# MRD104_MICROBOARD_APPS_A.net
KiCad netlist of a schematic drawn in EAGLE
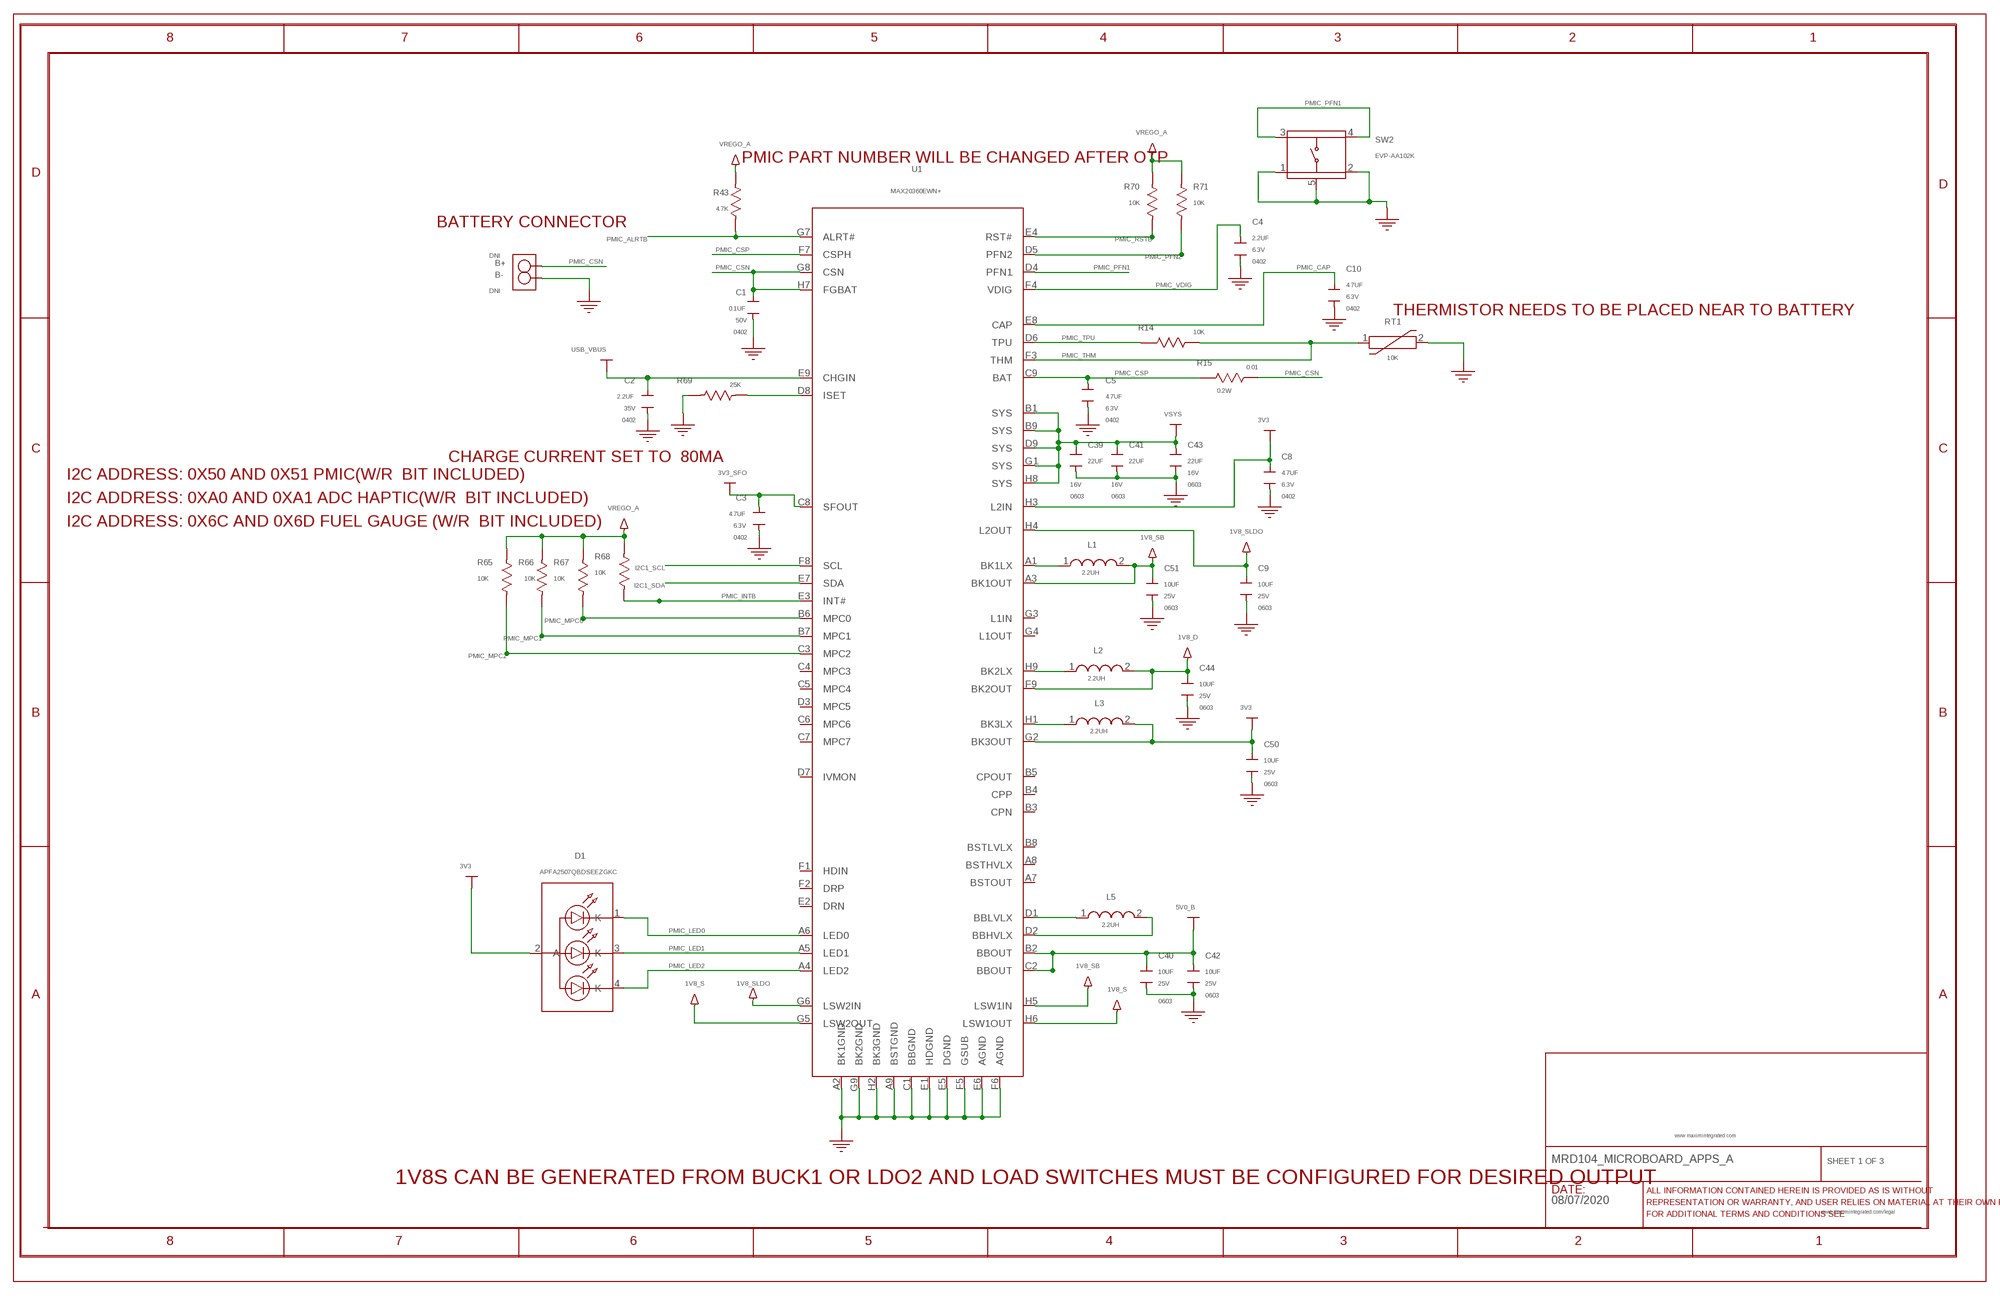
[diagram p0: schematic, sheet 1]
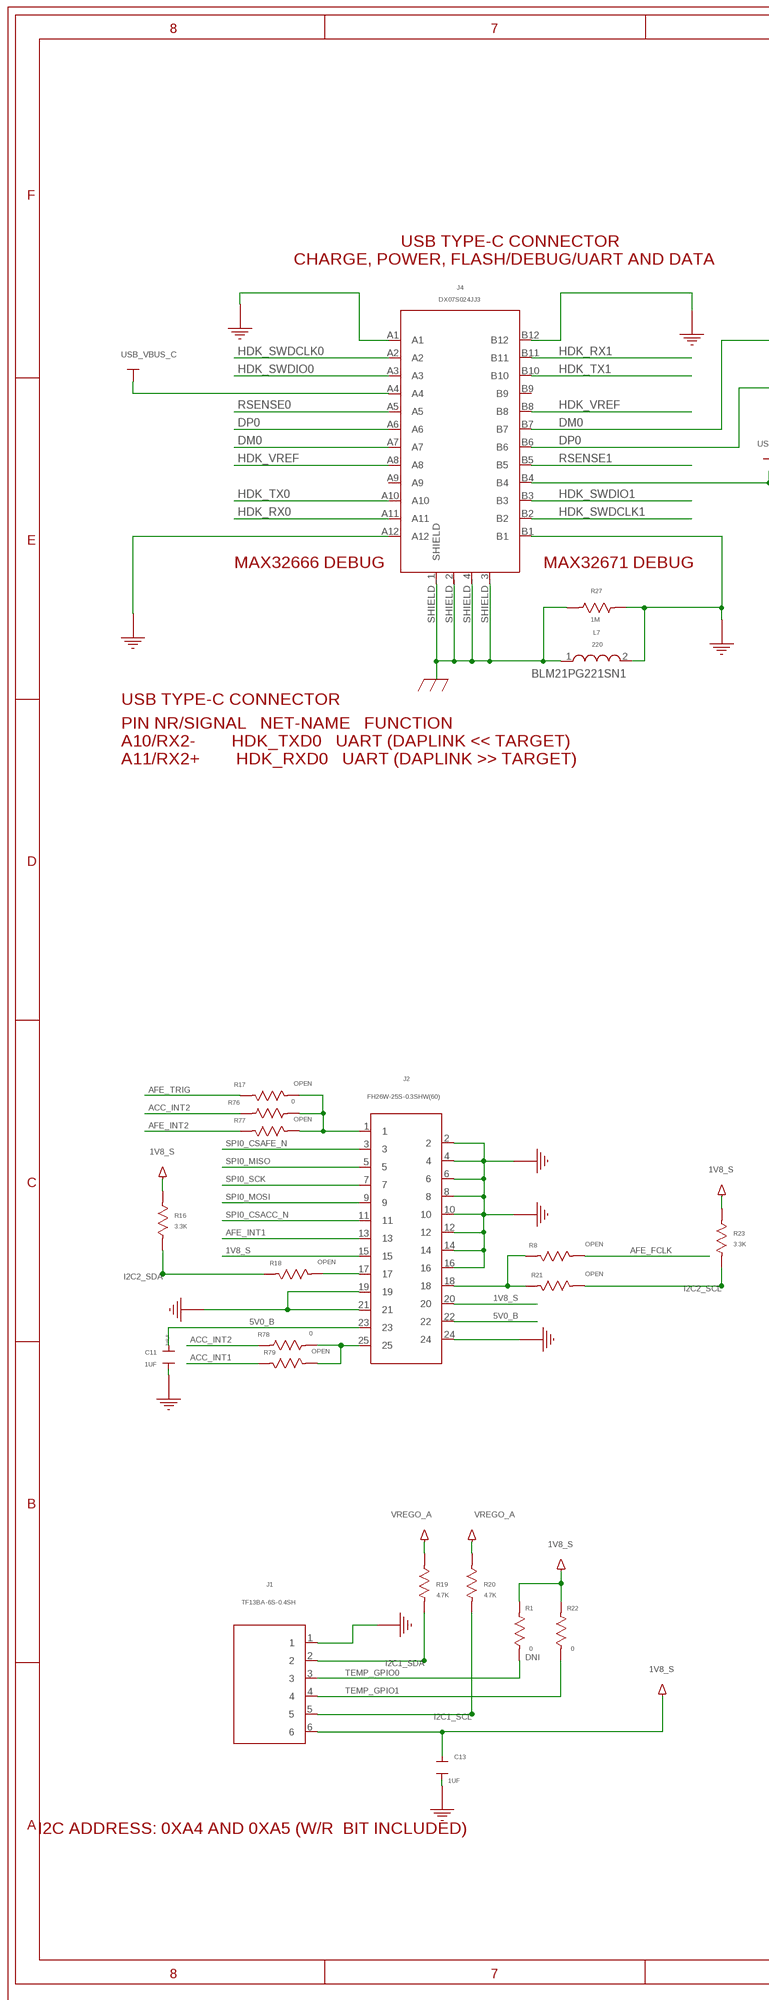
[diagram p1: schematic, sheet 2, part 1 of 2]
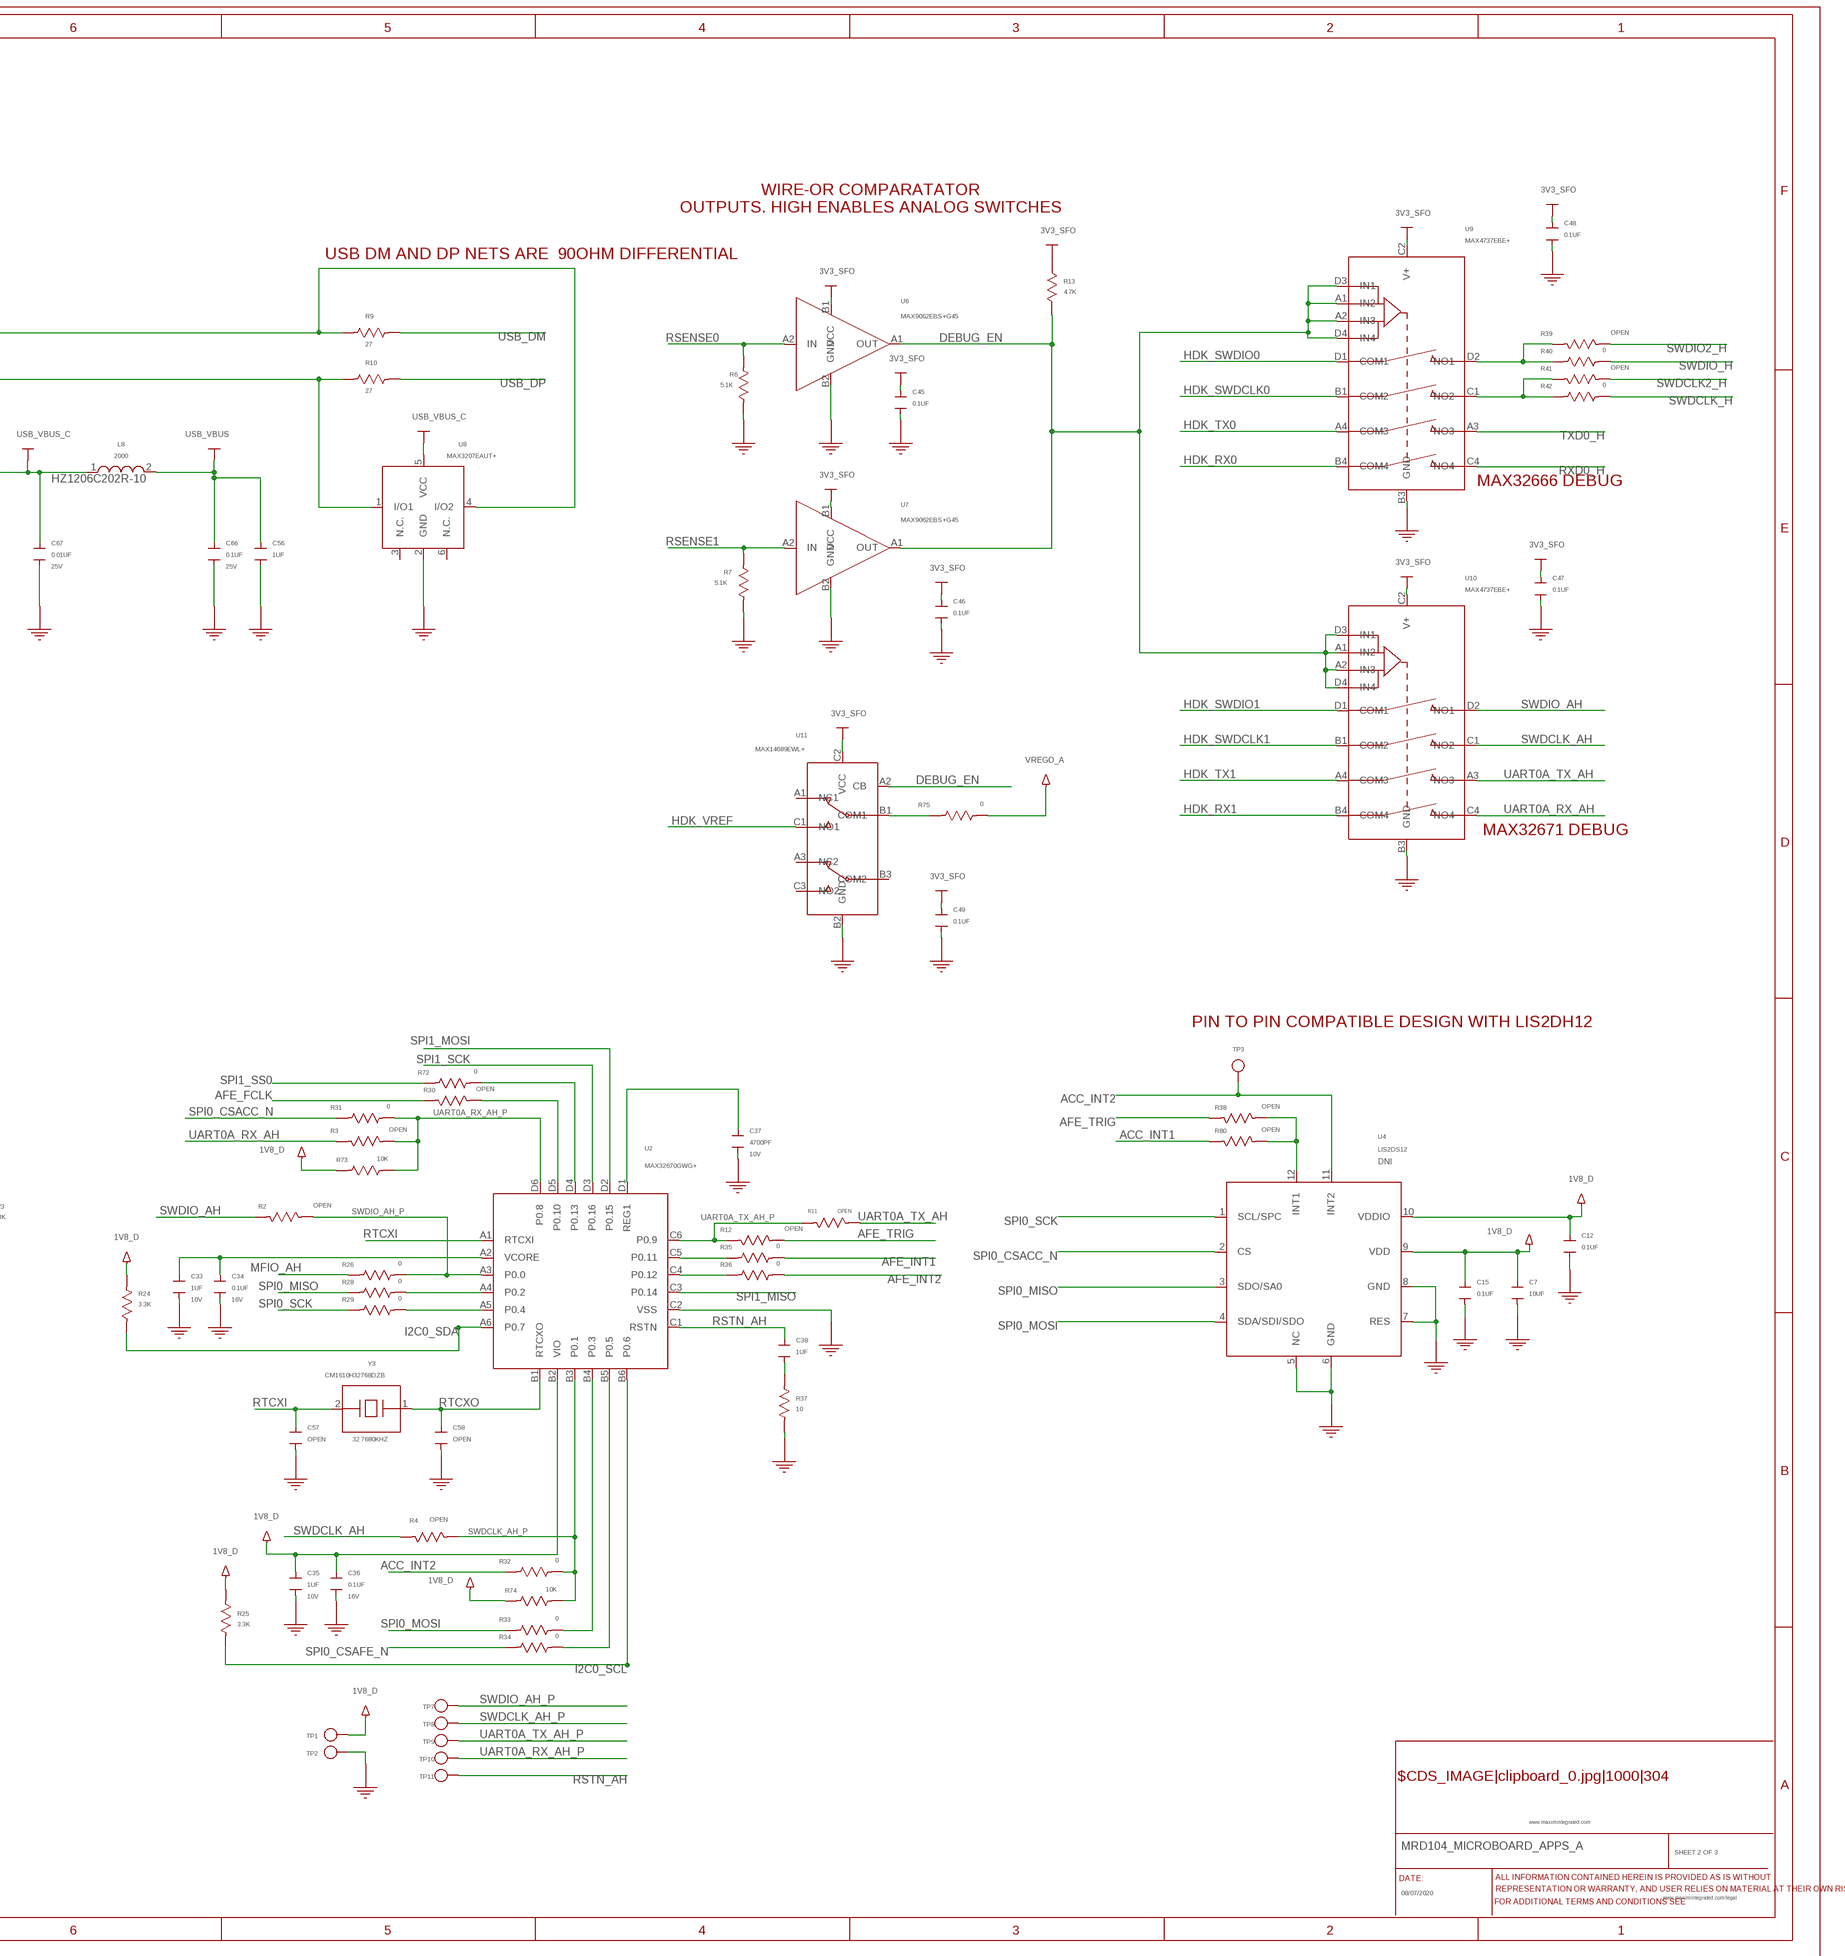
[diagram p2: schematic, sheet 2, part 2 of 2]
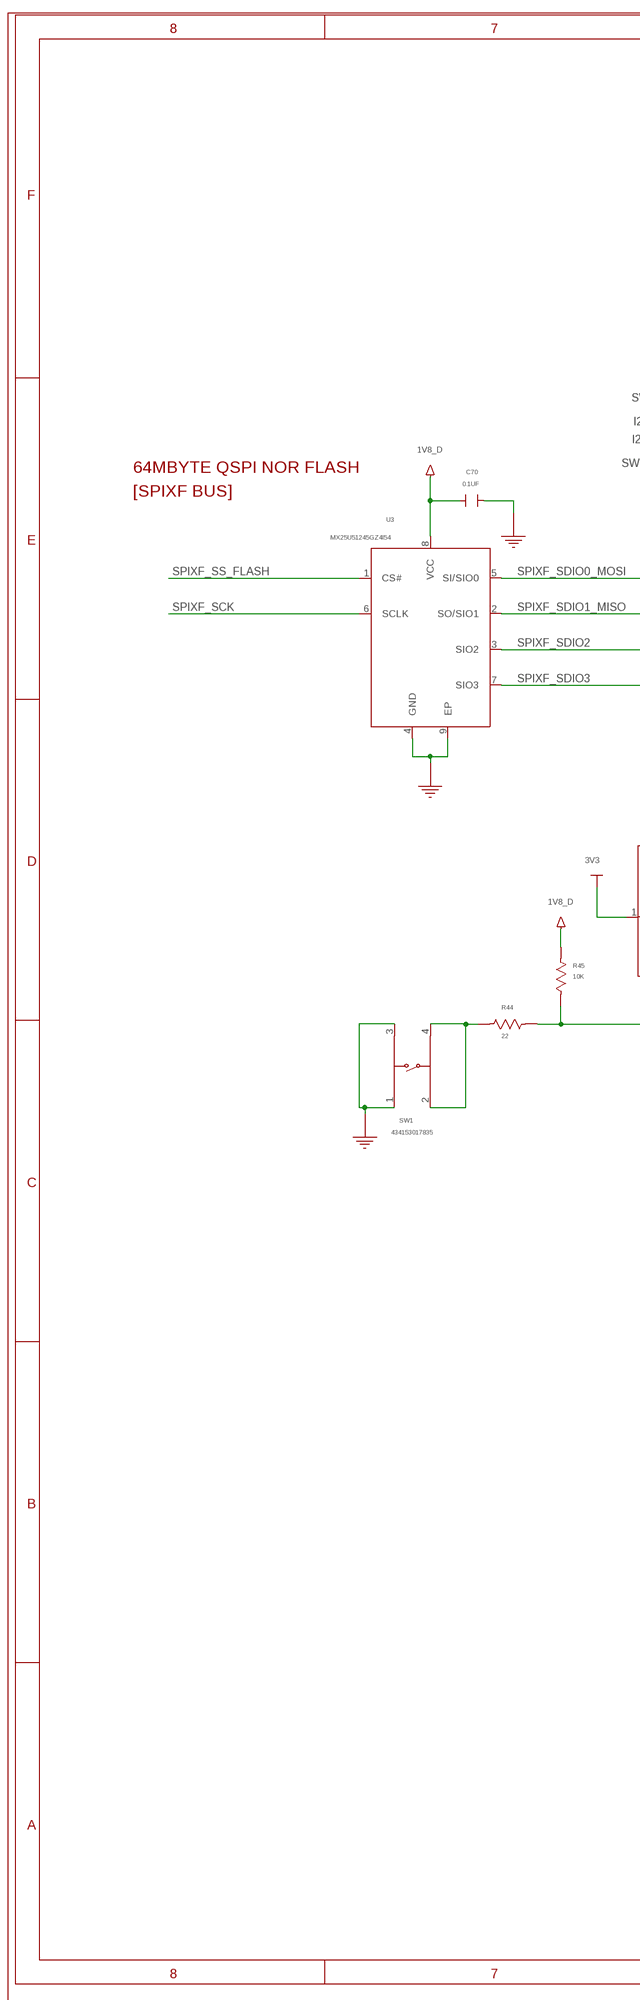
[diagram p3: schematic, sheet 3, part 1 of 2]
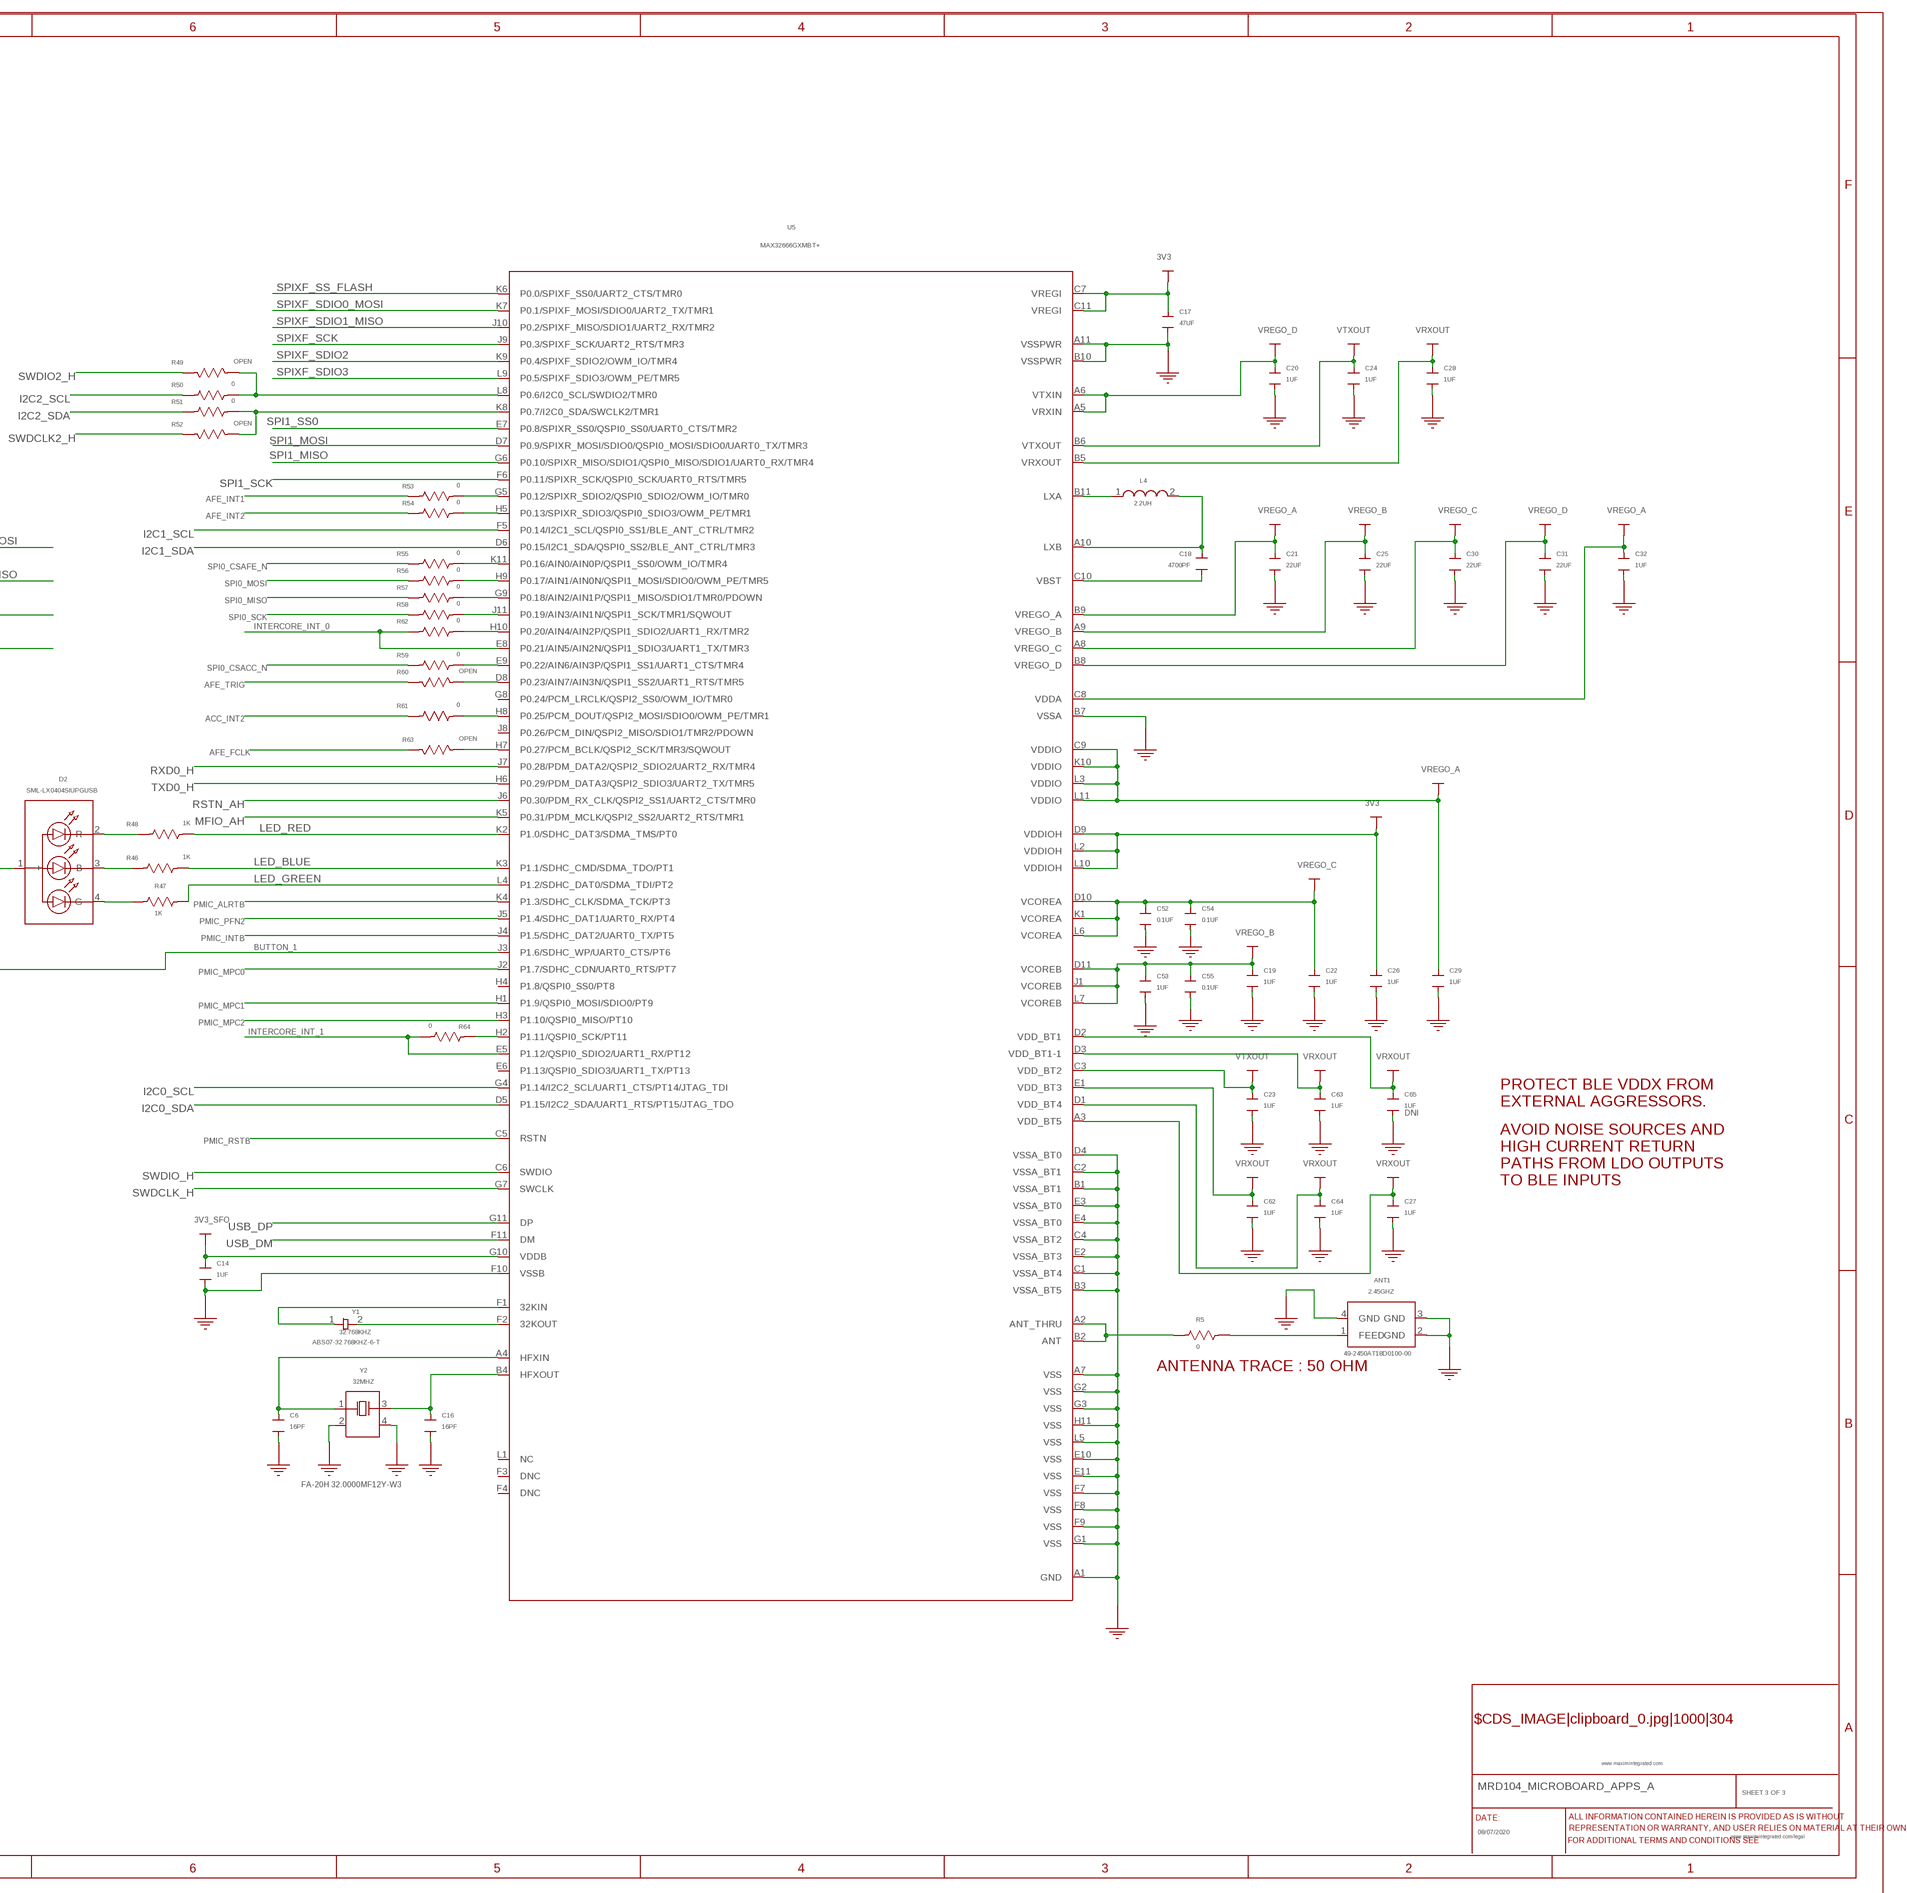
[diagram p4: schematic, sheet 3, part 2 of 2]

(export (version "E")
  (design (tool "Eeschema 10.0.6"))
  (components
    (comp (ref "ANT1")
      (value "2.45GHZ")
      (footprint "eagle-import:ANT_2450AT18D0100")
      (description "ANTENNA: DETUNING RESILIENT: SMT: EIA 1210: DETUNING RESILIENT: EDGE MOUNT DESIGN: 2.45GHZ")
      (fields
        (field (name "MANUFACTURER") "JOHANSON TECHNOLOGY")
        (field (name "MAXINV") "49-2450AT18D0100-00")
        (field (name "MFG_PART_NUMBER") "2450AT18D0100")
        (field (name "ORIGINALSYMBOLORIGIN") "(-150,125)")
        (field (name "PACK_TYPE") "SMD_4_1")
        (field (name "PHYS_PAGE") "3")
        (field (name "SEC_TYPE") "SMD_4_1")
        (field (name "TEMP_RANGE") "-40 DEGC TO +125 DEGC")
        (field (name "TOLERANCE") "N/A")
        (field (name "VER") "3")
        (field (name "VOLTAGE_RATING") "N/A")
      )
      (libsource (lib "eagle-import") (part "ANTENNA"))
    )
    (comp (ref "C6")
      (value "16PF")
      (footprint "eagle-import:CAPC0603X33M")
      (description "CAP: SMT (0201): 16PF: 5%: 50V: C0G: CERAMIC")
      (fields
        (field (name "CAP") "1.60E-11")
        (field (name "CASE") "SMT (0201)")
        (field (name "MANUFACTURER") "MURATA")
        (field (name "MAXINV") "EC111000004322")
        (field (name "MFG_PART_NUMBER") "GRM0335C1H160JA01")
        (field (name "ORIGINALSYMBOLORIGIN") "(-50,50)")
        (field (name "PACK_TYPE") "0201CAPM")
        (field (name "PHYS_PAGE") "3")
        (field (name "TEMP_RANGE") "-55 DEGC TO +125 DEGC")
        (field (name "TOLERANCE") "5%")
        (field (name "VER") "2")
        (field (name "VLOG_PARAM01") "CAP:INTEGER")
        (field (name "VOLTAGE_RATING") "50V")
      )
      (libsource (lib "eagle-import") (part "CAP_NPCAP_NP_1"))
    )
    (comp (ref "C14")
      (value "1UF")
      (footprint "eagle-import:CAPC0603X33M")
      (description "CAP: SMT (0201): 1UF: 20%: 10V: X5R: CERAMIC")
      (fields
        (field (name "CAP") "1.00E-06")
        (field (name "CASE") "SMT (0201)")
        (field (name "MANUFACTURER") "MURATA")
        (field (name "MAXINV") "20-0001U-AA20")
        (field (name "MFG_PART_NUMBER") "GRM033R61A105ME15")
        (field (name "ORIGINALSYMBOLORIGIN") "(-50,50)")
        (field (name "PACK_TYPE") "0201CAPM")
        (field (name "PHYS_PAGE") "3")
        (field (name "TEMP_RANGE") "-55 DEGC TO +85 DEGC")
        (field (name "TOLERANCE") "20%")
        (field (name "VER") "2")
        (field (name "VLOG_PARAM01") "CAP:INTEGER")
        (field (name "VOLTAGE_RATING") "10V")
      )
      (libsource (lib "eagle-import") (part "CAP_NPCAP_NP_1"))
    )
    (comp (ref "C16")
      (value "16PF")
      (footprint "eagle-import:CAPC0603X33M")
      (description "CAP: SMT (0201): 16PF: 5%: 50V: C0G: CERAMIC")
      (fields
        (field (name "CAP") "1.60E-11")
        (field (name "CASE") "SMT (0201)")
        (field (name "MANUFACTURER") "MURATA")
        (field (name "MAXINV") "EC111000004322")
        (field (name "MFG_PART_NUMBER") "GRM0335C1H160JA01")
        (field (name "ORIGINALSYMBOLORIGIN") "(-50,50)")
        (field (name "PACK_TYPE") "0201CAPM")
        (field (name "PHYS_PAGE") "3")
        (field (name "TEMP_RANGE") "-55 DEGC TO +125 DEGC")
        (field (name "TOLERANCE") "5%")
        (field (name "VER") "2")
        (field (name "VLOG_PARAM01") "CAP:INTEGER")
        (field (name "VOLTAGE_RATING") "50V")
      )
      (libsource (lib "eagle-import") (part "CAP_NPCAP_NP_1"))
    )
    (comp (ref "C17")
      (value "47UF")
      (footprint "eagle-import:CAPC2012X140M")
      (description "CAP: SMT (0805): 47UF: 20%: 10V: X5R: CERAMIC")
      (fields
        (field (name "CAP") "4.70E-05")
        (field (name "CASE") "SMT (0805)")
        (field (name "MANUFACTURER") "MURATA")
        (field (name "MAXINV") "20-0047U-A38")
        (field (name "MFG_PART_NUMBER") "GRM21BR61A476ME15")
        (field (name "ORIGINALSYMBOLORIGIN") "(-50,50)")
        (field (name "PACK_TYPE") "0805CAP")
        (field (name "PHYS_PAGE") "3")
        (field (name "TEMP_RANGE") "-55 DEGC TO +85 DEGC")
        (field (name "TOLERANCE") "20%")
        (field (name "VER") "2")
        (field (name "VLOG_PARAM01") "CAP:INTEGER")
        (field (name "VOLTAGE_RATING") "10V")
      )
      (libsource (lib "eagle-import") (part "CAP_NPCAP_NP"))
    )
    (comp (ref "C18")
      (value "4700PF")
      (footprint "eagle-import:CAPC0603X33M")
      (description "CAP: SMT (0201): 4700PF: 20%: 25V: X5R: CERAMIC")
      (fields
        (field (name "CAP") "4.70E-09")
        (field (name "CASE") "SMT (0201)")
        (field (name "MANUFACTURER") "MURATA")
        (field (name "MAXINV") "EC111000003909")
        (field (name "MFG_PART_NUMBER") "GRM033R61E472MA12")
        (field (name "ORIGINALSYMBOLORIGIN") "(-50,50)")
        (field (name "PACK_TYPE") "0201CAPM")
        (field (name "PHYS_PAGE") "3")
        (field (name "TEMP_RANGE") "-55 DEGC TO +85 DEGC")
        (field (name "TOLERANCE") "20%")
        (field (name "VER") "2")
        (field (name "VLOG_PARAM01") "CAP:INTEGER")
        (field (name "VOLTAGE_RATING") "25V")
      )
      (libsource (lib "eagle-import") (part "CAP_NPCAP_NP_1"))
    )
    (comp (ref "C19")
      (value "1UF")
      (footprint "eagle-import:0402")
      (description "CAP: SMT (0402): 1UF: 10%: 10V: X5R: CERAMIC")
      (fields
        (field (name "CAP") "1.00E-06")
        (field (name "CASE") "SMT (0402)")
        (field (name "MANUFACTURER") "KEMET:YAGEO")
        (field (name "MAXINV") "20-0001U-B8")
        (field (name "MFG_PART_NUMBER") "C0402C105K8PAC:CC0402KRX5R6BB105")
        (field (name "ORIGINALSYMBOLORIGIN") "(-50,50)")
        (field (name "PACK_TYPE") "0402CAP")
        (field (name "PHYS_PAGE") "3")
        (field (name "TEMP_RANGE") "-55 DEGC TO +85 DEGC")
        (field (name "TOLERANCE") "10%")
        (field (name "VER") "2")
        (field (name "VLOG_PARAM01") "CAP:INTEGER")
        (field (name "VOLTAGE_RATING") "10V")
      )
      (libsource (lib "eagle-import") (part "CAP_NPCAP_NP_2"))
    )
    (comp (ref "C20")
      (value "1UF")
      (footprint "eagle-import:0402")
      (description "CAP: SMT (0402): 1UF: 10%: 10V: X5R: CERAMIC")
      (fields
        (field (name "CAP") "1.00E-06")
        (field (name "CASE") "SMT (0402)")
        (field (name "MANUFACTURER") "KEMET:YAGEO")
        (field (name "MAXINV") "20-0001U-B8")
        (field (name "MFG_PART_NUMBER") "C0402C105K8PAC:CC0402KRX5R6BB105")
        (field (name "ORIGINALSYMBOLORIGIN") "(-50,50)")
        (field (name "PACK_TYPE") "0402CAP")
        (field (name "PHYS_PAGE") "3")
        (field (name "TEMP_RANGE") "-55 DEGC TO +85 DEGC")
        (field (name "TOLERANCE") "10%")
        (field (name "VER") "2")
        (field (name "VLOG_PARAM01") "CAP:INTEGER")
        (field (name "VOLTAGE_RATING") "10V")
      )
      (libsource (lib "eagle-import") (part "CAP_NPCAP_NP_2"))
    )
    (comp (ref "C21")
      (value "22UF")
      (footprint "eagle-import:0603")
      (description "CAP: SMT (0603): 22UF: 20%: 16V: X5R: CERAMIC")
      (fields
        (field (name "CAP") "2.20E-05")
        (field (name "CASE") "SMT (0603)")
        (field (name "MANUFACTURER") "SAMSUNG ELECTRONICS")
        (field (name "MAXINV") "20-0022U-A29")
        (field (name "MFG_PART_NUMBER") "CL10A226MO7JZNC")
        (field (name "ORIGINALSYMBOLORIGIN") "(-50,50)")
        (field (name "PACK_TYPE") "0603CAP")
        (field (name "PHYS_PAGE") "3")
        (field (name "TEMP_RANGE") "-55 DEGC TO +85 DEGC")
        (field (name "TOLERANCE") "20%")
        (field (name "VER") "2")
        (field (name "VLOG_PARAM01") "CAP:INTEGER")
        (field (name "VOLTAGE_RATING") "16V")
      )
      (libsource (lib "eagle-import") (part "CAP_NPCAP_NP_3"))
    )
    (comp (ref "C22")
      (value "1UF")
      (footprint "eagle-import:0402")
      (description "CAP: SMT (0402): 1UF: 10%: 10V: X5R: CERAMIC")
      (fields
        (field (name "CAP") "1.00E-06")
        (field (name "CASE") "SMT (0402)")
        (field (name "MANUFACTURER") "KEMET:YAGEO")
        (field (name "MAXINV") "20-0001U-B8")
        (field (name "MFG_PART_NUMBER") "C0402C105K8PAC:CC0402KRX5R6BB105")
        (field (name "ORIGINALSYMBOLORIGIN") "(-50,50)")
        (field (name "PACK_TYPE") "0402CAP")
        (field (name "PHYS_PAGE") "3")
        (field (name "TEMP_RANGE") "-55 DEGC TO +85 DEGC")
        (field (name "TOLERANCE") "10%")
        (field (name "VER") "2")
        (field (name "VLOG_PARAM01") "CAP:INTEGER")
        (field (name "VOLTAGE_RATING") "10V")
      )
      (libsource (lib "eagle-import") (part "CAP_NPCAP_NP_2"))
    )
    (comp (ref "C23")
      (value "1UF")
      (footprint "eagle-import:0402")
      (description "CAP: SMT (0402): 1UF: 10%: 10V: X5R: CERAMIC")
      (fields
        (field (name "CAP") "1.00E-06")
        (field (name "CASE") "SMT (0402)")
        (field (name "MANUFACTURER") "KEMET:YAGEO")
        (field (name "MAXINV") "20-0001U-B8")
        (field (name "MFG_PART_NUMBER") "C0402C105K8PAC:CC0402KRX5R6BB105")
        (field (name "ORIGINALSYMBOLORIGIN") "(-50,50)")
        (field (name "PACK_TYPE") "0402CAP")
        (field (name "PHYS_PAGE") "3")
        (field (name "TEMP_RANGE") "-55 DEGC TO +85 DEGC")
        (field (name "TOLERANCE") "10%")
        (field (name "VER") "2")
        (field (name "VLOG_PARAM01") "CAP:INTEGER")
        (field (name "VOLTAGE_RATING") "10V")
      )
      (libsource (lib "eagle-import") (part "CAP_NPCAP_NP_2"))
    )
    (comp (ref "C24")
      (value "1UF")
      (footprint "eagle-import:0402")
      (description "CAP: SMT (0402): 1UF: 10%: 10V: X5R: CERAMIC")
      (fields
        (field (name "CAP") "1.00E-06")
        (field (name "CASE") "SMT (0402)")
        (field (name "MANUFACTURER") "KEMET:YAGEO")
        (field (name "MAXINV") "20-0001U-B8")
        (field (name "MFG_PART_NUMBER") "C0402C105K8PAC:CC0402KRX5R6BB105")
        (field (name "ORIGINALSYMBOLORIGIN") "(-50,50)")
        (field (name "PACK_TYPE") "0402CAP")
        (field (name "PHYS_PAGE") "3")
        (field (name "TEMP_RANGE") "-55 DEGC TO +85 DEGC")
        (field (name "TOLERANCE") "10%")
        (field (name "VER") "2")
        (field (name "VLOG_PARAM01") "CAP:INTEGER")
        (field (name "VOLTAGE_RATING") "10V")
      )
      (libsource (lib "eagle-import") (part "CAP_NPCAP_NP_2"))
    )
    (comp (ref "C25")
      (value "22UF")
      (footprint "eagle-import:0603")
      (description "CAP: SMT (0603): 22UF: 20%: 16V: X5R: CERAMIC")
      (fields
        (field (name "CAP") "2.20E-05")
        (field (name "CASE") "SMT (0603)")
        (field (name "MANUFACTURER") "SAMSUNG ELECTRONICS")
        (field (name "MAXINV") "20-0022U-A29")
        (field (name "MFG_PART_NUMBER") "CL10A226MO7JZNC")
        (field (name "ORIGINALSYMBOLORIGIN") "(-50,50)")
        (field (name "PACK_TYPE") "0603CAP")
        (field (name "PHYS_PAGE") "3")
        (field (name "TEMP_RANGE") "-55 DEGC TO +85 DEGC")
        (field (name "TOLERANCE") "20%")
        (field (name "VER") "2")
        (field (name "VLOG_PARAM01") "CAP:INTEGER")
        (field (name "VOLTAGE_RATING") "16V")
      )
      (libsource (lib "eagle-import") (part "CAP_NPCAP_NP_3"))
    )
    (comp (ref "C26")
      (value "1UF")
      (footprint "eagle-import:0402")
      (description "CAP: SMT (0402): 1UF: 10%: 10V: X5R: CERAMIC")
      (fields
        (field (name "CAP") "1.00E-06")
        (field (name "CASE") "SMT (0402)")
        (field (name "MANUFACTURER") "KEMET:YAGEO")
        (field (name "MAXINV") "20-0001U-B8")
        (field (name "MFG_PART_NUMBER") "C0402C105K8PAC:CC0402KRX5R6BB105")
        (field (name "ORIGINALSYMBOLORIGIN") "(-50,50)")
        (field (name "PACK_TYPE") "0402CAP")
        (field (name "PHYS_PAGE") "3")
        (field (name "TEMP_RANGE") "-55 DEGC TO +85 DEGC")
        (field (name "TOLERANCE") "10%")
        (field (name "VER") "2")
        (field (name "VLOG_PARAM01") "CAP:INTEGER")
        (field (name "VOLTAGE_RATING") "10V")
      )
      (libsource (lib "eagle-import") (part "CAP_NPCAP_NP_2"))
    )
    (comp (ref "C27")
      (value "1UF")
      (footprint "eagle-import:0402")
      (description "CAP: SMT (0402): 1UF: 10%: 10V: X5R: CERAMIC")
      (fields
        (field (name "CAP") "1.00E-06")
        (field (name "CASE") "SMT (0402)")
        (field (name "MANUFACTURER") "KEMET:YAGEO")
        (field (name "MAXINV") "20-0001U-B8")
        (field (name "MFG_PART_NUMBER") "C0402C105K8PAC:CC0402KRX5R6BB105")
        (field (name "ORIGINALSYMBOLORIGIN") "(-50,50)")
        (field (name "PACK_TYPE") "0402CAP")
        (field (name "PHYS_PAGE") "3")
        (field (name "TEMP_RANGE") "-55 DEGC TO +85 DEGC")
        (field (name "TOLERANCE") "10%")
        (field (name "VER") "2")
        (field (name "VLOG_PARAM01") "CAP:INTEGER")
        (field (name "VOLTAGE_RATING") "10V")
      )
      (libsource (lib "eagle-import") (part "CAP_NPCAP_NP_2"))
    )
    (comp (ref "C28")
      (value "1UF")
      (footprint "eagle-import:0402")
      (description "CAP: SMT (0402): 1UF: 10%: 10V: X5R: CERAMIC")
      (fields
        (field (name "CAP") "1.00E-06")
        (field (name "CASE") "SMT (0402)")
        (field (name "MANUFACTURER") "KEMET:YAGEO")
        (field (name "MAXINV") "20-0001U-B8")
        (field (name "MFG_PART_NUMBER") "C0402C105K8PAC:CC0402KRX5R6BB105")
        (field (name "ORIGINALSYMBOLORIGIN") "(-50,50)")
        (field (name "PACK_TYPE") "0402CAP")
        (field (name "PHYS_PAGE") "3")
        (field (name "TEMP_RANGE") "-55 DEGC TO +85 DEGC")
        (field (name "TOLERANCE") "10%")
        (field (name "VER") "2")
        (field (name "VLOG_PARAM01") "CAP:INTEGER")
        (field (name "VOLTAGE_RATING") "10V")
      )
      (libsource (lib "eagle-import") (part "CAP_NPCAP_NP_2"))
    )
    (comp (ref "C29")
      (value "1UF")
      (footprint "eagle-import:0402")
      (description "CAP: SMT (0402): 1UF: 10%: 10V: X5R: CERAMIC")
      (fields
        (field (name "CAP") "1.00E-06")
        (field (name "CASE") "SMT (0402)")
        (field (name "MANUFACTURER") "KEMET:YAGEO")
        (field (name "MAXINV") "20-0001U-B8")
        (field (name "MFG_PART_NUMBER") "C0402C105K8PAC:CC0402KRX5R6BB105")
        (field (name "ORIGINALSYMBOLORIGIN") "(-50,50)")
        (field (name "PACK_TYPE") "0402CAP")
        (field (name "PHYS_PAGE") "3")
        (field (name "TEMP_RANGE") "-55 DEGC TO +85 DEGC")
        (field (name "TOLERANCE") "10%")
        (field (name "VER") "2")
        (field (name "VLOG_PARAM01") "CAP:INTEGER")
        (field (name "VOLTAGE_RATING") "10V")
      )
      (libsource (lib "eagle-import") (part "CAP_NPCAP_NP_2"))
    )
    (comp (ref "C30")
      (value "22UF")
      (footprint "eagle-import:0603")
      (description "CAP: SMT (0603): 22UF: 20%: 16V: X5R: CERAMIC")
      (fields
        (field (name "CAP") "2.20E-05")
        (field (name "CASE") "SMT (0603)")
        (field (name "MANUFACTURER") "SAMSUNG ELECTRONICS")
        (field (name "MAXINV") "20-0022U-A29")
        (field (name "MFG_PART_NUMBER") "CL10A226MO7JZNC")
        (field (name "ORIGINALSYMBOLORIGIN") "(-50,50)")
        (field (name "PACK_TYPE") "0603CAP")
        (field (name "PHYS_PAGE") "3")
        (field (name "TEMP_RANGE") "-55 DEGC TO +85 DEGC")
        (field (name "TOLERANCE") "20%")
        (field (name "VER") "2")
        (field (name "VLOG_PARAM01") "CAP:INTEGER")
        (field (name "VOLTAGE_RATING") "16V")
      )
      (libsource (lib "eagle-import") (part "CAP_NPCAP_NP_3"))
    )
    (comp (ref "C31")
      (value "22UF")
      (footprint "eagle-import:0603")
      (description "CAP: SMT (0603): 22UF: 20%: 16V: X5R: CERAMIC")
      (fields
        (field (name "CAP") "2.20E-05")
        (field (name "CASE") "SMT (0603)")
        (field (name "MANUFACTURER") "SAMSUNG ELECTRONICS")
        (field (name "MAXINV") "20-0022U-A29")
        (field (name "MFG_PART_NUMBER") "CL10A226MO7JZNC")
        (field (name "ORIGINALSYMBOLORIGIN") "(-50,50)")
        (field (name "PACK_TYPE") "0603CAP")
        (field (name "PHYS_PAGE") "3")
        (field (name "TEMP_RANGE") "-55 DEGC TO +85 DEGC")
        (field (name "TOLERANCE") "20%")
        (field (name "VER") "2")
        (field (name "VLOG_PARAM01") "CAP:INTEGER")
        (field (name "VOLTAGE_RATING") "16V")
      )
      (libsource (lib "eagle-import") (part "CAP_NPCAP_NP_3"))
    )
    (comp (ref "C32")
      (value "1UF")
      (footprint "eagle-import:0402")
      (description "CAP: SMT (0402): 1UF: 10%: 10V: X5R: CERAMIC")
      (fields
        (field (name "CAP") "1.00E-06")
        (field (name "CASE") "SMT (0402)")
        (field (name "MANUFACTURER") "KEMET:YAGEO")
        (field (name "MAXINV") "20-0001U-B8")
        (field (name "MFG_PART_NUMBER") "C0402C105K8PAC:CC0402KRX5R6BB105")
        (field (name "ORIGINALSYMBOLORIGIN") "(-50,50)")
        (field (name "PACK_TYPE") "0402CAP")
        (field (name "PHYS_PAGE") "3")
        (field (name "TEMP_RANGE") "-55 DEGC TO +85 DEGC")
        (field (name "TOLERANCE") "10%")
        (field (name "VER") "2")
        (field (name "VLOG_PARAM01") "CAP:INTEGER")
        (field (name "VOLTAGE_RATING") "10V")
      )
      (libsource (lib "eagle-import") (part "CAP_NPCAP_NP_2"))
    )
    (comp (ref "C52")
      (value "0.1UF")
      (footprint "eagle-import:CAPC0603X33M")
      (description "CAP: SMT (0201): 0.1UF: 10%: 16V: X7S: CERAMIC")
      (fields
        (field (name "CAP") "1.00E-07")
        (field (name "CASE") "SMT (0201)")
        (field (name "MANUFACTURER") "MURATA")
        (field (name "MAXINV") "20-000U1-BA99")
        (field (name "MFG_PART_NUMBER") "GRM033C71C104KE14")
        (field (name "ORIGINALSYMBOLORIGIN") "(-50,50)")
        (field (name "PACK_TYPE") "0201CAPM")
        (field (name "PHYS_PAGE") "3")
        (field (name "TEMP_RANGE") "-55 DEGC TO +125 DEGC")
        (field (name "TOLERANCE") "10%")
        (field (name "VER") "2")
        (field (name "VLOG_PARAM01") "CAP:INTEGER")
        (field (name "VOLTAGE_RATING") "16V")
      )
      (libsource (lib "eagle-import") (part "CAP_NPCAP_NP_1"))
    )
    (comp (ref "C53")
      (value "1UF")
      (footprint "eagle-import:0402")
      (description "CAP: SMT (0402): 1UF: 10%: 10V: X5R: CERAMIC")
      (fields
        (field (name "CAP") "1.00E-06")
        (field (name "CASE") "SMT (0402)")
        (field (name "MANUFACTURER") "KEMET:YAGEO")
        (field (name "MAXINV") "20-0001U-B8")
        (field (name "MFG_PART_NUMBER") "C0402C105K8PAC:CC0402KRX5R6BB105")
        (field (name "ORIGINALSYMBOLORIGIN") "(-50,50)")
        (field (name "PACK_TYPE") "0402CAP")
        (field (name "PHYS_PAGE") "3")
        (field (name "TEMP_RANGE") "-55 DEGC TO +85 DEGC")
        (field (name "TOLERANCE") "10%")
        (field (name "VER") "2")
        (field (name "VLOG_PARAM01") "CAP:INTEGER")
        (field (name "VOLTAGE_RATING") "10V")
      )
      (libsource (lib "eagle-import") (part "CAP_NPCAP_NP_2"))
    )
    (comp (ref "C54")
      (value "0.1UF")
      (footprint "eagle-import:CAPC0603X33M")
      (description "CAP: SMT (0201): 0.1UF: 10%: 16V: X7S: CERAMIC")
      (fields
        (field (name "CAP") "1.00E-07")
        (field (name "CASE") "SMT (0201)")
        (field (name "MANUFACTURER") "MURATA")
        (field (name "MAXINV") "20-000U1-BA99")
        (field (name "MFG_PART_NUMBER") "GRM033C71C104KE14")
        (field (name "ORIGINALSYMBOLORIGIN") "(-50,50)")
        (field (name "PACK_TYPE") "0201CAPM")
        (field (name "PHYS_PAGE") "3")
        (field (name "TEMP_RANGE") "-55 DEGC TO +125 DEGC")
        (field (name "TOLERANCE") "10%")
        (field (name "VER") "2")
        (field (name "VLOG_PARAM01") "CAP:INTEGER")
        (field (name "VOLTAGE_RATING") "16V")
      )
      (libsource (lib "eagle-import") (part "CAP_NPCAP_NP_1"))
    )
    (comp (ref "C55")
      (value "0.1UF")
      (footprint "eagle-import:CAPC0603X33M")
      (description "CAP: SMT (0201): 0.1UF: 10%: 16V: X7S: CERAMIC")
      (fields
        (field (name "CAP") "1.00E-07")
        (field (name "CASE") "SMT (0201)")
        (field (name "MANUFACTURER") "MURATA")
        (field (name "MAXINV") "20-000U1-BA99")
        (field (name "MFG_PART_NUMBER") "GRM033C71C104KE14")
        (field (name "ORIGINALSYMBOLORIGIN") "(-50,50)")
        (field (name "PACK_TYPE") "0201CAPM")
        (field (name "PHYS_PAGE") "3")
        (field (name "TEMP_RANGE") "-55 DEGC TO +125 DEGC")
        (field (name "TOLERANCE") "10%")
        (field (name "VER") "2")
        (field (name "VLOG_PARAM01") "CAP:INTEGER")
        (field (name "VOLTAGE_RATING") "16V")
      )
      (libsource (lib "eagle-import") (part "CAP_NPCAP_NP_1"))
    )
    (comp (ref "C62")
      (value "1UF")
      (footprint "eagle-import:0402")
      (description "CAP: SMT (0402): 1UF: 10%: 10V: X5R: CERAMIC")
      (fields
        (field (name "CAP") "1.00E-06")
        (field (name "CASE") "SMT (0402)")
        (field (name "MANUFACTURER") "KEMET:YAGEO")
        (field (name "MAXINV") "20-0001U-B8")
        (field (name "MFG_PART_NUMBER") "C0402C105K8PAC:CC0402KRX5R6BB105")
        (field (name "ORIGINALSYMBOLORIGIN") "(-50,50)")
        (field (name "PACK_TYPE") "0402CAP")
        (field (name "PHYS_PAGE") "3")
        (field (name "TEMP_RANGE") "-55 DEGC TO +85 DEGC")
        (field (name "TOLERANCE") "10%")
        (field (name "VER") "2")
        (field (name "VLOG_PARAM01") "CAP:INTEGER")
        (field (name "VOLTAGE_RATING") "10V")
      )
      (libsource (lib "eagle-import") (part "CAP_NPCAP_NP_2"))
    )
    (comp (ref "C63")
      (value "1UF")
      (footprint "eagle-import:0402")
      (description "CAP: SMT (0402): 1UF: 10%: 10V: X5R: CERAMIC")
      (fields
        (field (name "CAP") "1.00E-06")
        (field (name "CASE") "SMT (0402)")
        (field (name "MANUFACTURER") "KEMET:YAGEO")
        (field (name "MAXINV") "20-0001U-B8")
        (field (name "MFG_PART_NUMBER") "C0402C105K8PAC:CC0402KRX5R6BB105")
        (field (name "ORIGINALSYMBOLORIGIN") "(-50,50)")
        (field (name "PACK_TYPE") "0402CAP")
        (field (name "PHYS_PAGE") "3")
        (field (name "TEMP_RANGE") "-55 DEGC TO +85 DEGC")
        (field (name "TOLERANCE") "10%")
        (field (name "VER") "2")
        (field (name "VLOG_PARAM01") "CAP:INTEGER")
        (field (name "VOLTAGE_RATING") "10V")
      )
      (libsource (lib "eagle-import") (part "CAP_NPCAP_NP_2"))
    )
    (comp (ref "C64")
      (value "1UF")
      (footprint "eagle-import:0402")
      (description "CAP: SMT (0402): 1UF: 10%: 10V: X5R: CERAMIC")
      (fields
        (field (name "CAP") "1.00E-06")
        (field (name "CASE") "SMT (0402)")
        (field (name "MANUFACTURER") "KEMET:YAGEO")
        (field (name "MAXINV") "20-0001U-B8")
        (field (name "MFG_PART_NUMBER") "C0402C105K8PAC:CC0402KRX5R6BB105")
        (field (name "ORIGINALSYMBOLORIGIN") "(-50,50)")
        (field (name "PACK_TYPE") "0402CAP")
        (field (name "PHYS_PAGE") "3")
        (field (name "TEMP_RANGE") "-55 DEGC TO +85 DEGC")
        (field (name "TOLERANCE") "10%")
        (field (name "VER") "2")
        (field (name "VLOG_PARAM01") "CAP:INTEGER")
        (field (name "VOLTAGE_RATING") "10V")
      )
      (libsource (lib "eagle-import") (part "CAP_NPCAP_NP_2"))
    )
    (comp (ref "C65")
      (value "1UF")
      (footprint "eagle-import:0402")
      (description "CAP: SMT (0402): 1UF: 10%: 10V: X5R: CERAMIC")
      (fields
        (field (name "CAP") "1.00E-06")
        (field (name "CASE") "SMT (0402)")
        (field (name "MANUFACTURER") "KEMET:YAGEO")
        (field (name "MAXINV") "20-0001U-B8")
        (field (name "MFG_PART_NUMBER") "C0402C105K8PAC:CC0402KRX5R6BB105")
        (field (name "ORIGINALSYMBOLORIGIN") "(-50,50)")
        (field (name "PACK_TYPE") "0402CAP")
        (field (name "PHYS_PAGE") "3")
        (field (name "TEMP_RANGE") "-55 DEGC TO +85 DEGC")
        (field (name "TOLERANCE") "10%")
        (field (name "VARIANT") "DNI")
        (field (name "VER") "2")
        (field (name "VLOG_PARAM01") "CAP:INTEGER")
        (field (name "VOLTAGE_RATING") "10V")
      )
      (libsource (lib "eagle-import") (part "CAP_NPCAP_NP_2"))
    )
    (comp (ref "C70")
      (value "0.1UF")
      (footprint "eagle-import:CAPC0603X33M")
      (description "CAP: SMT (0201): 0.1UF: 10%: 10V: X5R: CERAMIC")
      (fields
        (field (name "CAP") "1.00E-07")
        (field (name "CASE") "SMT (0201)")
        (field (name "MANUFACTURER") "TDK")
        (field (name "MAXINV") "20-000U1-61")
        (field (name "MFG_PART_NUMBER") "C0603X5R1A104K030BC")
        (field (name "ORIGINALSYMBOLORIGIN") "(-50,50)")
        (field (name "PACK_TYPE") "0201CAPM")
        (field (name "PHYS_PAGE") "3")
        (field (name "TEMP_RANGE") "-55 DEGC TO +85 DEGC")
        (field (name "TOLERANCE") "10%")
        (field (name "VER") "2")
        (field (name "VLOG_PARAM01") "CAP:INTEGER")
        (field (name "VOLTAGE_RATING") "10V")
      )
      (libsource (lib "eagle-import") (part "CAP_NPCAP_NP_1"))
    )
    (comp (ref "D2")
      (value "SML-LX0404SIUPGUSB")
      (footprint "eagle-import:LED_LX0404")
      (description "DIODE: LED: SML: FULL COLOR: WATER CLEAR LENS: RED-GREEN-BLUE: SMT: VF=2.95V: IF=0.1A")
      (fields
        (field (name "MANUFACTURER") "LUMEX OPTOCOMPONENTS INC")
        (field (name "MAXINV") "30-SMLLX0404SIUPGUSB-00")
        (field (name "MFG_PART_NUMBER") "SML-LX0404SIUPGUSB")
        (field (name "ORIGINALSYMBOLORIGIN") "(-150,275)")
        (field (name "PACK_TYPE") "LX0404")
        (field (name "PHYS_PAGE") "3")
        (field (name "TEMP_RANGE") "-40 DEGC TO +85 DEGC")
        (field (name "TOLERANCE") "N/A")
        (field (name "VER") "7")
        (field (name "VOLTAGE_RATING") "2.95V")
      )
      (libsource (lib "eagle-import") (part "LED_4P#1"))
    )
    (comp (ref "L4")
      (value "2.2UH")
      (footprint "eagle-import:0805")
      (description "INDUCTOR: SMT (0805): FERRITE: 2.2UH: 20%: 1A")
      (fields
        (field (name "CASE") "SMT (0805)")
        (field (name "MANUFACTURER") "TDK")
        (field (name "MAXINV") "50-002U2-OXF")
        (field (name "MFG_PART_NUMBER") "MLP2012H2R2MT0S1")
        (field (name "ORIGINALSYMBOLORIGIN") "(-100,50)")
        (field (name "PACK_TYPE") "0805")
        (field (name "PHYS_PAGE") "3")
        (field (name "TEMP_RANGE") "-40 DEGC TO +125 DEGC")
        (field (name "TOLERANCE") "20%")
        (field (name "VER") "1")
      )
      (libsource (lib "eagle-import") (part "INDUCTINDUCT"))
    )
    (comp (ref "R5")
      (value "0")
      (footprint "eagle-import:0402")
      (description "RES: SMT (0402): 0: JUMPER: JUMPER: 0.1000W")
      (fields
        (field (name "CASE") "SMT (0402)")
        (field (name "MANUFACTURER") "PANASONIC")
        (field (name "MAXINV") "80-0000R-26A")
        (field (name "MFG_PART_NUMBER") "ERJ-2GE0R00")
        (field (name "ORIGINALSYMBOLORIGIN") "(-75,50)")
        (field (name "PACK_TYPE") "0402RES")
        (field (name "PHYS_PAGE") "3")
        (field (name "POWER_RATING") "0.10W")
        (field (name "RES") "0.00000001E00")
        (field (name "TEMP_RANGE") "-55 DEGC TO +155 DEGC")
        (field (name "TOLERANCE") "0%")
        (field (name "VER") "2")
        (field (name "VLOG_PARAM01") "RES:INTEGER")
      )
      (libsource (lib "eagle-import") (part "RES_SMDRES_SMD_2"))
    )
    (comp (ref "R44")
      (value "22")
      (footprint "eagle-import:0402")
      (description "RES: SMT (0402): 22: 5%: +/-200PPM/DEGC: 0.1000W")
      (fields
        (field (name "CASE") "SMT (0402)")
        (field (name "MANUFACTURER") "PANASONIC")
        (field (name "MATERIAL_TYPE") "THICK FILM")
        (field (name "MAXINV") "80-0022R-Q6")
        (field (name "MFG_PART_NUMBER") "ERJ-2GEJ220")
        (field (name "ORIGINALSYMBOLORIGIN") "(-75,50)")
        (field (name "PACK_TYPE") "0402RES")
        (field (name "PHYS_PAGE") "3")
        (field (name "POWER_RATING") "0.10W")
        (field (name "RES") "2.20E01")
        (field (name "TEMP_RANGE") "-55 DEGC TO +155 DEGC")
        (field (name "TOLERANCE") "5%")
        (field (name "VER") "2")
        (field (name "VLOG_PARAM01") "RES:INTEGER")
      )
      (libsource (lib "eagle-import") (part "RES_SMDRES_SMD_2"))
    )
    (comp (ref "R45")
      (value "10K")
      (footprint "eagle-import:0402")
      (description "RES: SMT (0402): 10K: 1%: +/-100PPM/DEGC: 0.0630W")
      (fields
        (field (name "CASE") "SMT (0402)")
        (field (name "MANUFACTURER") "VISHAY DALE:YAGEO PHICOMP")
        (field (name "MAXINV") "80-0010K-23")
        (field (name "MFG_PART_NUMBER") "CRCW040210K0FK:RC0402FR-0710KL")
        (field (name "ORIGINALSYMBOLORIGIN") "(-75,50)")
        (field (name "PACK_TYPE") "0402RES")
        (field (name "PHYS_PAGE") "3")
        (field (name "POWER_RATING") "0.0625W")
        (field (name "RES") "1.00E04")
        (field (name "TEMP_RANGE") "-55 DEGC TO +155 DEGC")
        (field (name "TOLERANCE") "1%")
        (field (name "VER") "2")
        (field (name "VLOG_PARAM01") "RES:INTEGER")
      )
      (libsource (lib "eagle-import") (part "RES_SMDRES_SMD_2"))
    )
    (comp (ref "R46")
      (value "1K")
      (footprint "eagle-import:0402")
      (description "RES: SMT (0402): 1K: 0.10%: +/-25PPM/DEGC: 0.1000W")
      (fields
        (field (name "CASE") "SMT (0402)")
        (field (name "MANUFACTURER") "VISHAY DALE")
        (field (name "MATERIAL_TYPE") "THIN FILM")
        (field (name "MAXINV") "80-0001K-CA54")
        (field (name "MFG_PART_NUMBER") "TNPW04021K00BE")
        (field (name "ORIGINALSYMBOLORIGIN") "(-75,50)")
        (field (name "PACK_TYPE") "0402RES")
        (field (name "PHYS_PAGE") "3")
        (field (name "POWER_RATING") "0.1W")
        (field (name "RES") "1.00E03")
        (field (name "TEMP_RANGE") "-55 DEGC TO +155 DEGC")
        (field (name "TOLERANCE") "0.1%")
        (field (name "VER") "2")
        (field (name "VLOG_PARAM01") "RES:INTEGER")
      )
      (libsource (lib "eagle-import") (part "RES_SMDRES_SMD_2"))
    )
    (comp (ref "R47")
      (value "1K")
      (footprint "eagle-import:0402")
      (description "RES: SMT (0402): 1K: 0.10%: +/-25PPM/DEGC: 0.1000W")
      (fields
        (field (name "CASE") "SMT (0402)")
        (field (name "MANUFACTURER") "VISHAY DALE")
        (field (name "MATERIAL_TYPE") "THIN FILM")
        (field (name "MAXINV") "80-0001K-CA54")
        (field (name "MFG_PART_NUMBER") "TNPW04021K00BE")
        (field (name "ORIGINALSYMBOLORIGIN") "(-75,50)")
        (field (name "PACK_TYPE") "0402RES")
        (field (name "PHYS_PAGE") "3")
        (field (name "POWER_RATING") "0.1W")
        (field (name "RES") "1.00E03")
        (field (name "TEMP_RANGE") "-55 DEGC TO +155 DEGC")
        (field (name "TOLERANCE") "0.1%")
        (field (name "VER") "2")
        (field (name "VLOG_PARAM01") "RES:INTEGER")
      )
      (libsource (lib "eagle-import") (part "RES_SMDRES_SMD_2"))
    )
    (comp (ref "R48")
      (value "1K")
      (footprint "eagle-import:0402")
      (description "RES: SMT (0402): 1K: 0.10%: +/-25PPM/DEGC: 0.1000W")
      (fields
        (field (name "CASE") "SMT (0402)")
        (field (name "MANUFACTURER") "VISHAY DALE")
        (field (name "MATERIAL_TYPE") "THIN FILM")
        (field (name "MAXINV") "80-0001K-CA54")
        (field (name "MFG_PART_NUMBER") "TNPW04021K00BE")
        (field (name "ORIGINALSYMBOLORIGIN") "(-75,50)")
        (field (name "PACK_TYPE") "0402RES")
        (field (name "PHYS_PAGE") "3")
        (field (name "POWER_RATING") "0.1W")
        (field (name "RES") "1.00E03")
        (field (name "TEMP_RANGE") "-55 DEGC TO +155 DEGC")
        (field (name "TOLERANCE") "0.1%")
        (field (name "VER") "2")
        (field (name "VLOG_PARAM01") "RES:INTEGER")
      )
      (libsource (lib "eagle-import") (part "RES_SMDRES_SMD_2"))
    )
    (comp (ref "R49")
      (value "OPEN")
      (footprint "eagle-import:RESC0603X23L")
      (description "RESISTOR: 0201: OPEN: FORMFACTOR")
      (fields
        (field (name "CASE") "SMT (0201)")
        (field (name "MANUFACTURER") "N/A")
        (field (name "MAXINV") "N/A")
        (field (name "MFG_PART_NUMBER") "N/A")
        (field (name "ORIGINALSYMBOLORIGIN") "(-75,50)")
        (field (name "PACK_TYPE") "0201_FF")
        (field (name "PHYS_PAGE") "3")
        (field (name "POWER_RATING") "N/A")
        (field (name "RES") "N/A")
        (field (name "TEMP_RANGE") "N/A")
        (field (name "TOLERANCE") "N/A")
        (field (name "VER") "2")
        (field (name "VLOG_PARAM01") "N/A")
      )
      (libsource (lib "eagle-import") (part "EK_RES_SMD"))
    )
    (comp (ref "R50")
      (value "0")
      (footprint "eagle-import:RESC0603X33M")
      (description "RES: SMT (0201): 0: 1%: JUMPER: 0.0500W")
      (fields
        (field (name "MANUFACTURER") "VISHAY DALE:PANASONIC")
        (field (name "MAXINV") "80-0000R-95")
        (field (name "ORIGINALSYMBOLORIGIN") "(-75,50)")
        (field (name "PACK_TYPE") "0201RES")
        (field (name "PHYS_PAGE") "3")
        (field (name "POWER_RATING") "0.05W")
        (field (name "RES") "0.00000001E00")
        (field (name "TEMP_RANGE") "-55 DEGC TO +155 DEGC")
        (field (name "TOLERANCE") "1%")
        (field (name "VER") "2")
        (field (name "VLOG_PARAM01") "RES:INTEGER")
      )
      (libsource (lib "eagle-import") (part "RES_SMDRES_SMD_1"))
    )
    (comp (ref "R51")
      (value "0")
      (footprint "eagle-import:RESC0603X33M")
      (description "RES: SMT (0201): 0: 1%: JUMPER: 0.0500W")
      (fields
        (field (name "MANUFACTURER") "VISHAY DALE:PANASONIC")
        (field (name "MAXINV") "80-0000R-95")
        (field (name "ORIGINALSYMBOLORIGIN") "(-75,50)")
        (field (name "PACK_TYPE") "0201RES")
        (field (name "PHYS_PAGE") "3")
        (field (name "POWER_RATING") "0.05W")
        (field (name "RES") "0.00000001E00")
        (field (name "TEMP_RANGE") "-55 DEGC TO +155 DEGC")
        (field (name "TOLERANCE") "1%")
        (field (name "VER") "2")
        (field (name "VLOG_PARAM01") "RES:INTEGER")
      )
      (libsource (lib "eagle-import") (part "RES_SMDRES_SMD_1"))
    )
    (comp (ref "R52")
      (value "OPEN")
      (footprint "eagle-import:RESC0603X23L")
      (description "RESISTOR: 0201: OPEN: FORMFACTOR")
      (fields
        (field (name "CASE") "SMT (0201)")
        (field (name "MANUFACTURER") "N/A")
        (field (name "MAXINV") "N/A")
        (field (name "MFG_PART_NUMBER") "N/A")
        (field (name "ORIGINALSYMBOLORIGIN") "(-75,50)")
        (field (name "PACK_TYPE") "0201_FF")
        (field (name "PHYS_PAGE") "3")
        (field (name "POWER_RATING") "N/A")
        (field (name "RES") "N/A")
        (field (name "TEMP_RANGE") "N/A")
        (field (name "TOLERANCE") "N/A")
        (field (name "VER") "2")
        (field (name "VLOG_PARAM01") "N/A")
      )
      (libsource (lib "eagle-import") (part "EK_RES_SMD"))
    )
    (comp (ref "R53")
      (value "0")
      (footprint "eagle-import:RESC0603X33M")
      (description "RES: SMT (0201): 0: 1%: JUMPER: 0.0500W")
      (fields
        (field (name "MANUFACTURER") "VISHAY DALE:PANASONIC")
        (field (name "MAXINV") "80-0000R-95")
        (field (name "ORIGINALSYMBOLORIGIN") "(-75,50)")
        (field (name "PACK_TYPE") "0201RES")
        (field (name "PHYS_PAGE") "3")
        (field (name "POWER_RATING") "0.05W")
        (field (name "RES") "0.00000001E00")
        (field (name "TEMP_RANGE") "-55 DEGC TO +155 DEGC")
        (field (name "TOLERANCE") "1%")
        (field (name "VER") "2")
        (field (name "VLOG_PARAM01") "RES:INTEGER")
      )
      (libsource (lib "eagle-import") (part "RES_SMDRES_SMD_1"))
    )
    (comp (ref "R54")
      (value "0")
      (footprint "eagle-import:RESC0603X33M")
      (description "RES: SMT (0201): 0: 1%: JUMPER: 0.0500W")
      (fields
        (field (name "MANUFACTURER") "VISHAY DALE:PANASONIC")
        (field (name "MAXINV") "80-0000R-95")
        (field (name "ORIGINALSYMBOLORIGIN") "(-75,50)")
        (field (name "PACK_TYPE") "0201RES")
        (field (name "PHYS_PAGE") "3")
        (field (name "POWER_RATING") "0.05W")
        (field (name "RES") "0.00000001E00")
        (field (name "TEMP_RANGE") "-55 DEGC TO +155 DEGC")
        (field (name "TOLERANCE") "1%")
        (field (name "VER") "2")
        (field (name "VLOG_PARAM01") "RES:INTEGER")
      )
      (libsource (lib "eagle-import") (part "RES_SMDRES_SMD_1"))
    )
    (comp (ref "R55")
      (value "0")
      (footprint "eagle-import:RESC0603X33M")
      (description "RES: SMT (0201): 0: 1%: JUMPER: 0.0500W")
      (fields
        (field (name "MANUFACTURER") "VISHAY DALE:PANASONIC")
        (field (name "MAXINV") "80-0000R-95")
        (field (name "ORIGINALSYMBOLORIGIN") "(-75,50)")
        (field (name "PACK_TYPE") "0201RES")
        (field (name "PHYS_PAGE") "3")
        (field (name "POWER_RATING") "0.05W")
        (field (name "RES") "0.00000001E00")
        (field (name "TEMP_RANGE") "-55 DEGC TO +155 DEGC")
        (field (name "TOLERANCE") "1%")
        (field (name "VER") "2")
        (field (name "VLOG_PARAM01") "RES:INTEGER")
      )
      (libsource (lib "eagle-import") (part "RES_SMDRES_SMD_1"))
    )
    (comp (ref "R56")
      (value "0")
      (footprint "eagle-import:RESC0603X33M")
      (description "RES: SMT (0201): 0: 1%: JUMPER: 0.0500W")
      (fields
        (field (name "MANUFACTURER") "VISHAY DALE:PANASONIC")
        (field (name "MAXINV") "80-0000R-95")
        (field (name "ORIGINALSYMBOLORIGIN") "(-75,50)")
        (field (name "PACK_TYPE") "0201RES")
        (field (name "PHYS_PAGE") "3")
        (field (name "POWER_RATING") "0.05W")
        (field (name "RES") "0.00000001E00")
        (field (name "TEMP_RANGE") "-55 DEGC TO +155 DEGC")
        (field (name "TOLERANCE") "1%")
        (field (name "VER") "2")
        (field (name "VLOG_PARAM01") "RES:INTEGER")
      )
      (libsource (lib "eagle-import") (part "RES_SMDRES_SMD_1"))
    )
    (comp (ref "R57")
      (value "0")
      (footprint "eagle-import:RESC0603X33M")
      (description "RES: SMT (0201): 0: 1%: JUMPER: 0.0500W")
      (fields
        (field (name "MANUFACTURER") "VISHAY DALE:PANASONIC")
        (field (name "MAXINV") "80-0000R-95")
        (field (name "ORIGINALSYMBOLORIGIN") "(-75,50)")
        (field (name "PACK_TYPE") "0201RES")
        (field (name "PHYS_PAGE") "3")
        (field (name "POWER_RATING") "0.05W")
        (field (name "RES") "0.00000001E00")
        (field (name "TEMP_RANGE") "-55 DEGC TO +155 DEGC")
        (field (name "TOLERANCE") "1%")
        (field (name "VER") "2")
        (field (name "VLOG_PARAM01") "RES:INTEGER")
      )
      (libsource (lib "eagle-import") (part "RES_SMDRES_SMD_1"))
    )
    (comp (ref "R58")
      (value "0")
      (footprint "eagle-import:RESC0603X33M")
      (description "RES: SMT (0201): 0: 1%: JUMPER: 0.0500W")
      (fields
        (field (name "MANUFACTURER") "VISHAY DALE:PANASONIC")
        (field (name "MAXINV") "80-0000R-95")
        (field (name "ORIGINALSYMBOLORIGIN") "(-75,50)")
        (field (name "PACK_TYPE") "0201RES")
        (field (name "PHYS_PAGE") "3")
        (field (name "POWER_RATING") "0.05W")
        (field (name "RES") "0.00000001E00")
        (field (name "TEMP_RANGE") "-55 DEGC TO +155 DEGC")
        (field (name "TOLERANCE") "1%")
        (field (name "VER") "2")
        (field (name "VLOG_PARAM01") "RES:INTEGER")
      )
      (libsource (lib "eagle-import") (part "RES_SMDRES_SMD_1"))
    )
    (comp (ref "R59")
      (value "0")
      (footprint "eagle-import:RESC0603X33M")
      (description "RES: SMT (0201): 0: 1%: JUMPER: 0.0500W")
      (fields
        (field (name "MANUFACTURER") "VISHAY DALE:PANASONIC")
        (field (name "MAXINV") "80-0000R-95")
        (field (name "ORIGINALSYMBOLORIGIN") "(-75,50)")
        (field (name "PACK_TYPE") "0201RES")
        (field (name "PHYS_PAGE") "3")
        (field (name "POWER_RATING") "0.05W")
        (field (name "RES") "0.00000001E00")
        (field (name "TEMP_RANGE") "-55 DEGC TO +155 DEGC")
        (field (name "TOLERANCE") "1%")
        (field (name "VER") "2")
        (field (name "VLOG_PARAM01") "RES:INTEGER")
      )
      (libsource (lib "eagle-import") (part "RES_SMDRES_SMD_1"))
    )
    (comp (ref "R60")
      (value "OPEN")
      (footprint "eagle-import:RESC0603X23L")
      (description "RESISTOR: 0201: OPEN: FORMFACTOR")
      (fields
        (field (name "CASE") "SMT (0201)")
        (field (name "MANUFACTURER") "N/A")
        (field (name "MAXINV") "N/A")
        (field (name "MFG_PART_NUMBER") "N/A")
        (field (name "ORIGINALSYMBOLORIGIN") "(-75,50)")
        (field (name "PACK_TYPE") "0201_FF")
        (field (name "PHYS_PAGE") "3")
        (field (name "POWER_RATING") "N/A")
        (field (name "RES") "N/A")
        (field (name "TEMP_RANGE") "N/A")
        (field (name "TOLERANCE") "N/A")
        (field (name "VER") "2")
        (field (name "VLOG_PARAM01") "N/A")
      )
      (libsource (lib "eagle-import") (part "EK_RES_SMD"))
    )
    (comp (ref "R61")
      (value "0")
      (footprint "eagle-import:RESC0603X33M")
      (description "RES: SMT (0201): 0: 1%: JUMPER: 0.0500W")
      (fields
        (field (name "MANUFACTURER") "VISHAY DALE:PANASONIC")
        (field (name "MAXINV") "80-0000R-95")
        (field (name "ORIGINALSYMBOLORIGIN") "(-75,50)")
        (field (name "PACK_TYPE") "0201RES")
        (field (name "PHYS_PAGE") "3")
        (field (name "POWER_RATING") "0.05W")
        (field (name "RES") "0.00000001E00")
        (field (name "TEMP_RANGE") "-55 DEGC TO +155 DEGC")
        (field (name "TOLERANCE") "1%")
        (field (name "VER") "2")
        (field (name "VLOG_PARAM01") "RES:INTEGER")
      )
      (libsource (lib "eagle-import") (part "RES_SMDRES_SMD_1"))
    )
    (comp (ref "R62")
      (value "0")
      (footprint "eagle-import:RESC0603X33M")
      (description "RES: SMT (0201): 0: 1%: JUMPER: 0.0500W")
      (fields
        (field (name "MANUFACTURER") "VISHAY DALE:PANASONIC")
        (field (name "MAXINV") "80-0000R-95")
        (field (name "ORIGINALSYMBOLORIGIN") "(-75,50)")
        (field (name "PACK_TYPE") "0201RES")
        (field (name "PHYS_PAGE") "3")
        (field (name "POWER_RATING") "0.05W")
        (field (name "RES") "0.00000001E00")
        (field (name "TEMP_RANGE") "-55 DEGC TO +155 DEGC")
        (field (name "TOLERANCE") "1%")
        (field (name "VER") "2")
        (field (name "VLOG_PARAM01") "RES:INTEGER")
      )
      (libsource (lib "eagle-import") (part "RES_SMDRES_SMD_1"))
    )
    (comp (ref "R63")
      (value "OPEN")
      (footprint "eagle-import:RESC0603X23L")
      (description "RESISTOR: 0201: OPEN: FORMFACTOR")
      (fields
        (field (name "CASE") "SMT (0201)")
        (field (name "MANUFACTURER") "N/A")
        (field (name "MAXINV") "N/A")
        (field (name "MFG_PART_NUMBER") "N/A")
        (field (name "ORIGINALSYMBOLORIGIN") "(-75,50)")
        (field (name "PACK_TYPE") "0201_FF")
        (field (name "PHYS_PAGE") "3")
        (field (name "POWER_RATING") "N/A")
        (field (name "RES") "N/A")
        (field (name "TEMP_RANGE") "N/A")
        (field (name "TOLERANCE") "N/A")
        (field (name "VER") "2")
        (field (name "VLOG_PARAM01") "N/A")
      )
      (libsource (lib "eagle-import") (part "EK_RES_SMD"))
    )
    (comp (ref "R64")
      (value "0")
      (footprint "eagle-import:RESC0603X33M")
      (description "RES: SMT (0201): 0: 1%: JUMPER: 0.0500W")
      (fields
        (field (name "MANUFACTURER") "VISHAY DALE:PANASONIC")
        (field (name "MAXINV") "80-0000R-95")
        (field (name "ORIGINALSYMBOLORIGIN") "(-75,50)")
        (field (name "PACK_TYPE") "0201RES")
        (field (name "PHYS_PAGE") "3")
        (field (name "POWER_RATING") "0.05W")
        (field (name "RES") "0.00000001E00")
        (field (name "TEMP_RANGE") "-55 DEGC TO +155 DEGC")
        (field (name "TOLERANCE") "1%")
        (field (name "VER") "2")
        (field (name "VLOG_PARAM01") "RES:INTEGER")
      )
      (libsource (lib "eagle-import") (part "RES_SMDRES_SMD_1"))
    )
    (comp (ref "SW1")
      (value "434153017835")
      (footprint "eagle-import:SW_434153017835")
      (description "SWITCH: SPST: SMT: 12V: 0.05A:WS-TASV J-BEND TACT SWITCH: RCONTACT=0.1 OHM: RINSULATION=100M OHM")
      (fields
        (field (name "MANUFACTURER") "WURTH ELECTRONICS INC")
        (field (name "MAXINV") "EH111000004113")
        (field (name "MFG_PART_NUMBER") "434153017835")
        (field (name "ORIGINALSYMBOLORIGIN") "(-225,75)")
        (field (name "PACK_TYPE") "SMT")
        (field (name "PHYS_PAGE") "3")
        (field (name "SEC_TYPE") "SMT")
        (field (name "TEMP_RANGE") "-40 DEGC TO +85 DEGC")
        (field (name "TOLERANCE") "N/A")
        (field (name "VER") "1")
        (field (name "VOLTAGE_RATING") "+12V")
      )
      (libsource (lib "eagle-import") (part "434153017835"))
    )
    (comp (ref "U3")
      (value "MX25U51245GZ4I54")
      (footprint "eagle-import:SON127P600X800X80-9M")
      (description "IC: MMRY: CMOS MXSMIO: SERIAL MULTI I/O: FLASH MEMORY: WSON8-EP")
      (fields
        (field (name "CASE") "WSON8-EP")
        (field (name "MANUFACTURER") "MACRONIX INTERNATIONAL CO LTD")
        (field (name "MAXINV") "EQ111000004114")
        (field (name "MFG_PART_NUMBER") "MX25U51245GZ4I54")
        (field (name "ORIGINALSYMBOLORIGIN") "(-300,450)")
        (field (name "PACK_TYPE") "WSON8-EP")
        (field (name "PHYS_PAGE") "3")
        (field (name "SEC_TYPE") "WSON8-EP")
        (field (name "TEMP_RANGE") "-40 DEGC TO +85 DEGC")
        (field (name "TOLERANCE") "N/A")
        (field (name "VER") "1")
        (field (name "VOLTAGE_RATING") "+1.65V TO +2.0V")
      )
      (libsource (lib "eagle-import") (part "MX25U51245G_54"))
    )
    (comp (ref "U5")
      (value "MAX32666GXMBT+")
      (footprint "eagle-import:MAXIM_21-0680")
      (description "IC: UCON: LOW-POWER ARM CORTEX-M4 WITH FPU-BASED: MICROCONTROLLER WITH BLUETOOTH 5 FOR WEARABLES: BGA121")
      (fields
        (field (name "CASE") "BGA121")
        (field (name "MANUFACTURER") "MAXIM")
        (field (name "MAXINV") "10-MAX32666GXMBT-B")
        (field (name "MFG_PART_NUMBER") "MAX32666GXMBT+")
        (field (name "ORIGINALSYMBOLORIGIN") "(-1250,2950)")
        (field (name "PACK_TYPE") "BGA121")
        (field (name "PHYS_PAGE") "3")
        (field (name "SEC_TYPE") "BGA121")
        (field (name "TEMP_RANGE") "-40 DEGC TO +105 DEGC")
        (field (name "TOLERANCE") "N/A")
        (field (name "VER") "4")
        (field (name "VOLTAGE_RATING") "+1.1V")
      )
      (libsource (lib "eagle-import") (part "MAX32666"))
    )
    (comp (ref "Y1")
      (value "32.768KHZ")
      (footprint "eagle-import:XTAL320X150X90M")
      (description "CRYSTAL: SMT: 6PF: 32.768KHZ: +/-20PPM: -0.036PPM/T2")
      (fields
        (field (name "MANUFACTURER") "ABRACON")
        (field (name "MAXINV") "60-32K76-0AL")
        (field (name "MFG_PART_NUMBER") "ABS07-32.768KHZ-6-T")
        (field (name "ORIGINALSYMBOLORIGIN") "(-50,50)")
        (field (name "PACK_TYPE") "ABS07")
        (field (name "PHYS_PAGE") "3")
        (field (name "SEC_TYPE") "ABS07")
        (field (name "TEMP_RANGE") "-40 DEGC TO +85 DEGC")
        (field (name "TOLERANCE") "N/A")
        (field (name "VER") "1")
        (field (name "VOLTAGE_RATING") "N/A")
      )
      (libsource (lib "eagle-import") (part "XTAL#1"))
    )
    (comp (ref "Y2")
      (value "32MHZ")
      (footprint "eagle-import:OSCCC250X200X55M")
      (description "CRYSTAL: SMT 2.5MMX2MM: 32MHZ: +/-10PPM: +/-12PPM")
      (fields
        (field (name "MANUFACTURER") "EPSON")
        (field (name "MAXINV") "60-0032M-0EW")
        (field (name "MFG_PART_NUMBER") "FA-20H 32.0000MF12Y-W3")
        (field (name "ORIGINALSYMBOLORIGIN") "(-75,125)")
        (field (name "PACK_TYPE") "XTAL_FA-20H")
        (field (name "PHYS_PAGE") "3")
        (field (name "SEC_TYPE") "XTAL_FA-20H")
        (field (name "TEMP_RANGE") "-40 DEGC TO +85 DEGC")
        (field (name "TOLERANCE") "N/A")
        (field (name "VER") "4")
        (field (name "VOLTAGE_RATING") "N/A")
      )
      (libsource (lib "eagle-import") (part "XTAL#2"))
    )
    (comp (ref "B+")
      (value "N/A")
      (footprint "eagle-import:KEYS_5001")
      (description "TEST POINT: PIN DIA=0.1IN: TOTAL LENGTH=0.3IN: BOARD HOLE=0.04IN: BLACK: PHOSPHOR BRONZE WIRE SILVER PLATE FINISH: RECOMMENDED FOR BOARD THICKNESS=0.062IN: NOT FOR COLD TEST")
      (fields
        (field (name "MANUFACTURER") "KEYSTONE")
        (field (name "MAXINV") "02-TPMINI5001-00")
        (field (name "MFG_PART_NUMBER") "5001")
        (field (name "ORIGINALSYMBOLORIGIN") "(-125,50)")
        (field (name "PACK_TYPE") "TP")
        (field (name "PART_NAME") "TP")
        (field (name "PHYS_PAGE") "1")
        (field (name "REFLOW") "-")
        (field (name "TEMP_RANGE") "N/A")
        (field (name "TOLERANCE") "N/A")
        (field (name "VARIANT") "DNI")
        (field (name "VER") "1")
        (field (name "VOLTAGE_RATING") "N/A")
      )
      (libsource (lib "eagle-import") (part "TP"))
    )
    (comp (ref "B-")
      (value "N/A")
      (footprint "eagle-import:KEYS_5001")
      (description "TEST POINT: PIN DIA=0.1IN: TOTAL LENGTH=0.3IN: BOARD HOLE=0.04IN: BLACK: PHOSPHOR BRONZE WIRE SILVER PLATE FINISH: RECOMMENDED FOR BOARD THICKNESS=0.062IN: NOT FOR COLD TEST")
      (fields
        (field (name "MANUFACTURER") "KEYSTONE")
        (field (name "MAXINV") "02-TPMINI5001-00")
        (field (name "MFG_PART_NUMBER") "5001")
        (field (name "ORIGINALSYMBOLORIGIN") "(-125,50)")
        (field (name "PACK_TYPE") "TP")
        (field (name "PART_NAME") "TP")
        (field (name "PHYS_PAGE") "1")
        (field (name "REFLOW") "-")
        (field (name "TEMP_RANGE") "N/A")
        (field (name "TOLERANCE") "N/A")
        (field (name "VARIANT") "DNI")
        (field (name "VER") "1")
        (field (name "VOLTAGE_RATING") "N/A")
      )
      (libsource (lib "eagle-import") (part "TP"))
    )
    (comp (ref "C1")
      (value "0.1UF")
      (footprint "eagle-import:0402")
      (description "CAP: SMT (0402): 0.1UF: 10%: 50V: X7R: CERAMIC")
      (fields
        (field (name "CAP") "1.00E-07")
        (field (name "CASE") "SMT (0402)")
        (field (name "MANUFACTURER") "TDK:MURATA:TDK:TAIYO YUDEN")
        (field (name "MATERIAL_TYPE") "CERAMIC CHIP")
        (field (name "MAXINV") "20-000U1-04A")
        (field (name "MFG_PART_NUMBER") "CGA2B3X7R1H104K050BB:C1005X7R1H104K050BB:GRM155R71H104KE14:GCM155R71H104KE02:C1005X7R1H104K050BE:UMK105B7104KV-FR:CGA2B3X7R1H104K050BE")
        (field (name "ORIGINALSYMBOLORIGIN") "(-50,50)")
        (field (name "PACK_TYPE") "0402CAP")
        (field (name "PHYS_PAGE") "1")
        (field (name "REFLOW") "-")
        (field (name "TEMP_RANGE") "-55 DEGC TO +125 DEGC")
        (field (name "TOLERANCE") "10%")
        (field (name "VER") "2")
        (field (name "VLOG_PARAM01") "CAP:INTEGER")
        (field (name "VOLTAGE_RATING") "50V")
      )
      (libsource (lib "eagle-import") (part "CAP_NPCAP_NP_2"))
    )
    (comp (ref "C2")
      (value "2.2UF")
      (footprint "eagle-import:0402")
      (description "CAP: SMT (0402): 2.2UF: 10%: 35V: X5R: CERAMIC")
      (fields
        (field (name "CAP") "2.20E-06")
        (field (name "CASE") "SMT (0402)")
        (field (name "MANUFACTURER") "TDK")
        (field (name "MATERIAL_TYPE") "CERAMIC CHIP")
        (field (name "MAXINV") "EC111000002275")
        (field (name "MFG_PART_NUMBER") "C1005X5R1V225K050BC")
        (field (name "ORIGINALSYMBOLORIGIN") "(-50,50)")
        (field (name "PACK_TYPE") "0402CAP")
        (field (name "PHYS_PAGE") "1")
        (field (name "REFLOW") "-")
        (field (name "TEMP_RANGE") "-55 DEGC TO +85 DEGC")
        (field (name "TOLERANCE") "10%")
        (field (name "VER") "2")
        (field (name "VLOG_PARAM01") "CAP:INTEGER")
        (field (name "VOLTAGE_RATING") "35V")
      )
      (libsource (lib "eagle-import") (part "CAP_NPCAP_NP_2"))
    )
    (comp (ref "C3")
      (value "4.7UF")
      (footprint "eagle-import:0402")
      (description "CAP: SMT (0402): 4.7UF: 10%: 6.3V: X5R: CERAMIC")
      (fields
        (field (name "CAP") "4.70E-06")
        (field (name "CASE") "SMT (0402)")
        (field (name "MANUFACTURER") "TDK")
        (field (name "MATERIAL_TYPE") "CERAMIC CHIP")
        (field (name "MAXINV") "20-004U7-19")
        (field (name "MFG_PART_NUMBER") "C1005X5R0J475K050BC")
        (field (name "ORIGINALSYMBOLORIGIN") "(-50,50)")
        (field (name "PACK_TYPE") "0402CAP")
        (field (name "PHYS_PAGE") "1")
        (field (name "REFLOW") "-")
        (field (name "TEMP_RANGE") "-55 DEGC TO +85 DEGC")
        (field (name "TOLERANCE") "10%")
        (field (name "VER") "1")
        (field (name "VLOG_PARAM01") "CAP:INTEGER")
        (field (name "VOLTAGE_RATING") "6.3V")
      )
      (libsource (lib "eagle-import") (part "CAP_NP#1CAP_NP#1_1"))
    )
    (comp (ref "C4")
      (value "2.2UF")
      (footprint "eagle-import:0402")
      (description "CAP: SMT (0402): 2.2UF: 10%: 6.3V: X5R: CERAMIC")
      (fields
        (field (name "CAP") "2.20E-06")
        (field (name "CASE") "SMT (0402)")
        (field (name "MANUFACTURER") "TDK:SAMSUNG")
        (field (name "MATERIAL_TYPE") "CERAMIC CHIP")
        (field (name "MAXINV") "20-002U2-19")
        (field (name "MFG_PART_NUMBER") "C1005X5R0J225K050BC:CL05A225KQ5NSN")
        (field (name "ORIGINALSYMBOLORIGIN") "(-50,50)")
        (field (name "PACK_TYPE") "0402CAP")
        (field (name "PHYS_PAGE") "1")
        (field (name "REFLOW") "-")
        (field (name "TEMP_RANGE") "-55 DEGC TO +85 DEGC")
        (field (name "TOLERANCE") "10%")
        (field (name "VER") "2")
        (field (name "VLOG_PARAM01") "CAP:INTEGER")
        (field (name "VOLTAGE_RATING") "6.3V")
      )
      (libsource (lib "eagle-import") (part "CAP_NPCAP_NP_2"))
    )
    (comp (ref "C5")
      (value "4.7UF")
      (footprint "eagle-import:0402")
      (description "CAP: SMT (0402): 4.7UF: 10%: 6.3V: X5R: CERAMIC")
      (fields
        (field (name "CAP") "4.70E-06")
        (field (name "CASE") "SMT (0402)")
        (field (name "MANUFACTURER") "TDK")
        (field (name "MATERIAL_TYPE") "CERAMIC CHIP")
        (field (name "MAXINV") "20-004U7-19")
        (field (name "MFG_PART_NUMBER") "C1005X5R0J475K050BC")
        (field (name "ORIGINALSYMBOLORIGIN") "(-50,50)")
        (field (name "PACK_TYPE") "0402CAP")
        (field (name "PHYS_PAGE") "1")
        (field (name "REFLOW") "-")
        (field (name "TEMP_RANGE") "-55 DEGC TO +85 DEGC")
        (field (name "TOLERANCE") "10%")
        (field (name "VER") "2")
        (field (name "VLOG_PARAM01") "CAP:INTEGER")
        (field (name "VOLTAGE_RATING") "6.3V")
      )
      (libsource (lib "eagle-import") (part "CAP_NPCAP_NP_2"))
    )
    (comp (ref "C8")
      (value "4.7UF")
      (footprint "eagle-import:0402")
      (description "CAP: SMT (0402): 4.7UF: 10%: 6.3V: X5R: CERAMIC")
      (fields
        (field (name "CAP") "4.70E-06")
        (field (name "CASE") "SMT (0402)")
        (field (name "MANUFACTURER") "TDK")
        (field (name "MATERIAL_TYPE") "CERAMIC CHIP")
        (field (name "MAXINV") "20-004U7-19")
        (field (name "MFG_PART_NUMBER") "C1005X5R0J475K050BC")
        (field (name "ORIGINALSYMBOLORIGIN") "(-50,50)")
        (field (name "PACK_TYPE") "0402CAP")
        (field (name "PHYS_PAGE") "1")
        (field (name "REFLOW") "-")
        (field (name "TEMP_RANGE") "-55 DEGC TO +85 DEGC")
        (field (name "TOLERANCE") "10%")
        (field (name "VER") "2")
        (field (name "VLOG_PARAM01") "CAP:INTEGER")
        (field (name "VOLTAGE_RATING") "6.3V")
      )
      (libsource (lib "eagle-import") (part "CAP_NPCAP_NP_2"))
    )
    (comp (ref "C9")
      (value "10UF")
      (footprint "eagle-import:0603")
      (description "CAP: SMT (0603): 10UF: 20%: 25V: X5R: CERAMIC")
      (fields
        (field (name "CAP") "1.00E-05")
        (field (name "CASE") "SMT (0603)")
        (field (name "COMMENTS") "USE ONLY GRM188R61E106MA73")
        (field (name "MANUFACTURER") "TDK:SAMSUNG ELECTRONICS:MURATA::MURATA")
        (field (name "MATERIAL_TYPE") "CERAMIC CHIP")
        (field (name "MAXINV") "20-0010U-P7")
        (field (name "MFG_PART_NUMBER") "C1608X5R1E106M080AC:CL10A106MA8NRNC:GRM188R61E106MA73:ZRB18AR61E106ME01:GRT188R61E106ME13")
        (field (name "ORIGINALSYMBOLORIGIN") "(-50,50)")
        (field (name "PACK_TYPE") "0603CAP")
        (field (name "PHYS_PAGE") "1")
        (field (name "REFLOW") "-")
        (field (name "TEMP_RANGE") "-55 DEGC TO +85 DEGC")
        (field (name "TOLERANCE") "20%")
        (field (name "VER") "2")
        (field (name "VLOG_PARAM01") "CAP:INTEGER")
        (field (name "VOLTAGE_RATING") "25V")
      )
      (libsource (lib "eagle-import") (part "CAP_NPCAP_NP_3"))
    )
    (comp (ref "C10")
      (value "4.7UF")
      (footprint "eagle-import:0402")
      (description "CAP: SMT (0402): 4.7UF: 10%: 6.3V: X5R: CERAMIC")
      (fields
        (field (name "CAP") "4.70E-06")
        (field (name "CASE") "SMT (0402)")
        (field (name "MANUFACTURER") "TDK")
        (field (name "MATERIAL_TYPE") "CERAMIC CHIP")
        (field (name "MAXINV") "20-004U7-19")
        (field (name "MFG_PART_NUMBER") "C1005X5R0J475K050BC")
        (field (name "ORIGINALSYMBOLORIGIN") "(-50,50)")
        (field (name "PACK_TYPE") "0402CAP")
        (field (name "PHYS_PAGE") "1")
        (field (name "REFLOW") "-")
        (field (name "TEMP_RANGE") "-55 DEGC TO +85 DEGC")
        (field (name "TOLERANCE") "10%")
        (field (name "VER") "2")
        (field (name "VLOG_PARAM01") "CAP:INTEGER")
        (field (name "VOLTAGE_RATING") "6.3V")
      )
      (libsource (lib "eagle-import") (part "CAP_NPCAP_NP_2"))
    )
    (comp (ref "C39")
      (value "22UF")
      (footprint "eagle-import:0603")
      (description "CAP: SMT (0603): 22UF: 20%: 16V: X5R: CERAMIC")
      (fields
        (field (name "CAP") "2.20E-05")
        (field (name "CASE") "SMT (0603)")
        (field (name "MANUFACTURER") "SAMSUNG ELECTRONICS")
        (field (name "MAXINV") "20-0022U-A29")
        (field (name "MFG_PART_NUMBER") "CL10A226MO7JZNC")
        (field (name "ORIGINALSYMBOLORIGIN") "(-50,50)")
        (field (name "PACK_TYPE") "0603CAP")
        (field (name "PHYS_PAGE") "1")
        (field (name "TEMP_RANGE") "-55 DEGC TO +85 DEGC")
        (field (name "TOLERANCE") "20%")
        (field (name "VER") "2")
        (field (name "VLOG_PARAM01") "CAP:INTEGER")
        (field (name "VOLTAGE_RATING") "16V")
      )
      (libsource (lib "eagle-import") (part "CAP_NPCAP_NP_3"))
    )
    (comp (ref "C40")
      (value "10UF")
      (footprint "eagle-import:0603")
      (description "CAP: SMT (0603): 10UF: 20%: 25V: X5R: CERAMIC")
      (fields
        (field (name "CAP") "1.00E-05")
        (field (name "CASE") "SMT (0603)")
        (field (name "COMMENTS") "USE ONLY GRM188R61E106MA73")
        (field (name "MANUFACTURER") "TDK:SAMSUNG ELECTRONICS:MURATA::MURATA")
        (field (name "MATERIAL_TYPE") "CERAMIC CHIP")
        (field (name "MAXINV") "20-0010U-P7")
        (field (name "MFG_PART_NUMBER") "C1608X5R1E106M080AC:CL10A106MA8NRNC:GRM188R61E106MA73:ZRB18AR61E106ME01:GRT188R61E106ME13")
        (field (name "ORIGINALSYMBOLORIGIN") "(-50,50)")
        (field (name "PACK_TYPE") "0603CAP")
        (field (name "PHYS_PAGE") "1")
        (field (name "REFLOW") "-")
        (field (name "TEMP_RANGE") "-55 DEGC TO +85 DEGC")
        (field (name "TOLERANCE") "20%")
        (field (name "VER") "2")
        (field (name "VLOG_PARAM01") "CAP:INTEGER")
        (field (name "VOLTAGE_RATING") "25V")
      )
      (libsource (lib "eagle-import") (part "CAP_NPCAP_NP_3"))
    )
    (comp (ref "C41")
      (value "22UF")
      (footprint "eagle-import:0603")
      (description "CAP: SMT (0603): 22UF: 20%: 16V: X5R: CERAMIC")
      (fields
        (field (name "CAP") "2.20E-05")
        (field (name "CASE") "SMT (0603)")
        (field (name "MANUFACTURER") "SAMSUNG ELECTRONICS")
        (field (name "MAXINV") "20-0022U-A29")
        (field (name "MFG_PART_NUMBER") "CL10A226MO7JZNC")
        (field (name "ORIGINALSYMBOLORIGIN") "(-50,50)")
        (field (name "PACK_TYPE") "0603CAP")
        (field (name "PHYS_PAGE") "1")
        (field (name "TEMP_RANGE") "-55 DEGC TO +85 DEGC")
        (field (name "TOLERANCE") "20%")
        (field (name "VER") "2")
        (field (name "VLOG_PARAM01") "CAP:INTEGER")
        (field (name "VOLTAGE_RATING") "16V")
      )
      (libsource (lib "eagle-import") (part "CAP_NPCAP_NP_3"))
    )
    (comp (ref "C42")
      (value "10UF")
      (footprint "eagle-import:0603")
      (description "CAP: SMT (0603): 10UF: 20%: 25V: X5R: CERAMIC")
      (fields
        (field (name "CAP") "1.00E-05")
        (field (name "CASE") "SMT (0603)")
        (field (name "COMMENTS") "USE ONLY GRM188R61E106MA73")
        (field (name "MANUFACTURER") "TDK:SAMSUNG ELECTRONICS:MURATA::MURATA")
        (field (name "MATERIAL_TYPE") "CERAMIC CHIP")
        (field (name "MAXINV") "20-0010U-P7")
        (field (name "MFG_PART_NUMBER") "C1608X5R1E106M080AC:CL10A106MA8NRNC:GRM188R61E106MA73:ZRB18AR61E106ME01:GRT188R61E106ME13")
        (field (name "ORIGINALSYMBOLORIGIN") "(-50,50)")
        (field (name "PACK_TYPE") "0603CAP")
        (field (name "PHYS_PAGE") "1")
        (field (name "REFLOW") "-")
        (field (name "TEMP_RANGE") "-55 DEGC TO +85 DEGC")
        (field (name "TOLERANCE") "20%")
        (field (name "VER") "2")
        (field (name "VLOG_PARAM01") "CAP:INTEGER")
        (field (name "VOLTAGE_RATING") "25V")
      )
      (libsource (lib "eagle-import") (part "CAP_NPCAP_NP_3"))
    )
    (comp (ref "C43")
      (value "22UF")
      (footprint "eagle-import:0603")
      (description "CAP: SMT (0603): 22UF: 20%: 16V: X5R: CERAMIC")
      (fields
        (field (name "CAP") "2.20E-05")
        (field (name "CASE") "SMT (0603)")
        (field (name "MANUFACTURER") "SAMSUNG ELECTRONICS")
        (field (name "MAXINV") "20-0022U-A29")
        (field (name "MFG_PART_NUMBER") "CL10A226MO7JZNC")
        (field (name "ORIGINALSYMBOLORIGIN") "(-50,50)")
        (field (name "PACK_TYPE") "0603CAP")
        (field (name "PHYS_PAGE") "1")
        (field (name "TEMP_RANGE") "-55 DEGC TO +85 DEGC")
        (field (name "TOLERANCE") "20%")
        (field (name "VER") "2")
        (field (name "VLOG_PARAM01") "CAP:INTEGER")
        (field (name "VOLTAGE_RATING") "16V")
      )
      (libsource (lib "eagle-import") (part "CAP_NPCAP_NP_3"))
    )
    (comp (ref "C44")
      (value "10UF")
      (footprint "eagle-import:0603")
      (description "CAP: SMT (0603): 10UF: 20%: 25V: X5R: CERAMIC")
      (fields
        (field (name "CAP") "1.00E-05")
        (field (name "CASE") "SMT (0603)")
        (field (name "COMMENTS") "USE ONLY GRM188R61E106MA73")
        (field (name "MANUFACTURER") "TDK:SAMSUNG ELECTRONICS:MURATA::MURATA")
        (field (name "MATERIAL_TYPE") "CERAMIC CHIP")
        (field (name "MAXINV") "20-0010U-P7")
        (field (name "MFG_PART_NUMBER") "C1608X5R1E106M080AC:CL10A106MA8NRNC:GRM188R61E106MA73:ZRB18AR61E106ME01:GRT188R61E106ME13")
        (field (name "ORIGINALSYMBOLORIGIN") "(-50,50)")
        (field (name "PACK_TYPE") "0603CAP")
        (field (name "PHYS_PAGE") "1")
        (field (name "REFLOW") "-")
        (field (name "TEMP_RANGE") "-55 DEGC TO +85 DEGC")
        (field (name "TOLERANCE") "20%")
        (field (name "VER") "2")
        (field (name "VLOG_PARAM01") "CAP:INTEGER")
        (field (name "VOLTAGE_RATING") "25V")
      )
      (libsource (lib "eagle-import") (part "CAP_NPCAP_NP_3"))
    )
    (comp (ref "C50")
      (value "10UF")
      (footprint "eagle-import:0603")
      (description "CAP: SMT (0603): 10UF: 20%: 25V: X5R: CERAMIC")
      (fields
        (field (name "CAP") "1.00E-05")
        (field (name "CASE") "SMT (0603)")
        (field (name "COMMENTS") "USE ONLY GRM188R61E106MA73")
        (field (name "MANUFACTURER") "TDK:SAMSUNG ELECTRONICS:MURATA::MURATA")
        (field (name "MATERIAL_TYPE") "CERAMIC CHIP")
        (field (name "MAXINV") "20-0010U-P7")
        (field (name "MFG_PART_NUMBER") "C1608X5R1E106M080AC:CL10A106MA8NRNC:GRM188R61E106MA73:ZRB18AR61E106ME01:GRT188R61E106ME13")
        (field (name "ORIGINALSYMBOLORIGIN") "(-50,50)")
        (field (name "PACK_TYPE") "0603CAP")
        (field (name "PHYS_PAGE") "1")
        (field (name "REFLOW") "-")
        (field (name "TEMP_RANGE") "-55 DEGC TO +85 DEGC")
        (field (name "TOLERANCE") "20%")
        (field (name "VER") "2")
        (field (name "VLOG_PARAM01") "CAP:INTEGER")
        (field (name "VOLTAGE_RATING") "25V")
      )
      (libsource (lib "eagle-import") (part "CAP_NPCAP_NP_3"))
    )
    (comp (ref "C51")
      (value "10UF")
      (footprint "eagle-import:0603")
      (description "CAP: SMT (0603): 10UF: 20%: 25V: X5R: CERAMIC")
      (fields
        (field (name "CAP") "1.00E-05")
        (field (name "CASE") "SMT (0603)")
        (field (name "COMMENTS") "USE ONLY GRM188R61E106MA73")
        (field (name "MANUFACTURER") "TDK:SAMSUNG ELECTRONICS:MURATA::MURATA")
        (field (name "MATERIAL_TYPE") "CERAMIC CHIP")
        (field (name "MAXINV") "20-0010U-P7")
        (field (name "MFG_PART_NUMBER") "C1608X5R1E106M080AC:CL10A106MA8NRNC:GRM188R61E106MA73:ZRB18AR61E106ME01:GRT188R61E106ME13")
        (field (name "ORIGINALSYMBOLORIGIN") "(-50,50)")
        (field (name "PACK_TYPE") "0603CAP")
        (field (name "PHYS_PAGE") "1")
        (field (name "REFLOW") "-")
        (field (name "TEMP_RANGE") "-55 DEGC TO +85 DEGC")
        (field (name "TOLERANCE") "20%")
        (field (name "VER") "2")
        (field (name "VLOG_PARAM01") "CAP:INTEGER")
        (field (name "VOLTAGE_RATING") "25V")
      )
      (libsource (lib "eagle-import") (part "CAP_NPCAP_NP_3"))
    )
    (comp (ref "D1")
      (value "APFA2507QBDSEEZGKC")
      (footprint "eagle-import:LED_APFA2507")
      (description "DIODE: LED: BLUE-RED-GREEN: SMT: VF=BLUE:+3.3V:RED:+2V:GRN:+3.3V: IF=BLUE:0.02A:RED:0.02A:GRN:0.02A")
      (fields
        (field (name "MANUFACTURER") "KINGBRIGHT")
        (field (name "MAXINV") "ED1230")
        (field (name "MFG_PART_NUMBER") "APFA2507QBDSEEZGKC")
        (field (name "ORIGINALSYMBOLORIGIN") "(-150,275)")
        (field (name "PACK_TYPE") "SMT250X100X70_4P")
        (field (name "PHYS_PAGE") "1")
        (field (name "TEMP_RANGE") "-40 DEGC TO +85 DEGC")
        (field (name "TOLERANCE") "N/A")
        (field (name "VER") "6")
        (field (name "VOLTAGE_RATING") "BLUE:+3.3V:RED:+2V:GRN:+3.3V")
      )
      (libsource (lib "eagle-import") (part "LED_4P"))
    )
    (comp (ref "L1")
      (value "2.2UH")
      (footprint "eagle-import:IND_2016")
      (description "INDUCTOR: SMT (0806): WIREWOUND CHIP: 2.2UH: TOL=+/-20%: 1.8A")
      (fields
        (field (name "CASE") "SMT (0806)")
        (field (name "MANUFACTURER") "MURATA")
        (field (name "MATERIAL_TYPE") "WIREWOUND")
        (field (name "MAXINV") "50-002U2-0PD")
        (field (name "MFG_PART_NUMBER") "DFE201612E-2R2M")
        (field (name "ORIGINALSYMBOLORIGIN") "(-100,50)")
        (field (name "PACK_TYPE") "0806")
        (field (name "PHYS_PAGE") "1")
        (field (name "TEMP_RANGE") "-40 DEGC TO +125 DEGC")
        (field (name "TOLERANCE") "20%")
        (field (name "VER") "1")
      )
      (libsource (lib "eagle-import") (part "INDUCTINDUCT_1"))
    )
    (comp (ref "L2")
      (value "2.2UH")
      (footprint "eagle-import:IND_2016")
      (description "INDUCTOR: SMT (0806): WIREWOUND CHIP: 2.2UH: TOL=+/-20%: 1.8A")
      (fields
        (field (name "CASE") "SMT (0806)")
        (field (name "MANUFACTURER") "MURATA")
        (field (name "MATERIAL_TYPE") "WIREWOUND")
        (field (name "MAXINV") "50-002U2-0PD")
        (field (name "MFG_PART_NUMBER") "DFE201612E-2R2M")
        (field (name "ORIGINALSYMBOLORIGIN") "(-100,50)")
        (field (name "PACK_TYPE") "0806")
        (field (name "PHYS_PAGE") "1")
        (field (name "TEMP_RANGE") "-40 DEGC TO +125 DEGC")
        (field (name "TOLERANCE") "20%")
        (field (name "VER") "1")
      )
      (libsource (lib "eagle-import") (part "INDUCTINDUCT_1"))
    )
    (comp (ref "L3")
      (value "2.2UH")
      (footprint "eagle-import:IND_2016")
      (description "INDUCTOR: SMT (0806): WIREWOUND CHIP: 2.2UH: TOL=+/-20%: 1.8A")
      (fields
        (field (name "CASE") "SMT (0806)")
        (field (name "MANUFACTURER") "MURATA")
        (field (name "MATERIAL_TYPE") "WIREWOUND")
        (field (name "MAXINV") "50-002U2-0PD")
        (field (name "MFG_PART_NUMBER") "DFE201612E-2R2M")
        (field (name "ORIGINALSYMBOLORIGIN") "(-100,50)")
        (field (name "PACK_TYPE") "0806")
        (field (name "PHYS_PAGE") "1")
        (field (name "TEMP_RANGE") "-40 DEGC TO +125 DEGC")
        (field (name "TOLERANCE") "20%")
        (field (name "VER") "1")
      )
      (libsource (lib "eagle-import") (part "INDUCTINDUCT_1"))
    )
    (comp (ref "L5")
      (value "2.2UH")
      (footprint "eagle-import:IND_2016")
      (description "INDUCTOR: SMT (0806): WIREWOUND CHIP: 2.2UH: TOL=+/-20%: 1.8A")
      (fields
        (field (name "CASE") "SMT (0806)")
        (field (name "MANUFACTURER") "MURATA")
        (field (name "MATERIAL_TYPE") "WIREWOUND")
        (field (name "MAXINV") "50-002U2-0PD")
        (field (name "MFG_PART_NUMBER") "DFE201612E-2R2M")
        (field (name "ORIGINALSYMBOLORIGIN") "(-100,50)")
        (field (name "PACK_TYPE") "0806")
        (field (name "PHYS_PAGE") "1")
        (field (name "TEMP_RANGE") "-40 DEGC TO +125 DEGC")
        (field (name "TOLERANCE") "20%")
        (field (name "VER") "1")
      )
      (libsource (lib "eagle-import") (part "INDUCTINDUCT_1"))
    )
    (comp (ref "R14")
      (value "10K")
      (footprint "eagle-import:0402")
      (description "RES: SMT (0402): 10K: 5%: +/-200PPM/DEGC: 0.1000W")
      (fields
        (field (name "CASE") "SMT (0402)")
        (field (name "MANUFACTURER") "PANASONIC")
        (field (name "MATERIAL_TYPE") "THICK FILM")
        (field (name "MAXINV") "80-0010K-Q6")
        (field (name "MFG_PART_NUMBER") "ERJ-2GEJ103")
        (field (name "ORIGINALSYMBOLORIGIN") "(-50,75)")
        (field (name "PACK_TYPE") "0402RES")
        (field (name "PHYS_PAGE") "1")
        (field (name "POWER_RATING") "0.10W")
        (field (name "REFLOW") "-")
        (field (name "RES") "1.00E04")
        (field (name "TEMP_RANGE") "-55 DEGC TO +155 DEGC")
        (field (name "TOLERANCE") "5%")
        (field (name "VER") "4")
        (field (name "VLOG_PARAM01") "RES:INTEGER")
      )
      (libsource (lib "eagle-import") (part "RES_SMD#1RES_SMD#1_1"))
    )
    (comp (ref "R15")
      (value "0.01")
      (footprint "eagle-import:0402")
      (description "RES: SMT (0402): 0.01: 1%: 0 TO +500PPM/DEGC: 0.2000W")
      (fields
        (field (name "CASE") "SMT (0402)")
        (field (name "MANUFACTURER") "PANASONIC")
        (field (name "MATERIAL_TYPE") "THICK FILM")
        (field (name "MAXINV") "ER111000002587")
        (field (name "MFG_PART_NUMBER") "ERJ-2LWFR010")
        (field (name "ORIGINALSYMBOLORIGIN") "(-50,75)")
        (field (name "PACK_TYPE") "0402RES")
        (field (name "PHYS_PAGE") "1")
        (field (name "POWER_RATING") "0.2W")
        (field (name "REFLOW") "-")
        (field (name "RES") "1.00E-02")
        (field (name "TEMP_RANGE") "-55 DEGC TO +125 DEGC")
        (field (name "TOLERANCE") "1%")
        (field (name "VER") "4")
        (field (name "VLOG_PARAM01") "RES:INTEGER")
      )
      (libsource (lib "eagle-import") (part "RES_SMD#1RES_SMD#1_1"))
    )
    (comp (ref "R43")
      (value "4.7K")
      (footprint "eagle-import:0402")
      (description "RES: SMT (0402): 4.7K: 1%: +/-100PPM/DEGC: 0.0630W")
      (fields
        (field (name "CASE") "SMT (0402)")
        (field (name "MANUFACTURER") "VISHAY DALE:ROHM SEMICONDUCTOR")
        (field (name "MATERIAL_TYPE") "THICK FILM")
        (field (name "MAXINV") "80-004K7-23")
        (field (name "MFG_PART_NUMBER") "CRCW04024K70FK:MCR01MZPF4701")
        (field (name "ORIGINALSYMBOLORIGIN") "(-75,50)")
        (field (name "PACK_TYPE") "0402RES")
        (field (name "PHYS_PAGE") "1")
        (field (name "POWER_RATING") "N/A")
        (field (name "REFLOW") "-")
        (field (name "RES") "4.70E03")
        (field (name "TEMP_RANGE") "-55 DEGC TO +155 DEGC")
        (field (name "TOLERANCE") "1%")
        (field (name "VER") "2")
        (field (name "VLOG_PARAM01") "RES:INTEGER")
      )
      (libsource (lib "eagle-import") (part "RES_SMDRES_SMD_2"))
    )
    (comp (ref "R65")
      (value "10K")
      (footprint "eagle-import:0402")
      (description "RES: SMT (0402): 10K: 1%: +/-100PPM/DEGC: 0.0630W")
      (fields
        (field (name "CASE") "SMT (0402)")
        (field (name "MANUFACTURER") "VISHAY DALE:YAGEO PHICOMP")
        (field (name "MATERIAL_TYPE") "THICK FILM")
        (field (name "MAXINV") "80-0010K-23")
        (field (name "MFG_PART_NUMBER") "CRCW040210K0FK:RC0402FR-0710KL")
        (field (name "ORIGINALSYMBOLORIGIN") "(-75,50)")
        (field (name "PACK_TYPE") "0402RES")
        (field (name "PHYS_PAGE") "1")
        (field (name "POWER_RATING") "0.0625W")
        (field (name "RES") "1.00E04")
        (field (name "TEMP_RANGE") "-55 DEGC TO +155 DEGC")
        (field (name "TOLERANCE") "1%")
        (field (name "VER") "2")
        (field (name "VLOG_PARAM01") "RES:INTEGER")
      )
      (libsource (lib "eagle-import") (part "RES_SMDRES_SMD_2"))
    )
    (comp (ref "R66")
      (value "10K")
      (footprint "eagle-import:0402")
      (description "RES: SMT (0402): 10K: 1%: +/-100PPM/DEGC: 0.0630W")
      (fields
        (field (name "CASE") "SMT (0402)")
        (field (name "MANUFACTURER") "VISHAY DALE:YAGEO PHICOMP")
        (field (name "MATERIAL_TYPE") "THICK FILM")
        (field (name "MAXINV") "80-0010K-23")
        (field (name "MFG_PART_NUMBER") "CRCW040210K0FK:RC0402FR-0710KL")
        (field (name "ORIGINALSYMBOLORIGIN") "(-75,50)")
        (field (name "PACK_TYPE") "0402RES")
        (field (name "PHYS_PAGE") "1")
        (field (name "POWER_RATING") "0.0625W")
        (field (name "RES") "1.00E04")
        (field (name "TEMP_RANGE") "-55 DEGC TO +155 DEGC")
        (field (name "TOLERANCE") "1%")
        (field (name "VER") "2")
        (field (name "VLOG_PARAM01") "RES:INTEGER")
      )
      (libsource (lib "eagle-import") (part "RES_SMDRES_SMD_2"))
    )
    (comp (ref "R67")
      (value "10K")
      (footprint "eagle-import:0402")
      (description "RES: SMT (0402): 10K: 1%: +/-100PPM/DEGC: 0.0630W")
      (fields
        (field (name "CASE") "SMT (0402)")
        (field (name "MANUFACTURER") "VISHAY DALE:YAGEO PHICOMP")
        (field (name "MATERIAL_TYPE") "THICK FILM")
        (field (name "MAXINV") "80-0010K-23")
        (field (name "MFG_PART_NUMBER") "CRCW040210K0FK:RC0402FR-0710KL")
        (field (name "ORIGINALSYMBOLORIGIN") "(-75,50)")
        (field (name "PACK_TYPE") "0402RES")
        (field (name "PHYS_PAGE") "1")
        (field (name "POWER_RATING") "0.0625W")
        (field (name "RES") "1.00E04")
        (field (name "TEMP_RANGE") "-55 DEGC TO +155 DEGC")
        (field (name "TOLERANCE") "1%")
        (field (name "VER") "2")
        (field (name "VLOG_PARAM01") "RES:INTEGER")
      )
      (libsource (lib "eagle-import") (part "RES_SMDRES_SMD_2"))
    )
    (comp (ref "R68")
      (value "10K")
      (footprint "eagle-import:0402")
      (description "RES: SMT (0402): 10K: 1%: +/-100PPM/DEGC: 0.0630W")
      (fields
        (field (name "CASE") "SMT (0402)")
        (field (name "MANUFACTURER") "VISHAY DALE:YAGEO PHICOMP")
        (field (name "MATERIAL_TYPE") "THICK FILM")
        (field (name "MAXINV") "80-0010K-23")
        (field (name "MFG_PART_NUMBER") "CRCW040210K0FK:RC0402FR-0710KL")
        (field (name "ORIGINALSYMBOLORIGIN") "(-75,50)")
        (field (name "PACK_TYPE") "0402RES")
        (field (name "PHYS_PAGE") "1")
        (field (name "POWER_RATING") "0.0625W")
        (field (name "RES") "1.00E04")
        (field (name "TEMP_RANGE") "-55 DEGC TO +155 DEGC")
        (field (name "TOLERANCE") "1%")
        (field (name "VER") "2")
        (field (name "VLOG_PARAM01") "RES:INTEGER")
      )
      (libsource (lib "eagle-import") (part "RES_SMDRES_SMD_2"))
    )
    (comp (ref "R69")
      (value "25K")
      (footprint "eagle-import:0402")
      (description "RES: SMT (0402): 25K: 0.10%: +/-25PPM/DEGK: 0.0500W")
      (fields
        (field (name "CASE") "SMT (0402)")
        (field (name "MANUFACTURER") "VISHAY DALE")
        (field (name "MATERIAL_TYPE") "THIN FILM")
        (field (name "MAXINV") "80-0025K-BA64")
        (field (name "MFG_PART_NUMBER") "PNM0402E2502BS")
        (field (name "ORIGINALSYMBOLORIGIN") "(-75,50)")
        (field (name "PACK_TYPE") "0402RES")
        (field (name "PHYS_PAGE") "1")
        (field (name "POWER_RATING") "0.05W")
        (field (name "RES") "2.50E04")
        (field (name "TEMP_RANGE") "-55 DEGC TO +155 DEGC")
        (field (name "TOLERANCE") "0.1%")
        (field (name "VER") "2")
        (field (name "VLOG_PARAM01") "RES:INTEGER")
      )
      (libsource (lib "eagle-import") (part "RES_SMDRES_SMD_2"))
    )
    (comp (ref "R70")
      (value "10K")
      (footprint "eagle-import:0402")
      (description "RES: SMT (0402): 10K: 1%: +/-100PPM/DEGC: 0.0630W")
      (fields
        (field (name "CASE") "SMT (0402)")
        (field (name "MANUFACTURER") "VISHAY DALE:YAGEO PHICOMP")
        (field (name "MAXINV") "80-0010K-23")
        (field (name "MFG_PART_NUMBER") "CRCW040210K0FK:RC0402FR-0710KL")
        (field (name "ORIGINALSYMBOLORIGIN") "(-75,50)")
        (field (name "PACK_TYPE") "0402RES")
        (field (name "PHYS_PAGE") "1")
        (field (name "POWER_RATING") "0.0625W")
        (field (name "RES") "1.00E04")
        (field (name "TEMP_RANGE") "-55 DEGC TO +155 DEGC")
        (field (name "TOLERANCE") "1%")
        (field (name "VER") "2")
        (field (name "VLOG_PARAM01") "RES:INTEGER")
      )
      (libsource (lib "eagle-import") (part "RES_SMDRES_SMD_2"))
    )
    (comp (ref "R71")
      (value "10K")
      (footprint "eagle-import:0402")
      (description "RES: SMT (0402): 10K: 1%: +/-100PPM/DEGC: 0.0630W")
      (fields
        (field (name "CASE") "SMT (0402)")
        (field (name "MANUFACTURER") "VISHAY DALE:YAGEO PHICOMP")
        (field (name "MAXINV") "80-0010K-23")
        (field (name "MFG_PART_NUMBER") "CRCW040210K0FK:RC0402FR-0710KL")
        (field (name "ORIGINALSYMBOLORIGIN") "(-75,50)")
        (field (name "PACK_TYPE") "0402RES")
        (field (name "PHYS_PAGE") "1")
        (field (name "POWER_RATING") "0.0625W")
        (field (name "RES") "1.00E04")
        (field (name "TEMP_RANGE") "-55 DEGC TO +155 DEGC")
        (field (name "TOLERANCE") "1%")
        (field (name "VER") "2")
        (field (name "VLOG_PARAM01") "RES:INTEGER")
      )
      (libsource (lib "eagle-import") (part "RES_SMDRES_SMD_2"))
    )
    (comp (ref "RT1")
      (value "10K")
      (footprint "eagle-import:THRMC0603X33M")
      (description "THERMISTOR: SMT (0201): 10K OHM: TOL=+/-5%")
      (fields
        (field (name "MANUFACTURER") "MURATA")
        (field (name "MAXINV") "83-0010K-0AN")
        (field (name "MFG_PART_NUMBER") "NCP03XH103J05")
        (field (name "ORIGINALSYMBOLORIGIN") "(-100,50)")
        (field (name "PACK_TYPE") "0201M")
        (field (name "PHYS_PAGE") "1")
        (field (name "TEMP_RANGE") "-40 DEGC TO +125 DEGC")
        (field (name "TOLERANCE") "5%")
        (field (name "VER") "1")
      )
      (libsource (lib "eagle-import") (part "THERMISTOR_SMD"))
    )
    (comp (ref "SW2")
      (value "EVP-AA102K")
      (footprint "eagle-import:SW_EVP-AAX02X_GND")
      (description "SWITCH: SPST: SMT: 15V: 0.02A: EVPAA SERIES WITH GROUND TERMINAL: LIGHT TOUCH SWITCH: RCONTACT=0.1 OHM: RINSULATION=100M OHM: WITH SPECIAL ASSEMBLY INSTRUCTIONS")
      (fields
        (field (name "MANUFACTURER") "PANASONIC")
        (field (name "MAXINV") "EH111000005105")
        (field (name "MFG_PART_NUMBER") "EVP-AA102K")
        (field (name "ORIGINALSYMBOLORIGIN") "(-175,125)")
        (field (name "PACK_TYPE") "SMT_GND")
        (field (name "PHYS_PAGE") "1")
        (field (name "TEMP_RANGE") "-40 DEGC TO +85 DEGC")
        (field (name "TOLERANCE") "N/A")
        (field (name "VER") "3")
        (field (name "VOLTAGE_RATING") "+2V TO +15V")
      )
      (libsource (lib "eagle-import") (part "EVP-AAXXXX"))
    )
    (comp (ref "U1")
      (value "MAX20360EWN+")
      (footprint "eagle-import:MAXIM_21-100373")
      (description "EVKIT PART- IC: WEARABLE POWER NAMAGEMENT SOLUTION: PACKAGE OUTLINE DRAWING: 21-100373: WLP 72 PINS: 0.5MM PITCH: PKG. CODE: W724A4+1")
      (fields
        (field (name "COMMENTS") "THIS PART NUMBER WILL BE CUSTOMIZED FOR HSP/MRD104 AND UPDATED, CONFIRM THE PART NUMBER BEFORE ORDER")
        (field (name "MANUFACTURER") "MAXIM")
        (field (name "MAXINV") "N/A")
        (field (name "MFG_PART_NUMBER") "MAX20360EWN+")
        (field (name "ORIGINALSYMBOLORIGIN") "(-500,1875)")
        (field (name "PACK_TYPE") "WLP72")
        (field (name "PHYS_PAGE") "1")
        (field (name "SEC_TYPE") "WLP72")
        (field (name "TEMP_RANGE") "-40 DEGC TO +85 DEGC")
        (field (name "TOLERANCE") "N/A")
        (field (name "VER") "1")
        (field (name "VOLTAGE_RATING") "N/A")
      )
      (libsource (lib "eagle-import") (part "EK_MAX20360"))
    )
    (comp (ref "C7")
      (value "10UF")
      (footprint "eagle-import:0603")
      (description "CAP: SMT (0603): 10UF: 20%: 25V: X5R: CERAMIC")
      (fields
        (field (name "CAP") "1.00E-05")
        (field (name "CASE") "SMT (0603)")
        (field (name "COMMENTS") "USE ONLY GRM188R61E106MA73")
        (field (name "MANUFACTURER") "TDK:SAMSUNG ELECTRONICS:MURATA::MURATA")
        (field (name "MATERIAL_TYPE") "CERAMIC CHIP")
        (field (name "MAXINV") "20-0010U-P7")
        (field (name "MFG_PART_NUMBER") "C1608X5R1E106M080AC:CL10A106MA8NRNC:GRM188R61E106MA73:ZRB18AR61E106ME01:GRT188R61E106ME13")
        (field (name "ORIGINALSYMBOLORIGIN") "(-50,50)")
        (field (name "PACK_TYPE") "0603CAP")
        (field (name "PHYS_PAGE") "2")
        (field (name "REFLOW") "-")
        (field (name "TEMP_RANGE") "-55 DEGC TO +85 DEGC")
        (field (name "TOLERANCE") "20%")
        (field (name "VER") "2")
        (field (name "VLOG_PARAM01") "CAP:INTEGER")
        (field (name "VOLTAGE_RATING") "25V")
      )
      (libsource (lib "eagle-import") (part "CAP_NPCAP_NP_3"))
    )
    (comp (ref "C11")
      (value "1UF")
      (footprint "eagle-import:CAPC0603X33M")
      (description "CAP: SMT (0201): 1UF: 20%: 10V: X5R: CERAMIC")
      (fields
        (field (name "CAP") "1.00E-06")
        (field (name "MANUFACTURER") "MURATA")
        (field (name "MAXINV") "20-0001U-AA20")
        (field (name "MFG_PART_NUMBER") "GRM033R61A105ME15")
        (field (name "ORIGINALSYMBOLORIGIN") "(-50,50)")
        (field (name "PACK_TYPE") "0201CAPM")
        (field (name "PHYS_PAGE") "2")
        (field (name "REFLOW") "-")
        (field (name "TEMP_RANGE") "-55 DEGC TO +85 DEGC")
        (field (name "TOLERANCE") "20%")
        (field (name "VER") "1")
        (field (name "VLOG_PARAM01") "CAP:INTEGER")
        (field (name "VOLTAGE_RATING") "10V")
      )
      (libsource (lib "eagle-import") (part "CAP_NP#1CAP_NP#1"))
    )
    (comp (ref "C12")
      (value "0.1UF")
      (footprint "eagle-import:CAPC0603X33M")
      (description "CAP: SMT (0201): 0.1UF: 10%: 16V: X7S: CERAMIC")
      (fields
        (field (name "CAP") "1.00E-07")
        (field (name "CASE") "SMT (0201)")
        (field (name "MANUFACTURER") "MURATA")
        (field (name "MAXINV") "20-000U1-BA99")
        (field (name "MFG_PART_NUMBER") "GRM033C71C104KE14")
        (field (name "ORIGINALSYMBOLORIGIN") "(-50,50)")
        (field (name "PACK_TYPE") "0201CAPM")
        (field (name "PHYS_PAGE") "2")
        (field (name "TEMP_RANGE") "-55 DEGC TO +125 DEGC")
        (field (name "TOLERANCE") "10%")
        (field (name "VER") "2")
        (field (name "VLOG_PARAM01") "CAP:INTEGER")
        (field (name "VOLTAGE_RATING") "16V")
      )
      (libsource (lib "eagle-import") (part "CAP_NPCAP_NP_1"))
    )
    (comp (ref "C13")
      (value "1UF")
      (footprint "eagle-import:CAPC0603X33M")
      (description "CAP: SMT (0201): 1UF: 20%: 10V: X5R: CERAMIC")
      (fields
        (field (name "CAP") "1.00E-06")
        (field (name "MANUFACTURER") "MURATA")
        (field (name "MAXINV") "20-0001U-AA20")
        (field (name "MFG_PART_NUMBER") "GRM033R61A105ME15")
        (field (name "ORIGINALSYMBOLORIGIN") "(-50,50)")
        (field (name "PACK_TYPE") "0201CAPM")
        (field (name "PHYS_PAGE") "2")
        (field (name "REFLOW") "-")
        (field (name "TEMP_RANGE") "-55 DEGC TO +85 DEGC")
        (field (name "TOLERANCE") "20%")
        (field (name "VER") "1")
        (field (name "VLOG_PARAM01") "CAP:INTEGER")
        (field (name "VOLTAGE_RATING") "10V")
      )
      (libsource (lib "eagle-import") (part "CAP_NP#1CAP_NP#1"))
    )
    (comp (ref "C15")
      (value "0.1UF")
      (footprint "eagle-import:CAPC0603X33M")
      (description "CAP: SMT (0201): 0.1UF: 10%: 16V: X7S: CERAMIC")
      (fields
        (field (name "CAP") "1.00E-07")
        (field (name "CASE") "SMT (0201)")
        (field (name "MANUFACTURER") "MURATA")
        (field (name "MAXINV") "20-000U1-BA99")
        (field (name "MFG_PART_NUMBER") "GRM033C71C104KE14")
        (field (name "ORIGINALSYMBOLORIGIN") "(-50,50)")
        (field (name "PACK_TYPE") "0201CAPM")
        (field (name "PHYS_PAGE") "2")
        (field (name "TEMP_RANGE") "-55 DEGC TO +125 DEGC")
        (field (name "TOLERANCE") "10%")
        (field (name "VER") "2")
        (field (name "VLOG_PARAM01") "CAP:INTEGER")
        (field (name "VOLTAGE_RATING") "16V")
      )
      (libsource (lib "eagle-import") (part "CAP_NPCAP_NP_1"))
    )
    (comp (ref "C33")
      (value "1UF")
      (footprint "eagle-import:CAPC0603X33M")
      (description "CAP: SMT (0201): 1UF: 20%: 10V: X6S: CERAMIC")
      (fields
        (field (name "CAP") "1.00E-06")
        (field (name "CASE") "SMT (0201)")
        (field (name "MANUFACTURER") "MURATA")
        (field (name "MAXINV") "20-0001U-EA78")
        (field (name "MFG_PART_NUMBER") "GRM033C81A105ME05")
        (field (name "ORIGINALSYMBOLORIGIN") "(-50,50)")
        (field (name "PACK_TYPE") "0201CAPM")
        (field (name "PHYS_PAGE") "2")
        (field (name "TEMP_RANGE") "-55 DEGC TO +105 DEGC")
        (field (name "TOLERANCE") "20%")
        (field (name "VER") "2")
        (field (name "VLOG_PARAM01") "CAP:INTEGER")
        (field (name "VOLTAGE_RATING") "10V")
      )
      (libsource (lib "eagle-import") (part "CAP_NPCAP_NP_1"))
    )
    (comp (ref "C34")
      (value "0.1UF")
      (footprint "eagle-import:CAPC0603X33M")
      (description "CAP: SMT (0201): 0.1UF: 10%: 16V: X7S: CERAMIC")
      (fields
        (field (name "CAP") "1.00E-07")
        (field (name "CASE") "SMT (0201)")
        (field (name "MANUFACTURER") "MURATA")
        (field (name "MAXINV") "20-000U1-BA99")
        (field (name "MFG_PART_NUMBER") "GRM033C71C104KE14")
        (field (name "ORIGINALSYMBOLORIGIN") "(-50,50)")
        (field (name "PACK_TYPE") "0201CAPM")
        (field (name "PHYS_PAGE") "2")
        (field (name "TEMP_RANGE") "-55 DEGC TO +125 DEGC")
        (field (name "TOLERANCE") "10%")
        (field (name "VER") "2")
        (field (name "VLOG_PARAM01") "CAP:INTEGER")
        (field (name "VOLTAGE_RATING") "16V")
      )
      (libsource (lib "eagle-import") (part "CAP_NPCAP_NP_1"))
    )
    (comp (ref "C35")
      (value "1UF")
      (footprint "eagle-import:CAPC0603X33M")
      (description "CAP: SMT (0201): 1UF: 20%: 10V: X6S: CERAMIC")
      (fields
        (field (name "CAP") "1.00E-06")
        (field (name "CASE") "SMT (0201)")
        (field (name "MANUFACTURER") "MURATA")
        (field (name "MAXINV") "20-0001U-EA78")
        (field (name "MFG_PART_NUMBER") "GRM033C81A105ME05")
        (field (name "ORIGINALSYMBOLORIGIN") "(-50,50)")
        (field (name "PACK_TYPE") "0201CAPM")
        (field (name "PHYS_PAGE") "2")
        (field (name "TEMP_RANGE") "-55 DEGC TO +105 DEGC")
        (field (name "TOLERANCE") "20%")
        (field (name "VER") "2")
        (field (name "VLOG_PARAM01") "CAP:INTEGER")
        (field (name "VOLTAGE_RATING") "10V")
      )
      (libsource (lib "eagle-import") (part "CAP_NPCAP_NP_1"))
    )
    (comp (ref "C36")
      (value "0.1UF")
      (footprint "eagle-import:CAPC0603X33M")
      (description "CAP: SMT (0201): 0.1UF: 10%: 16V: X7S: CERAMIC")
      (fields
        (field (name "CAP") "1.00E-07")
        (field (name "CASE") "SMT (0201)")
        (field (name "MANUFACTURER") "MURATA")
        (field (name "MAXINV") "20-000U1-BA99")
        (field (name "MFG_PART_NUMBER") "GRM033C71C104KE14")
        (field (name "ORIGINALSYMBOLORIGIN") "(-50,50)")
        (field (name "PACK_TYPE") "0201CAPM")
        (field (name "PHYS_PAGE") "2")
        (field (name "TEMP_RANGE") "-55 DEGC TO +125 DEGC")
        (field (name "TOLERANCE") "10%")
        (field (name "VER") "2")
        (field (name "VLOG_PARAM01") "CAP:INTEGER")
        (field (name "VOLTAGE_RATING") "16V")
      )
      (libsource (lib "eagle-import") (part "CAP_NPCAP_NP_1"))
    )
    (comp (ref "C37")
      (value "4700PF")
      (footprint "eagle-import:CAPC0603X33M")
      (description "CAP: SMT (0201): 4700PF: 10%: 10V: X7R: CERAMIC")
      (fields
        (field (name "CAP") "4.70E-09")
        (field (name "CASE") "SMT (0201)")
        (field (name "MANUFACTURER") "MURATA")
        (field (name "MAXINV") "20-4700P-I6")
        (field (name "MFG_PART_NUMBER") "GRM033R71A472KA01D")
        (field (name "ORIGINALSYMBOLORIGIN") "(-50,50)")
        (field (name "PACK_TYPE") "0201CAPM")
        (field (name "PHYS_PAGE") "2")
        (field (name "TEMP_RANGE") "-55 DEGC TO +125 DEGC")
        (field (name "TOLERANCE") "10%")
        (field (name "VER") "2")
        (field (name "VLOG_PARAM01") "CAP:INTEGER")
        (field (name "VOLTAGE_RATING") "10V")
      )
      (libsource (lib "eagle-import") (part "CAP_NPCAP_NP_1"))
    )
    (comp (ref "C38")
      (value "1UF")
      (footprint "eagle-import:CAPC0603X33M")
      (description "CAP: SMT (0201): 1UF: 20%: 10V: X6S: CERAMIC")
      (fields
        (field (name "CAP") "1.00E-06")
        (field (name "CASE") "SMT (0201)")
        (field (name "MANUFACTURER") "MURATA")
        (field (name "MAXINV") "20-0001U-EA78")
        (field (name "MFG_PART_NUMBER") "GRM033C81A105ME05")
        (field (name "ORIGINALSYMBOLORIGIN") "(-50,50)")
        (field (name "PACK_TYPE") "0201CAPM")
        (field (name "PHYS_PAGE") "2")
        (field (name "TEMP_RANGE") "-55 DEGC TO +105 DEGC")
        (field (name "TOLERANCE") "20%")
        (field (name "VER") "2")
        (field (name "VLOG_PARAM01") "CAP:INTEGER")
        (field (name "VOLTAGE_RATING") "10V")
      )
      (libsource (lib "eagle-import") (part "CAP_NPCAP_NP_1"))
    )
    (comp (ref "C45")
      (value "0.1UF")
      (footprint "eagle-import:CAPC0603X33M")
      (description "CAP: SMT (0201): 0.1UF: 10%: 16V: X5R: CERAMIC")
      (fields
        (field (name "CAP") "1.00E-07")
        (field (name "CASE") "SMT (0201)")
        (field (name "MANUFACTURER") "MURATA:TDK")
        (field (name "MAXINV") "20-000U1-A26")
        (field (name "MFG_PART_NUMBER") "GRM033R61C104K:C0603X5R1C104K030BC")
        (field (name "ORIGINALSYMBOLORIGIN") "(-50,50)")
        (field (name "PACK_TYPE") "0201CAPM")
        (field (name "PHYS_PAGE") "2")
        (field (name "TEMP_RANGE") "-55 DEGC TO +85 DEGC")
        (field (name "TOLERANCE") "10%")
        (field (name "VER") "2")
        (field (name "VLOG_PARAM01") "CAP:INTEGER")
        (field (name "VOLTAGE_RATING") "16V")
      )
      (libsource (lib "eagle-import") (part "CAP_NPCAP_NP_1"))
    )
    (comp (ref "C46")
      (value "0.1UF")
      (footprint "eagle-import:CAPC0603X33M")
      (description "CAP: SMT (0201): 0.1UF: 10%: 16V: X5R: CERAMIC")
      (fields
        (field (name "CAP") "1.00E-07")
        (field (name "CASE") "SMT (0201)")
        (field (name "MANUFACTURER") "MURATA:TDK")
        (field (name "MAXINV") "20-000U1-A26")
        (field (name "MFG_PART_NUMBER") "GRM033R61C104K:C0603X5R1C104K030BC")
        (field (name "ORIGINALSYMBOLORIGIN") "(-50,50)")
        (field (name "PACK_TYPE") "0201CAPM")
        (field (name "PHYS_PAGE") "2")
        (field (name "TEMP_RANGE") "-55 DEGC TO +85 DEGC")
        (field (name "TOLERANCE") "10%")
        (field (name "VER") "2")
        (field (name "VLOG_PARAM01") "CAP:INTEGER")
        (field (name "VOLTAGE_RATING") "16V")
      )
      (libsource (lib "eagle-import") (part "CAP_NPCAP_NP_1"))
    )
    (comp (ref "C47")
      (value "0.1UF")
      (footprint "eagle-import:CAPC0603X33M")
      (description "CAP: SMT (0201): 0.1UF: 10%: 16V: X5R: CERAMIC")
      (fields
        (field (name "CAP") "1.00E-07")
        (field (name "CASE") "SMT (0201)")
        (field (name "MANUFACTURER") "MURATA:TDK")
        (field (name "MAXINV") "20-000U1-A26")
        (field (name "MFG_PART_NUMBER") "GRM033R61C104K:C0603X5R1C104K030BC")
        (field (name "ORIGINALSYMBOLORIGIN") "(-50,50)")
        (field (name "PACK_TYPE") "0201CAPM")
        (field (name "PHYS_PAGE") "2")
        (field (name "TEMP_RANGE") "-55 DEGC TO +85 DEGC")
        (field (name "TOLERANCE") "10%")
        (field (name "VER") "2")
        (field (name "VLOG_PARAM01") "CAP:INTEGER")
        (field (name "VOLTAGE_RATING") "16V")
      )
      (libsource (lib "eagle-import") (part "CAP_NPCAP_NP_1"))
    )
    (comp (ref "C48")
      (value "0.1UF")
      (footprint "eagle-import:CAPC0603X33M")
      (description "CAP: SMT (0201): 0.1UF: 10%: 16V: X5R: CERAMIC")
      (fields
        (field (name "CAP") "1.00E-07")
        (field (name "CASE") "SMT (0201)")
        (field (name "MANUFACTURER") "MURATA:TDK")
        (field (name "MAXINV") "20-000U1-A26")
        (field (name "MFG_PART_NUMBER") "GRM033R61C104K:C0603X5R1C104K030BC")
        (field (name "ORIGINALSYMBOLORIGIN") "(-50,50)")
        (field (name "PACK_TYPE") "0201CAPM")
        (field (name "PHYS_PAGE") "2")
        (field (name "TEMP_RANGE") "-55 DEGC TO +85 DEGC")
        (field (name "TOLERANCE") "10%")
        (field (name "VER") "2")
        (field (name "VLOG_PARAM01") "CAP:INTEGER")
        (field (name "VOLTAGE_RATING") "16V")
      )
      (libsource (lib "eagle-import") (part "CAP_NPCAP_NP_1"))
    )
    (comp (ref "C49")
      (value "0.1UF")
      (footprint "eagle-import:CAPC0603X33M")
      (description "CAP: SMT (0201): 0.1UF: 10%: 16V: X5R: CERAMIC")
      (fields
        (field (name "CAP") "1.00E-07")
        (field (name "CASE") "SMT (0201)")
        (field (name "MANUFACTURER") "MURATA:TDK")
        (field (name "MAXINV") "20-000U1-A26")
        (field (name "MFG_PART_NUMBER") "GRM033R61C104K:C0603X5R1C104K030BC")
        (field (name "ORIGINALSYMBOLORIGIN") "(-50,50)")
        (field (name "PACK_TYPE") "0201CAPM")
        (field (name "PHYS_PAGE") "2")
        (field (name "TEMP_RANGE") "-55 DEGC TO +85 DEGC")
        (field (name "TOLERANCE") "10%")
        (field (name "VER") "2")
        (field (name "VLOG_PARAM01") "CAP:INTEGER")
        (field (name "VOLTAGE_RATING") "16V")
      )
      (libsource (lib "eagle-import") (part "CAP_NPCAP_NP_1"))
    )
    (comp (ref "C56")
      (value "1UF")
      (footprint "eagle-import:0402")
      (description "CAP: SMT (0402): 1UF: 10%: 35V: X5R:  CERAMIC")
      (fields
        (field (name "CAP") "1.00E-06")
        (field (name "CASE") "SMT")
        (field (name "MANUFACTURER") "TDK")
        (field (name "MATERIAL_TYPE") " CERAMIC CHIP")
        (field (name "MAXINV") "20-0001U-BA62")
        (field (name "MFG_PART_NUMBER") "C1005X5R1V105K050BC")
        (field (name "ORIGINALSYMBOLORIGIN") "(-50,50)")
        (field (name "PACK_TYPE") "0402CAP")
        (field (name "PHYS_PAGE") "2")
        (field (name "REFLOW") "-")
        (field (name "TEMP_RANGE") "-55 DEGC TO +85 DEGC")
        (field (name "TOLERANCE") "10%")
        (field (name "VER") "2")
        (field (name "VLOG_PARAM01") "CAP:INTEGER")
        (field (name "VOLTAGE_RATING") "35V")
      )
      (libsource (lib "eagle-import") (part "CAP_NPCAP_NP_2"))
    )
    (comp (ref "C57")
      (value "OPEN")
      (footprint "eagle-import:CAPC0603X23L")
      (description "CAPACITOR: SMT (0201): OPEN: FORMFACTOR")
      (fields
        (field (name "CAP") "N/A")
        (field (name "CASE") "N/A")
        (field (name "MANUFACTURER") "N/A")
        (field (name "MATERIAL_TYPE") "N/A")
        (field (name "MAXINV") "N/A")
        (field (name "MFG_PART_NUMBER") "N/A")
        (field (name "ORIGINALSYMBOLORIGIN") "(-50,50)")
        (field (name "PACK_TYPE") "0201_FF")
        (field (name "PHYS_PAGE") "2")
        (field (name "REFLOW") "-")
        (field (name "TEMP_RANGE") "N/A")
        (field (name "TOLERANCE") "N/A")
        (field (name "VER") "1")
        (field (name "VLOG_PARAM01") "N/A")
        (field (name "VOLTAGE_RATING") "N/A")
      )
      (libsource (lib "eagle-import") (part "EK_CAP_NP"))
    )
    (comp (ref "C58")
      (value "OPEN")
      (footprint "eagle-import:CAPC0603X23L")
      (description "CAPACITOR: SMT (0201): OPEN: FORMFACTOR")
      (fields
        (field (name "CAP") "N/A")
        (field (name "CASE") "N/A")
        (field (name "MANUFACTURER") "N/A")
        (field (name "MATERIAL_TYPE") "N/A")
        (field (name "MAXINV") "N/A")
        (field (name "MFG_PART_NUMBER") "N/A")
        (field (name "ORIGINALSYMBOLORIGIN") "(-50,50)")
        (field (name "PACK_TYPE") "0201_FF")
        (field (name "PHYS_PAGE") "2")
        (field (name "REFLOW") "-")
        (field (name "TEMP_RANGE") "N/A")
        (field (name "TOLERANCE") "N/A")
        (field (name "VER") "1")
        (field (name "VLOG_PARAM01") "N/A")
        (field (name "VOLTAGE_RATING") "N/A")
      )
      (libsource (lib "eagle-import") (part "EK_CAP_NP"))
    )
    (comp (ref "C66")
      (value "0.1UF")
      (footprint "eagle-import:CAPC0603X33M")
      (description "CAP: SMT (0201): 0.1UF: 20%: 25V: X5R: CERAMIC")
      (fields
        (field (name "CAP") "1.00E-07")
        (field (name "CASE") "SMT (0201)")
        (field (name "MANUFACTURER") "TDK:MURATA")
        (field (name "MAXINV") "20-000U1-A20A")
        (field (name "MFG_PART_NUMBER") "C0603X5R1E104M030BB:GRM033R61E104ME14")
        (field (name "ORIGINALSYMBOLORIGIN") "(-50,50)")
        (field (name "PACK_TYPE") "0201CAPM")
        (field (name "PHYS_PAGE") "2")
        (field (name "TEMP_RANGE") "-55 DEGC TO +85 DEGC")
        (field (name "TOLERANCE") "20%")
        (field (name "VER") "2")
        (field (name "VLOG_PARAM01") "CAP:INTEGER")
        (field (name "VOLTAGE_RATING") "25V")
      )
      (libsource (lib "eagle-import") (part "CAP_NPCAP_NP_1"))
    )
    (comp (ref "C67")
      (value "0.01UF")
      (footprint "eagle-import:0402")
      (description "CAP: SMT (0402): 0.01UF: 10%: 25V: X5R: CERAMIC")
      (fields
        (field (name "CAP") "1.00E-08")
        (field (name "CASE") "SMT (0402)")
        (field (name "MANUFACTURER") "AVX")
        (field (name "MAXINV") "20-00U01-Z51")
        (field (name "MFG_PART_NUMBER") "04023D103KAT2A")
        (field (name "ORIGINALSYMBOLORIGIN") "(-50,50)")
        (field (name "PACK_TYPE") "0402CAP")
        (field (name "PHYS_PAGE") "2")
        (field (name "TEMP_RANGE") "-55 DEGC TO +85 DEGC")
        (field (name "TOLERANCE") "10%")
        (field (name "VER") "2")
        (field (name "VLOG_PARAM01") "CAP:INTEGER")
        (field (name "VOLTAGE_RATING") "25V")
      )
      (libsource (lib "eagle-import") (part "CAP_NPCAP_NP_2"))
    )
    (comp (ref "J1")
      (value "TF13BA-6S-0.4SH")
      (footprint "eagle-import:HRSC_TF13BA-6S-0_4SH")
      (description "CONNECTOR: FEMALE: SMT: TF13BA SERIES: FPC/FFC CONNECTOR: 6PINS")
      (fields
        (field (name "MANUFACTURER") "HIROSE ELECTRIC CO LTD")
        (field (name "MAXINV") "EH111000005235")
        (field (name "MFG_PART_NUMBER") "TF13BA-6S-0.4SH")
        (field (name "ORIGINALSYMBOLORIGIN") "(-150,275)")
        (field (name "PACK_TYPE") "SMD")
        (field (name "PHYS_PAGE") "2")
        (field (name "REFLOW") "-")
        (field (name "SEC_TYPE") "SMD")
        (field (name "TEMP_RANGE") "-55 DEGC TO +85 DEGC")
        (field (name "TOLERANCE") "N/A")
        (field (name "VER") "1")
        (field (name "VOLTAGE_RATING") "+50V")
      )
      (libsource (lib "eagle-import") (part "TF13BA-6S"))
    )
    (comp (ref "J2")
      (value "FH26W-25S-0.3SHW(60)")
      (footprint "eagle-import:HRSC_FH26W-25S-0_3SHW")
      (description "CONNECTOR: FEMALE: SMT: FPC CONNECTOR: RIGHT ANGLE: 25PINS")
      (fields
        (field (name "MANUFACTURER") "HIROSE ELECTRIC CO. LTD.")
        (field (name "MAXINV") "EH111000005014")
        (field (name "MFG_PART_NUMBER") "FH26W-25S-0.3SHW(60)")
        (field (name "ORIGINALSYMBOLORIGIN") "(-150,550)")
        (field (name "PACK_TYPE") "RA")
        (field (name "PHYS_PAGE") "2")
        (field (name "REFLOW") "-")
        (field (name "SEC_TYPE") "RA")
        (field (name "TEMP_RANGE") "-55 DEGC TO +85 DEGC")
        (field (name "TOLERANCE") "N/A")
        (field (name "VER") "1")
        (field (name "VOLTAGE_RATING") "+30V")
      )
      (libsource (lib "eagle-import") (part "FH26-25S"))
    )
    (comp (ref "J4")
      (value "DX07S024JJ3")
      (footprint "eagle-import:JAE_DX07S024JJ3")
      (description "CONNECTOR: FEMALE: SMT: USB TYPE-C CONNECTOR: DX07 SERIES RECEPTACLE: RIGHT ANGLE: 24PINS")
      (fields
        (field (name "MANUFACTURER") "JAE ELECTRONIC INDUSTRY")
        (field (name "MAXINV") "01-DX07S024JJ324P-26")
        (field (name "MFG_PART_NUMBER") "DX07S024JJ3R1300")
        (field (name "ORIGINALSYMBOLORIGIN") "(-250,550)")
        (field (name "PACK_TYPE") "RA")
        (field (name "PHYS_PAGE") "2")
        (field (name "TEMP_RANGE") "-30 DEGC TO +80 DEGC")
        (field (name "TOLERANCE") "N/A")
        (field (name "VER") "1")
        (field (name "VOLTAGE_RATING") "20V")
      )
      (libsource (lib "eagle-import") (part "DX07S024JJ3"))
    )
    (comp (ref "L7")
      (value "220")
      (footprint "eagle-import:0805")
      (description "INDUCTOR: SMT (0805): FERRITE-BEAD: 220: TOL=+/-25%: 0.2A")
      (fields
        (field (name "MANUFACTURER") "MURATA")
        (field (name "MAXINV") "50-00220-SM2")
        (field (name "MFG_PART_NUMBER") "BLM21PG221SN1")
        (field (name "ORIGINALSYMBOLORIGIN") "(-100,25)")
        (field (name "PACK_TYPE") "0805")
        (field (name "PHYS_PAGE") "2")
        (field (name "TEMP_RANGE") "-55 DEGC TO +125 DEGC")
        (field (name "TOLERANCE") "25%")
        (field (name "VER") "1")
      )
      (libsource (lib "eagle-import") (part "FERRITEBEADFERRITEBEAD_1"))
    )
    (comp (ref "L8")
      (value "2000")
      (footprint "eagle-import:1206")
      (description "INDUCTOR: SMT (1206): FERRITE-BEAD: 2000: TOL=+/-25%: 0.3A")
      (fields
        (field (name "MANUFACTURER") "LAIRD TECHNOLOGIES")
        (field (name "MAXINV") "51-02000-0AJ")
        (field (name "MFG_PART_NUMBER") "HZ1206C202R-10")
        (field (name "ORIGINALSYMBOLORIGIN") "(-100,25)")
        (field (name "PACK_TYPE") "1206")
        (field (name "PHYS_PAGE") "2")
        (field (name "TEMP_RANGE") "N/A")
        (field (name "TOLERANCE") "25%")
        (field (name "VER") "1")
      )
      (libsource (lib "eagle-import") (part "FERRITEBEADFERRITEBEAD"))
    )
    (comp (ref "R1")
      (value "0")
      (footprint "eagle-import:RESC0603X33M")
      (description "RES: SMT (0201): 0: 1%: JUMPER: 0.0500W")
      (fields
        (field (name "MANUFACTURER") "VISHAY DALE:PANASONIC")
        (field (name "MAXINV") "80-0000R-95")
        (field (name "ORIGINALSYMBOLORIGIN") "(-75,50)")
        (field (name "PACK_TYPE") "0201RES")
        (field (name "PHYS_PAGE") "2")
        (field (name "POWER_RATING") "0.05W")
        (field (name "RES") "0.00000001E00")
        (field (name "TEMP_RANGE") "-55 DEGC TO +155 DEGC")
        (field (name "TOLERANCE") "1%")
        (field (name "VARIANT") "DNI")
        (field (name "VER") "2")
        (field (name "VLOG_PARAM01") "RES:INTEGER")
      )
      (libsource (lib "eagle-import") (part "RES_SMDRES_SMD_1"))
    )
    (comp (ref "R2")
      (value "OPEN")
      (footprint "eagle-import:RESC0603X23L")
      (description "RESISTOR: 0201: OPEN: FORMFACTOR")
      (fields
        (field (name "CASE") "SMT (0201)")
        (field (name "MANUFACTURER") "N/A")
        (field (name "MAXINV") "N/A")
        (field (name "MFG_PART_NUMBER") "N/A")
        (field (name "ORIGINALSYMBOLORIGIN") "(-75,50)")
        (field (name "PACK_TYPE") "0201_FF")
        (field (name "PHYS_PAGE") "2")
        (field (name "POWER_RATING") "N/A")
        (field (name "RES") "N/A")
        (field (name "TEMP_RANGE") "N/A")
        (field (name "TOLERANCE") "N/A")
        (field (name "VER") "2")
        (field (name "VLOG_PARAM01") "N/A")
      )
      (libsource (lib "eagle-import") (part "EK_RES_SMD"))
    )
    (comp (ref "R3")
      (value "OPEN")
      (footprint "eagle-import:RESC0603X23L")
      (description "RESISTOR: 0201: OPEN: FORMFACTOR")
      (fields
        (field (name "CASE") "SMT (0201)")
        (field (name "MANUFACTURER") "N/A")
        (field (name "MAXINV") "N/A")
        (field (name "MFG_PART_NUMBER") "N/A")
        (field (name "ORIGINALSYMBOLORIGIN") "(-75,50)")
        (field (name "PACK_TYPE") "0201_FF")
        (field (name "PHYS_PAGE") "2")
        (field (name "POWER_RATING") "N/A")
        (field (name "RES") "N/A")
        (field (name "TEMP_RANGE") "N/A")
        (field (name "TOLERANCE") "N/A")
        (field (name "VER") "2")
        (field (name "VLOG_PARAM01") "N/A")
      )
      (libsource (lib "eagle-import") (part "EK_RES_SMD"))
    )
    (comp (ref "R4")
      (value "OPEN")
      (footprint "eagle-import:RESC0603X23L")
      (description "RESISTOR: 0201: OPEN: FORMFACTOR")
      (fields
        (field (name "CASE") "SMT (0201)")
        (field (name "MANUFACTURER") "N/A")
        (field (name "MAXINV") "N/A")
        (field (name "MFG_PART_NUMBER") "N/A")
        (field (name "ORIGINALSYMBOLORIGIN") "(-75,50)")
        (field (name "PACK_TYPE") "0201_FF")
        (field (name "PHYS_PAGE") "2")
        (field (name "POWER_RATING") "N/A")
        (field (name "RES") "N/A")
        (field (name "TEMP_RANGE") "N/A")
        (field (name "TOLERANCE") "N/A")
        (field (name "VER") "2")
        (field (name "VLOG_PARAM01") "N/A")
      )
      (libsource (lib "eagle-import") (part "EK_RES_SMD"))
    )
    (comp (ref "R6")
      (value "5.1K")
      (footprint "eagle-import:RESC0603X33M")
      (description "RES: SMT (0201): 5.1K: 1%: +/-200PPM/DEGC: 0.0500W")
      (fields
        (field (name "CASE") "SMT (0201)")
        (field (name "MANUFACTURER") "PANASONIC")
        (field (name "MATERIAL_TYPE") "THICK FILM")
        (field (name "MAXINV") "80-005K1-P0")
        (field (name "MFG_PART_NUMBER") "ERJ-1GNF5101C")
        (field (name "ORIGINALSYMBOLORIGIN") "(-75,50)")
        (field (name "PACK_TYPE") "0201RES")
        (field (name "PHYS_PAGE") "2")
        (field (name "POWER_RATING") "0.05W")
        (field (name "REFLOW") "-")
        (field (name "RES") "5.10E03")
        (field (name "TEMP_RANGE") "-55 DEGC TO +125 DEGC")
        (field (name "TOLERANCE") "1%")
        (field (name "VER") "2")
        (field (name "VLOG_PARAM01") "RES:INTEGER")
      )
      (libsource (lib "eagle-import") (part "RES_SMDRES_SMD_1"))
    )
    (comp (ref "R7")
      (value "5.1K")
      (footprint "eagle-import:RESC0603X33M")
      (description "RES: SMT (0201): 5.1K: 1%: +/-200PPM/DEGC: 0.0500W")
      (fields
        (field (name "CASE") "SMT (0201)")
        (field (name "MANUFACTURER") "PANASONIC")
        (field (name "MATERIAL_TYPE") "THICK FILM")
        (field (name "MAXINV") "80-005K1-P0")
        (field (name "MFG_PART_NUMBER") "ERJ-1GNF5101C")
        (field (name "ORIGINALSYMBOLORIGIN") "(-75,50)")
        (field (name "PACK_TYPE") "0201RES")
        (field (name "PHYS_PAGE") "2")
        (field (name "POWER_RATING") "0.05W")
        (field (name "REFLOW") "-")
        (field (name "RES") "5.10E03")
        (field (name "TEMP_RANGE") "-55 DEGC TO +125 DEGC")
        (field (name "TOLERANCE") "1%")
        (field (name "VER") "2")
        (field (name "VLOG_PARAM01") "RES:INTEGER")
      )
      (libsource (lib "eagle-import") (part "RES_SMDRES_SMD_1"))
    )
    (comp (ref "R8")
      (value "OPEN")
      (footprint "eagle-import:RESC0603X23L")
      (description "RESISTOR: 0201: OPEN: FORMFACTOR")
      (fields
        (field (name "CASE") "SMT (0201)")
        (field (name "MANUFACTURER") "N/A")
        (field (name "MAXINV") "N/A")
        (field (name "MFG_PART_NUMBER") "N/A")
        (field (name "ORIGINALSYMBOLORIGIN") "(-75,50)")
        (field (name "PACK_TYPE") "0201_FF")
        (field (name "PHYS_PAGE") "2")
        (field (name "POWER_RATING") "N/A")
        (field (name "RES") "N/A")
        (field (name "TEMP_RANGE") "N/A")
        (field (name "TOLERANCE") "N/A")
        (field (name "VER") "2")
        (field (name "VLOG_PARAM01") "N/A")
      )
      (libsource (lib "eagle-import") (part "EK_RES_SMD"))
    )
    (comp (ref "R9")
      (value "27")
      (footprint "eagle-import:RESC0603X33M")
      (description "RES: SMT (0201): 27: 1%: +/-100PPM/DEGC: 0.0500W")
      (fields
        (field (name "CASE") "SMT (0201)")
        (field (name "MANUFACTURER") "PANASONIC")
        (field (name "MAXINV") "80-0027R-95")
        (field (name "MFG_PART_NUMBER") "ERJ-1GEF27R0C")
        (field (name "ORIGINALSYMBOLORIGIN") "(-75,50)")
        (field (name "PACK_TYPE") "0201RES")
        (field (name "PHYS_PAGE") "2")
        (field (name "POWER_RATING") "0.05W")
        (field (name "RES") "2.70E01")
        (field (name "TEMP_RANGE") "-55 DEGC TO +155 DEGC")
        (field (name "TOLERANCE") "1%")
        (field (name "VER") "2")
        (field (name "VLOG_PARAM01") "RES:INTEGER")
      )
      (libsource (lib "eagle-import") (part "RES_SMDRES_SMD_1"))
    )
    (comp (ref "R10")
      (value "27")
      (footprint "eagle-import:RESC0603X33M")
      (description "RES: SMT (0201): 27: 1%: +/-100PPM/DEGC: 0.0500W")
      (fields
        (field (name "CASE") "SMT (0201)")
        (field (name "MANUFACTURER") "PANASONIC")
        (field (name "MAXINV") "80-0027R-95")
        (field (name "MFG_PART_NUMBER") "ERJ-1GEF27R0C")
        (field (name "ORIGINALSYMBOLORIGIN") "(-75,50)")
        (field (name "PACK_TYPE") "0201RES")
        (field (name "PHYS_PAGE") "2")
        (field (name "POWER_RATING") "0.05W")
        (field (name "RES") "2.70E01")
        (field (name "TEMP_RANGE") "-55 DEGC TO +155 DEGC")
        (field (name "TOLERANCE") "1%")
        (field (name "VER") "2")
        (field (name "VLOG_PARAM01") "RES:INTEGER")
      )
      (libsource (lib "eagle-import") (part "RES_SMDRES_SMD_1"))
    )
    (comp (ref "R11")
      (value "OPEN")
      (footprint "eagle-import:RESC0603X23L")
      (description "RESISTOR: 0201: OPEN: FORMFACTOR")
      (fields
        (field (name "CASE") "SMT (0201)")
        (field (name "MANUFACTURER") "N/A")
        (field (name "MAXINV") "N/A")
        (field (name "MFG_PART_NUMBER") "N/A")
        (field (name "ORIGINALSYMBOLORIGIN") "(-75,50)")
        (field (name "PACK_TYPE") "0201_FF")
        (field (name "PHYS_PAGE") "2")
        (field (name "POWER_RATING") "N/A")
        (field (name "RES") "N/A")
        (field (name "TEMP_RANGE") "N/A")
        (field (name "TOLERANCE") "N/A")
        (field (name "VER") "2")
        (field (name "VLOG_PARAM01") "N/A")
      )
      (libsource (lib "eagle-import") (part "EK_RES_SMD"))
    )
    (comp (ref "R12")
      (value "OPEN")
      (footprint "eagle-import:RESC0603X23L")
      (description "RESISTOR: 0201: OPEN: FORMFACTOR")
      (fields
        (field (name "CASE") "SMT (0201)")
        (field (name "MANUFACTURER") "N/A")
        (field (name "MAXINV") "N/A")
        (field (name "MFG_PART_NUMBER") "N/A")
        (field (name "ORIGINALSYMBOLORIGIN") "(-75,50)")
        (field (name "PACK_TYPE") "0201_FF")
        (field (name "PHYS_PAGE") "2")
        (field (name "POWER_RATING") "N/A")
        (field (name "RES") "N/A")
        (field (name "TEMP_RANGE") "N/A")
        (field (name "TOLERANCE") "N/A")
        (field (name "VER") "2")
        (field (name "VLOG_PARAM01") "N/A")
      )
      (libsource (lib "eagle-import") (part "EK_RES_SMD"))
    )
    (comp (ref "R13")
      (value "4.7K")
      (footprint "eagle-import:RESC0603X26M")
      (description "RES: SMT (0201): 4.7K: 1%: +/-200PPM/DEGC: 0.0500W")
      (fields
        (field (name "CASE") "SMT (0201)")
        (field (name "MANUFACTURER") "PANASONIC")
        (field (name "MATERIAL_TYPE") "THICK FILM")
        (field (name "MAXINV") "ER111000003379")
        (field (name "MFG_PART_NUMBER") "ERJ-1GNF4701")
        (field (name "ORIGINALSYMBOLORIGIN") "(-50,75)")
        (field (name "PACK_TYPE") "0201RES")
        (field (name "PHYS_PAGE") "2")
        (field (name "POWER_RATING") "0.05W")
        (field (name "REFLOW") "-")
        (field (name "RES") "4.70E03")
        (field (name "TEMP_RANGE") "-55 DEGC TO +125 DEGC")
        (field (name "TOLERANCE") "1%")
        (field (name "VER") "4")
        (field (name "VLOG_PARAM01") "RES:INTEGER")
      )
      (libsource (lib "eagle-import") (part "RES_SMD#1RES_SMD#1"))
    )
    (comp (ref "R16")
      (value "3.3K")
      (footprint "eagle-import:RESC0603X33M")
      (description "RES: SMT (0201): 3.3K: 1%: +/-100PPM/DEGC: 0.0500W")
      (fields
        (field (name "CASE") "SMT (0201)")
        (field (name "MANUFACTURER") "PANASONIC")
        (field (name "MAXINV") "80-003K3-95")
        (field (name "MFG_PART_NUMBER") "ERJ-1GEF3301C")
        (field (name "ORIGINALSYMBOLORIGIN") "(-75,50)")
        (field (name "PACK_TYPE") "0201RES")
        (field (name "PHYS_PAGE") "2")
        (field (name "POWER_RATING") "0.05W")
        (field (name "RES") "3.30E03")
        (field (name "TEMP_RANGE") "-55 DEGC TO +155 DEGC")
        (field (name "TOLERANCE") "1%")
        (field (name "VER") "2")
        (field (name "VLOG_PARAM01") "RES:INTEGER")
      )
      (libsource (lib "eagle-import") (part "RES_SMDRES_SMD_1"))
    )
    (comp (ref "R17")
      (value "OPEN")
      (footprint "eagle-import:RESC0603X23L")
      (description "RESISTOR: 0201: OPEN: FORMFACTOR")
      (fields
        (field (name "CASE") "SMT (0201)")
        (field (name "MANUFACTURER") "N/A")
        (field (name "MAXINV") "N/A")
        (field (name "MFG_PART_NUMBER") "N/A")
        (field (name "ORIGINALSYMBOLORIGIN") "(-75,50)")
        (field (name "PACK_TYPE") "0201_FF")
        (field (name "PHYS_PAGE") "2")
        (field (name "POWER_RATING") "N/A")
        (field (name "RES") "N/A")
        (field (name "TEMP_RANGE") "N/A")
        (field (name "TOLERANCE") "N/A")
        (field (name "VER") "2")
        (field (name "VLOG_PARAM01") "N/A")
      )
      (libsource (lib "eagle-import") (part "EK_RES_SMD"))
    )
    (comp (ref "R18")
      (value "OPEN")
      (footprint "eagle-import:RESC0603X23L")
      (description "RESISTOR: 0201: OPEN: FORMFACTOR")
      (fields
        (field (name "CASE") "SMT (0201)")
        (field (name "MANUFACTURER") "N/A")
        (field (name "MAXINV") "N/A")
        (field (name "MFG_PART_NUMBER") "N/A")
        (field (name "ORIGINALSYMBOLORIGIN") "(-75,50)")
        (field (name "PACK_TYPE") "0201_FF")
        (field (name "PHYS_PAGE") "2")
        (field (name "POWER_RATING") "N/A")
        (field (name "RES") "N/A")
        (field (name "TEMP_RANGE") "N/A")
        (field (name "TOLERANCE") "N/A")
        (field (name "VER") "2")
        (field (name "VLOG_PARAM01") "N/A")
      )
      (libsource (lib "eagle-import") (part "EK_RES_SMD"))
    )
    (comp (ref "R19")
      (value "4.7K")
      (footprint "eagle-import:RESC0603X26M")
      (description "RES: SMT (0201): 4.7K: 1%: +/-200PPM/DEGC: 0.0500W")
      (fields
        (field (name "CASE") "SMT (0201)")
        (field (name "MANUFACTURER") "PANASONIC")
        (field (name "MATERIAL_TYPE") "THICK FILM")
        (field (name "MAXINV") "ER111000003379")
        (field (name "MFG_PART_NUMBER") "ERJ-1GNF4701")
        (field (name "ORIGINALSYMBOLORIGIN") "(-75,50)")
        (field (name "PACK_TYPE") "0201RES")
        (field (name "PHYS_PAGE") "2")
        (field (name "POWER_RATING") "0.05W")
        (field (name "REFLOW") "-")
        (field (name "RES") "4.70E03")
        (field (name "TEMP_RANGE") "-55 DEGC TO +125 DEGC")
        (field (name "TOLERANCE") "1%")
        (field (name "VER") "2")
        (field (name "VLOG_PARAM01") "RES:INTEGER")
      )
      (libsource (lib "eagle-import") (part "RES_SMDRES_SMD"))
    )
    (comp (ref "R20")
      (value "4.7K")
      (footprint "eagle-import:RESC0603X26M")
      (description "RES: SMT (0201): 4.7K: 1%: +/-200PPM/DEGC: 0.0500W")
      (fields
        (field (name "CASE") "SMT (0201)")
        (field (name "MANUFACTURER") "PANASONIC")
        (field (name "MATERIAL_TYPE") "THICK FILM")
        (field (name "MAXINV") "ER111000003379")
        (field (name "MFG_PART_NUMBER") "ERJ-1GNF4701")
        (field (name "ORIGINALSYMBOLORIGIN") "(-75,50)")
        (field (name "PACK_TYPE") "0201RES")
        (field (name "PHYS_PAGE") "2")
        (field (name "POWER_RATING") "0.05W")
        (field (name "REFLOW") "-")
        (field (name "RES") "4.70E03")
        (field (name "TEMP_RANGE") "-55 DEGC TO +125 DEGC")
        (field (name "TOLERANCE") "1%")
        (field (name "VER") "2")
        (field (name "VLOG_PARAM01") "RES:INTEGER")
      )
      (libsource (lib "eagle-import") (part "RES_SMDRES_SMD"))
    )
    (comp (ref "R21")
      (value "OPEN")
      (footprint "eagle-import:RESC0603X23L")
      (description "RESISTOR: 0201: OPEN: FORMFACTOR")
      (fields
        (field (name "CASE") "SMT (0201)")
        (field (name "MANUFACTURER") "N/A")
        (field (name "MAXINV") "N/A")
        (field (name "MFG_PART_NUMBER") "N/A")
        (field (name "ORIGINALSYMBOLORIGIN") "(-75,50)")
        (field (name "PACK_TYPE") "0201_FF")
        (field (name "PHYS_PAGE") "2")
        (field (name "POWER_RATING") "N/A")
        (field (name "RES") "N/A")
        (field (name "TEMP_RANGE") "N/A")
        (field (name "TOLERANCE") "N/A")
        (field (name "VER") "2")
        (field (name "VLOG_PARAM01") "N/A")
      )
      (libsource (lib "eagle-import") (part "EK_RES_SMD"))
    )
    (comp (ref "R22")
      (value "0")
      (footprint "eagle-import:RESC0603X33M")
      (description "RES: SMT (0201): 0: 1%: JUMPER: 0.0500W")
      (fields
        (field (name "MANUFACTURER") "VISHAY DALE:PANASONIC")
        (field (name "MAXINV") "80-0000R-95")
        (field (name "ORIGINALSYMBOLORIGIN") "(-75,50)")
        (field (name "PACK_TYPE") "0201RES")
        (field (name "PHYS_PAGE") "2")
        (field (name "POWER_RATING") "0.05W")
        (field (name "RES") "0.00000001E00")
        (field (name "TEMP_RANGE") "-55 DEGC TO +155 DEGC")
        (field (name "TOLERANCE") "1%")
        (field (name "VER") "2")
        (field (name "VLOG_PARAM01") "RES:INTEGER")
      )
      (libsource (lib "eagle-import") (part "RES_SMDRES_SMD_1"))
    )
    (comp (ref "R23")
      (value "3.3K")
      (footprint "eagle-import:RESC0603X33M")
      (description "RES: SMT (0201): 3.3K: 1%: +/-100PPM/DEGC: 0.0500W")
      (fields
        (field (name "CASE") "SMT (0201)")
        (field (name "MANUFACTURER") "PANASONIC")
        (field (name "MAXINV") "80-003K3-95")
        (field (name "MFG_PART_NUMBER") "ERJ-1GEF3301C")
        (field (name "ORIGINALSYMBOLORIGIN") "(-75,50)")
        (field (name "PACK_TYPE") "0201RES")
        (field (name "PHYS_PAGE") "2")
        (field (name "POWER_RATING") "0.05W")
        (field (name "RES") "3.30E03")
        (field (name "TEMP_RANGE") "-55 DEGC TO +155 DEGC")
        (field (name "TOLERANCE") "1%")
        (field (name "VER") "2")
        (field (name "VLOG_PARAM01") "RES:INTEGER")
      )
      (libsource (lib "eagle-import") (part "RES_SMDRES_SMD_1"))
    )
    (comp (ref "R24")
      (value "3.3K")
      (footprint "eagle-import:RESC0603X33M")
      (description "RES: SMT (0201): 3.3K: 1%: +/-100PPM/DEGC: 0.0500W")
      (fields
        (field (name "CASE") "SMT (0201)")
        (field (name "MANUFACTURER") "PANASONIC")
        (field (name "MAXINV") "80-003K3-95")
        (field (name "MFG_PART_NUMBER") "ERJ-1GEF3301C")
        (field (name "ORIGINALSYMBOLORIGIN") "(-75,50)")
        (field (name "PACK_TYPE") "0201RES")
        (field (name "PHYS_PAGE") "2")
        (field (name "POWER_RATING") "0.05W")
        (field (name "RES") "3.30E03")
        (field (name "TEMP_RANGE") "-55 DEGC TO +155 DEGC")
        (field (name "TOLERANCE") "1%")
        (field (name "VER") "2")
        (field (name "VLOG_PARAM01") "RES:INTEGER")
      )
      (libsource (lib "eagle-import") (part "RES_SMDRES_SMD_1"))
    )
    (comp (ref "R25")
      (value "3.3K")
      (footprint "eagle-import:RESC0603X33M")
      (description "RES: SMT (0201): 3.3K: 1%: +/-100PPM/DEGC: 0.0500W")
      (fields
        (field (name "CASE") "SMT (0201)")
        (field (name "MANUFACTURER") "PANASONIC")
        (field (name "MAXINV") "80-003K3-95")
        (field (name "MFG_PART_NUMBER") "ERJ-1GEF3301C")
        (field (name "ORIGINALSYMBOLORIGIN") "(-75,50)")
        (field (name "PACK_TYPE") "0201RES")
        (field (name "PHYS_PAGE") "2")
        (field (name "POWER_RATING") "0.05W")
        (field (name "RES") "3.30E03")
        (field (name "TEMP_RANGE") "-55 DEGC TO +155 DEGC")
        (field (name "TOLERANCE") "1%")
        (field (name "VER") "2")
        (field (name "VLOG_PARAM01") "RES:INTEGER")
      )
      (libsource (lib "eagle-import") (part "RES_SMDRES_SMD_1"))
    )
    (comp (ref "R26")
      (value "0")
      (footprint "eagle-import:RESC0603X33M")
      (description "RES: SMT (0201): 0: 1%: JUMPER: 0.0500W")
      (fields
        (field (name "MANUFACTURER") "VISHAY DALE:PANASONIC")
        (field (name "MAXINV") "80-0000R-95")
        (field (name "ORIGINALSYMBOLORIGIN") "(-75,50)")
        (field (name "PACK_TYPE") "0201RES")
        (field (name "PHYS_PAGE") "2")
        (field (name "POWER_RATING") "0.05W")
        (field (name "RES") "0.00000001E00")
        (field (name "TEMP_RANGE") "-55 DEGC TO +155 DEGC")
        (field (name "TOLERANCE") "1%")
        (field (name "VER") "2")
        (field (name "VLOG_PARAM01") "RES:INTEGER")
      )
      (libsource (lib "eagle-import") (part "RES_SMDRES_SMD_1"))
    )
    (comp (ref "R27")
      (value "1M")
      (footprint "eagle-import:0402")
      (description "RES: SMT (0402): 1M: 1%: +/-100PPM/DEGC: 0.1000W")
      (fields
        (field (name "CASE") "SMT (0402)")
        (field (name "MANUFACTURER") "PANASONIC")
        (field (name "MAXINV") "80-0001M-18")
        (field (name "MFG_PART_NUMBER") "ERJ-2RKF1004")
        (field (name "ORIGINALSYMBOLORIGIN") "(-75,50)")
        (field (name "PACK_TYPE") "0402RES")
        (field (name "PHYS_PAGE") "2")
        (field (name "POWER_RATING") "0.10W")
        (field (name "RES") "1.00E06")
        (field (name "TEMP_RANGE") "-55 DEGC TO +155 DEGC")
        (field (name "TOLERANCE") "1%")
        (field (name "VER") "2")
        (field (name "VLOG_PARAM01") "RES:INTEGER")
      )
      (libsource (lib "eagle-import") (part "RES_SMDRES_SMD_2"))
    )
    (comp (ref "R28")
      (value "0")
      (footprint "eagle-import:RESC0603X33M")
      (description "RES: SMT (0201): 0: 1%: JUMPER: 0.0500W")
      (fields
        (field (name "MANUFACTURER") "VISHAY DALE:PANASONIC")
        (field (name "MAXINV") "80-0000R-95")
        (field (name "ORIGINALSYMBOLORIGIN") "(-75,50)")
        (field (name "PACK_TYPE") "0201RES")
        (field (name "PHYS_PAGE") "2")
        (field (name "POWER_RATING") "0.05W")
        (field (name "RES") "0.00000001E00")
        (field (name "TEMP_RANGE") "-55 DEGC TO +155 DEGC")
        (field (name "TOLERANCE") "1%")
        (field (name "VER") "2")
        (field (name "VLOG_PARAM01") "RES:INTEGER")
      )
      (libsource (lib "eagle-import") (part "RES_SMDRES_SMD_1"))
    )
    (comp (ref "R29")
      (value "0")
      (footprint "eagle-import:RESC0603X33M")
      (description "RES: SMT (0201): 0: 1%: JUMPER: 0.0500W")
      (fields
        (field (name "MANUFACTURER") "VISHAY DALE:PANASONIC")
        (field (name "MAXINV") "80-0000R-95")
        (field (name "ORIGINALSYMBOLORIGIN") "(-75,50)")
        (field (name "PACK_TYPE") "0201RES")
        (field (name "PHYS_PAGE") "2")
        (field (name "POWER_RATING") "0.05W")
        (field (name "RES") "0.00000001E00")
        (field (name "TEMP_RANGE") "-55 DEGC TO +155 DEGC")
        (field (name "TOLERANCE") "1%")
        (field (name "VER") "2")
        (field (name "VLOG_PARAM01") "RES:INTEGER")
      )
      (libsource (lib "eagle-import") (part "RES_SMDRES_SMD_1"))
    )
    (comp (ref "R30")
      (value "OPEN")
      (footprint "eagle-import:RESC0603X23L")
      (description "RESISTOR: 0201: OPEN: FORMFACTOR")
      (fields
        (field (name "CASE") "SMT (0201)")
        (field (name "MANUFACTURER") "N/A")
        (field (name "MAXINV") "N/A")
        (field (name "MFG_PART_NUMBER") "N/A")
        (field (name "ORIGINALSYMBOLORIGIN") "(-75,50)")
        (field (name "PACK_TYPE") "0201_FF")
        (field (name "PHYS_PAGE") "2")
        (field (name "POWER_RATING") "N/A")
        (field (name "RES") "N/A")
        (field (name "TEMP_RANGE") "N/A")
        (field (name "TOLERANCE") "N/A")
        (field (name "VER") "2")
        (field (name "VLOG_PARAM01") "N/A")
      )
      (libsource (lib "eagle-import") (part "EK_RES_SMD"))
    )
    (comp (ref "R31")
      (value "0")
      (footprint "eagle-import:RESC0603X33M")
      (description "RES: SMT (0201): 0: 1%: JUMPER: 0.0500W")
      (fields
        (field (name "MANUFACTURER") "VISHAY DALE:PANASONIC")
        (field (name "MAXINV") "80-0000R-95")
        (field (name "ORIGINALSYMBOLORIGIN") "(-75,50)")
        (field (name "PACK_TYPE") "0201RES")
        (field (name "PHYS_PAGE") "2")
        (field (name "POWER_RATING") "0.05W")
        (field (name "RES") "0.00000001E00")
        (field (name "TEMP_RANGE") "-55 DEGC TO +155 DEGC")
        (field (name "TOLERANCE") "1%")
        (field (name "VER") "2")
        (field (name "VLOG_PARAM01") "RES:INTEGER")
      )
      (libsource (lib "eagle-import") (part "RES_SMDRES_SMD_1"))
    )
    (comp (ref "R32")
      (value "0")
      (footprint "eagle-import:RESC0603X33M")
      (description "RES: SMT (0201): 0: 1%: JUMPER: 0.0500W")
      (fields
        (field (name "MANUFACTURER") "VISHAY DALE:PANASONIC")
        (field (name "MAXINV") "80-0000R-95")
        (field (name "ORIGINALSYMBOLORIGIN") "(-75,50)")
        (field (name "PACK_TYPE") "0201RES")
        (field (name "PHYS_PAGE") "2")
        (field (name "POWER_RATING") "0.05W")
        (field (name "RES") "0.00000001E00")
        (field (name "TEMP_RANGE") "-55 DEGC TO +155 DEGC")
        (field (name "TOLERANCE") "1%")
        (field (name "VER") "2")
        (field (name "VLOG_PARAM01") "RES:INTEGER")
      )
      (libsource (lib "eagle-import") (part "RES_SMDRES_SMD_1"))
    )
    (comp (ref "R33")
      (value "0")
      (footprint "eagle-import:RESC0603X33M")
      (description "RES: SMT (0201): 0: 1%: JUMPER: 0.0500W")
      (fields
        (field (name "MANUFACTURER") "VISHAY DALE:PANASONIC")
        (field (name "MAXINV") "80-0000R-95")
        (field (name "ORIGINALSYMBOLORIGIN") "(-75,50)")
        (field (name "PACK_TYPE") "0201RES")
        (field (name "PHYS_PAGE") "2")
        (field (name "POWER_RATING") "0.05W")
        (field (name "RES") "0.00000001E00")
        (field (name "TEMP_RANGE") "-55 DEGC TO +155 DEGC")
        (field (name "TOLERANCE") "1%")
        (field (name "VER") "2")
        (field (name "VLOG_PARAM01") "RES:INTEGER")
      )
      (libsource (lib "eagle-import") (part "RES_SMDRES_SMD_1"))
    )
    (comp (ref "R34")
      (value "0")
      (footprint "eagle-import:RESC0603X33M")
      (description "RES: SMT (0201): 0: 1%: JUMPER: 0.0500W")
      (fields
        (field (name "MANUFACTURER") "VISHAY DALE:PANASONIC")
        (field (name "MAXINV") "80-0000R-95")
        (field (name "ORIGINALSYMBOLORIGIN") "(-75,50)")
        (field (name "PACK_TYPE") "0201RES")
        (field (name "PHYS_PAGE") "2")
        (field (name "POWER_RATING") "0.05W")
        (field (name "RES") "0.00000001E00")
        (field (name "TEMP_RANGE") "-55 DEGC TO +155 DEGC")
        (field (name "TOLERANCE") "1%")
        (field (name "VER") "2")
        (field (name "VLOG_PARAM01") "RES:INTEGER")
      )
      (libsource (lib "eagle-import") (part "RES_SMDRES_SMD_1"))
    )
    (comp (ref "R35")
      (value "0")
      (footprint "eagle-import:RESC0603X33M")
      (description "RES: SMT (0201): 0: 1%: JUMPER: 0.0500W")
      (fields
        (field (name "MANUFACTURER") "VISHAY DALE:PANASONIC")
        (field (name "MAXINV") "80-0000R-95")
        (field (name "ORIGINALSYMBOLORIGIN") "(-75,50)")
        (field (name "PACK_TYPE") "0201RES")
        (field (name "PHYS_PAGE") "2")
        (field (name "POWER_RATING") "0.05W")
        (field (name "RES") "0.00000001E00")
        (field (name "TEMP_RANGE") "-55 DEGC TO +155 DEGC")
        (field (name "TOLERANCE") "1%")
        (field (name "VER") "2")
        (field (name "VLOG_PARAM01") "RES:INTEGER")
      )
      (libsource (lib "eagle-import") (part "RES_SMDRES_SMD_1"))
    )
    (comp (ref "R36")
      (value "0")
      (footprint "eagle-import:RESC0603X33M")
      (description "RES: SMT (0201): 0: 1%: JUMPER: 0.0500W")
      (fields
        (field (name "MANUFACTURER") "VISHAY DALE:PANASONIC")
        (field (name "MAXINV") "80-0000R-95")
        (field (name "ORIGINALSYMBOLORIGIN") "(-75,50)")
        (field (name "PACK_TYPE") "0201RES")
        (field (name "PHYS_PAGE") "2")
        (field (name "POWER_RATING") "0.05W")
        (field (name "RES") "0.00000001E00")
        (field (name "TEMP_RANGE") "-55 DEGC TO +155 DEGC")
        (field (name "TOLERANCE") "1%")
        (field (name "VER") "2")
        (field (name "VLOG_PARAM01") "RES:INTEGER")
      )
      (libsource (lib "eagle-import") (part "RES_SMDRES_SMD_1"))
    )
    (comp (ref "R37")
      (value "10")
      (footprint "eagle-import:RESC0603X33M")
      (description "RES: SMT (0201): 10: 1%: +/-100PPM/DEGC: 0.0500W")
      (fields
        (field (name "CASE") "SMT (0201)")
        (field (name "MANUFACTURER") "PANASONIC")
        (field (name "MAXINV") "80-0010R-95")
        (field (name "MFG_PART_NUMBER") "ERJ-1GEF10R0")
        (field (name "ORIGINALSYMBOLORIGIN") "(-75,50)")
        (field (name "PACK_TYPE") "0201RES")
        (field (name "PHYS_PAGE") "2")
        (field (name "POWER_RATING") "0.05W")
        (field (name "RES") "1.00E01")
        (field (name "TEMP_RANGE") "-55 DEGC TO +155 DEGC")
        (field (name "TOLERANCE") "1%")
        (field (name "VER") "2")
        (field (name "VLOG_PARAM01") "RES:INTEGER")
      )
      (libsource (lib "eagle-import") (part "RES_SMDRES_SMD_1"))
    )
    (comp (ref "R38")
      (value "OPEN")
      (footprint "eagle-import:RESC0603X23L")
      (description "RESISTOR: 0201: OPEN: FORMFACTOR")
      (fields
        (field (name "CASE") "SMT (0201)")
        (field (name "MANUFACTURER") "N/A")
        (field (name "MAXINV") "N/A")
        (field (name "MFG_PART_NUMBER") "N/A")
        (field (name "ORIGINALSYMBOLORIGIN") "(-75,50)")
        (field (name "PACK_TYPE") "0201_FF")
        (field (name "PHYS_PAGE") "2")
        (field (name "POWER_RATING") "N/A")
        (field (name "RES") "N/A")
        (field (name "TEMP_RANGE") "N/A")
        (field (name "TOLERANCE") "N/A")
        (field (name "VER") "2")
        (field (name "VLOG_PARAM01") "N/A")
      )
      (libsource (lib "eagle-import") (part "EK_RES_SMD"))
    )
    (comp (ref "R39")
      (value "OPEN")
      (footprint "eagle-import:RESC0603X23L")
      (description "RESISTOR: 0201: OPEN: FORMFACTOR")
      (fields
        (field (name "CASE") "SMT (0201)")
        (field (name "MANUFACTURER") "N/A")
        (field (name "MAXINV") "N/A")
        (field (name "MFG_PART_NUMBER") "N/A")
        (field (name "ORIGINALSYMBOLORIGIN") "(-75,50)")
        (field (name "PACK_TYPE") "0201_FF")
        (field (name "PHYS_PAGE") "2")
        (field (name "POWER_RATING") "N/A")
        (field (name "RES") "N/A")
        (field (name "TEMP_RANGE") "N/A")
        (field (name "TOLERANCE") "N/A")
        (field (name "VER") "2")
        (field (name "VLOG_PARAM01") "N/A")
      )
      (libsource (lib "eagle-import") (part "EK_RES_SMD"))
    )
    (comp (ref "R40")
      (value "0")
      (footprint "eagle-import:RESC0603X33M")
      (description "RES: SMT (0201): 0: 1%: JUMPER: 0.0500W")
      (fields
        (field (name "MANUFACTURER") "VISHAY DALE:PANASONIC")
        (field (name "MAXINV") "80-0000R-95")
        (field (name "ORIGINALSYMBOLORIGIN") "(-75,50)")
        (field (name "PACK_TYPE") "0201RES")
        (field (name "PHYS_PAGE") "2")
        (field (name "POWER_RATING") "0.05W")
        (field (name "RES") "0.00000001E00")
        (field (name "TEMP_RANGE") "-55 DEGC TO +155 DEGC")
        (field (name "TOLERANCE") "1%")
        (field (name "VER") "2")
        (field (name "VLOG_PARAM01") "RES:INTEGER")
      )
      (libsource (lib "eagle-import") (part "RES_SMDRES_SMD_1"))
    )
    (comp (ref "R41")
      (value "OPEN")
      (footprint "eagle-import:RESC0603X23L")
      (description "RESISTOR: 0201: OPEN: FORMFACTOR")
      (fields
        (field (name "CASE") "SMT (0201)")
        (field (name "MANUFACTURER") "N/A")
        (field (name "MAXINV") "N/A")
        (field (name "MFG_PART_NUMBER") "N/A")
        (field (name "ORIGINALSYMBOLORIGIN") "(-75,50)")
        (field (name "PACK_TYPE") "0201_FF")
        (field (name "PHYS_PAGE") "2")
        (field (name "POWER_RATING") "N/A")
        (field (name "RES") "N/A")
        (field (name "TEMP_RANGE") "N/A")
        (field (name "TOLERANCE") "N/A")
        (field (name "VER") "2")
        (field (name "VLOG_PARAM01") "N/A")
      )
      (libsource (lib "eagle-import") (part "EK_RES_SMD"))
    )
    (comp (ref "R42")
      (value "0")
      (footprint "eagle-import:RESC0603X33M")
      (description "RES: SMT (0201): 0: 1%: JUMPER: 0.0500W")
      (fields
        (field (name "MANUFACTURER") "VISHAY DALE:PANASONIC")
        (field (name "MAXINV") "80-0000R-95")
        (field (name "ORIGINALSYMBOLORIGIN") "(-75,50)")
        (field (name "PACK_TYPE") "0201RES")
        (field (name "PHYS_PAGE") "2")
        (field (name "POWER_RATING") "0.05W")
        (field (name "RES") "0.00000001E00")
        (field (name "TEMP_RANGE") "-55 DEGC TO +155 DEGC")
        (field (name "TOLERANCE") "1%")
        (field (name "VER") "2")
        (field (name "VLOG_PARAM01") "RES:INTEGER")
      )
      (libsource (lib "eagle-import") (part "RES_SMDRES_SMD_1"))
    )
    (comp (ref "R72")
      (value "0")
      (footprint "eagle-import:RESC0603X33M")
      (description "RES: SMT (0201): 0: 1%: JUMPER: 0.0500W")
      (fields
        (field (name "MANUFACTURER") "VISHAY DALE:PANASONIC")
        (field (name "MAXINV") "80-0000R-95")
        (field (name "ORIGINALSYMBOLORIGIN") "(-75,50)")
        (field (name "PACK_TYPE") "0201RES")
        (field (name "PHYS_PAGE") "2")
        (field (name "POWER_RATING") "0.05W")
        (field (name "RES") "0.00000001E00")
        (field (name "TEMP_RANGE") "-55 DEGC TO +155 DEGC")
        (field (name "TOLERANCE") "1%")
        (field (name "VER") "2")
        (field (name "VLOG_PARAM01") "RES:INTEGER")
      )
      (libsource (lib "eagle-import") (part "RES_SMDRES_SMD_1"))
    )
    (comp (ref "R73")
      (value "10K")
      (footprint "eagle-import:RESC0603X33M")
      (description "RES: SMT (0201): 10K: 5%: +/-200PPM/DEGC: 0.0500W")
      (fields
        (field (name "CASE") "SMT (0201)")
        (field (name "MANUFACTURER") "PANASONIC")
        (field (name "MATERIAL_TYPE") "THICK FILM")
        (field (name "MAXINV") "80-0010K-AA89")
        (field (name "MFG_PART_NUMBER") "ERJ-1GNJ103")
        (field (name "ORIGINALSYMBOLORIGIN") "(-75,50)")
        (field (name "PACK_TYPE") "0201RES")
        (field (name "PHYS_PAGE") "2")
        (field (name "POWER_RATING") "0.05W")
        (field (name "REFLOW") "-")
        (field (name "RES") "1.00E04")
        (field (name "TEMP_RANGE") "-55 DEGC TO +125 DEGC")
        (field (name "TOLERANCE") "5%")
        (field (name "VER") "2")
        (field (name "VLOG_PARAM01") "RES:INTEGER")
      )
      (libsource (lib "eagle-import") (part "RES_SMDRES_SMD_1"))
    )
    (comp (ref "R74")
      (value "10K")
      (footprint "eagle-import:RESC0603X33M")
      (description "RES: SMT (0201): 10K: 5%: +/-200PPM/DEGC: 0.0500W")
      (fields
        (field (name "CASE") "SMT (0201)")
        (field (name "MANUFACTURER") "PANASONIC")
        (field (name "MATERIAL_TYPE") "THICK FILM")
        (field (name "MAXINV") "80-0010K-AA89")
        (field (name "MFG_PART_NUMBER") "ERJ-1GNJ103")
        (field (name "ORIGINALSYMBOLORIGIN") "(-75,50)")
        (field (name "PACK_TYPE") "0201RES")
        (field (name "PHYS_PAGE") "2")
        (field (name "POWER_RATING") "0.05W")
        (field (name "REFLOW") "-")
        (field (name "RES") "1.00E04")
        (field (name "TEMP_RANGE") "-55 DEGC TO +125 DEGC")
        (field (name "TOLERANCE") "5%")
        (field (name "VER") "2")
        (field (name "VLOG_PARAM01") "RES:INTEGER")
      )
      (libsource (lib "eagle-import") (part "RES_SMDRES_SMD_1"))
    )
    (comp (ref "R75")
      (value "0")
      (footprint "eagle-import:RESC0603X33M")
      (description "RES: SMT (0201): 0: 1%: JUMPER: 0.0500W")
      (fields
        (field (name "MANUFACTURER") "VISHAY DALE:PANASONIC")
        (field (name "MAXINV") "80-0000R-95")
        (field (name "ORIGINALSYMBOLORIGIN") "(-75,50)")
        (field (name "PACK_TYPE") "0201RES")
        (field (name "PHYS_PAGE") "2")
        (field (name "POWER_RATING") "0.05W")
        (field (name "RES") "0.00000001E00")
        (field (name "TEMP_RANGE") "-55 DEGC TO +155 DEGC")
        (field (name "TOLERANCE") "1%")
        (field (name "VER") "2")
        (field (name "VLOG_PARAM01") "RES:INTEGER")
      )
      (libsource (lib "eagle-import") (part "RES_SMDRES_SMD_1"))
    )
    (comp (ref "R76")
      (value "0")
      (footprint "eagle-import:RESC0603X33M")
      (description "RES: SMT (0201): 0: 1%: JUMPER: 0.0500W")
      (fields
        (field (name "MANUFACTURER") "VISHAY DALE:PANASONIC")
        (field (name "MAXINV") "80-0000R-95")
        (field (name "ORIGINALSYMBOLORIGIN") "(-75,50)")
        (field (name "PACK_TYPE") "0201RES")
        (field (name "PHYS_PAGE") "2")
        (field (name "POWER_RATING") "0.05W")
        (field (name "RES") "0.00000001E00")
        (field (name "TEMP_RANGE") "-55 DEGC TO +155 DEGC")
        (field (name "TOLERANCE") "1%")
        (field (name "VER") "2")
        (field (name "VLOG_PARAM01") "RES:INTEGER")
      )
      (libsource (lib "eagle-import") (part "RES_SMDRES_SMD_1"))
    )
    (comp (ref "R77")
      (value "OPEN")
      (footprint "eagle-import:RESC0603X23L")
      (description "RESISTOR: 0201: OPEN: FORMFACTOR")
      (fields
        (field (name "CASE") "SMT (0201)")
        (field (name "MANUFACTURER") "N/A")
        (field (name "MAXINV") "N/A")
        (field (name "MFG_PART_NUMBER") "N/A")
        (field (name "ORIGINALSYMBOLORIGIN") "(-75,50)")
        (field (name "PACK_TYPE") "0201_FF")
        (field (name "PHYS_PAGE") "2")
        (field (name "POWER_RATING") "N/A")
        (field (name "RES") "N/A")
        (field (name "TEMP_RANGE") "N/A")
        (field (name "TOLERANCE") "N/A")
        (field (name "VER") "2")
        (field (name "VLOG_PARAM01") "N/A")
      )
      (libsource (lib "eagle-import") (part "EK_RES_SMD"))
    )
    (comp (ref "R78")
      (value "0")
      (footprint "eagle-import:RESC0603X33M")
      (description "RES: SMT (0201): 0: 1%: JUMPER: 0.0500W")
      (fields
        (field (name "MANUFACTURER") "VISHAY DALE:PANASONIC")
        (field (name "MAXINV") "80-0000R-95")
        (field (name "ORIGINALSYMBOLORIGIN") "(-75,50)")
        (field (name "PACK_TYPE") "0201RES")
        (field (name "PHYS_PAGE") "2")
        (field (name "POWER_RATING") "0.05W")
        (field (name "RES") "0.00000001E00")
        (field (name "TEMP_RANGE") "-55 DEGC TO +155 DEGC")
        (field (name "TOLERANCE") "1%")
        (field (name "VER") "2")
        (field (name "VLOG_PARAM01") "RES:INTEGER")
      )
      (libsource (lib "eagle-import") (part "RES_SMDRES_SMD_1"))
    )
    (comp (ref "R79")
      (value "OPEN")
      (footprint "eagle-import:RESC0603X23L")
      (description "RESISTOR: 0201: OPEN: FORMFACTOR")
      (fields
        (field (name "CASE") "SMT (0201)")
        (field (name "MANUFACTURER") "N/A")
        (field (name "MAXINV") "N/A")
        (field (name "MFG_PART_NUMBER") "N/A")
        (field (name "ORIGINALSYMBOLORIGIN") "(-75,50)")
        (field (name "PACK_TYPE") "0201_FF")
        (field (name "PHYS_PAGE") "2")
        (field (name "POWER_RATING") "N/A")
        (field (name "RES") "N/A")
        (field (name "TEMP_RANGE") "N/A")
        (field (name "TOLERANCE") "N/A")
        (field (name "VER") "2")
        (field (name "VLOG_PARAM01") "N/A")
      )
      (libsource (lib "eagle-import") (part "EK_RES_SMD"))
    )
    (comp (ref "R80")
      (value "OPEN")
      (footprint "eagle-import:RESC0603X23L")
      (description "RESISTOR: 0201: OPEN: FORMFACTOR")
      (fields
        (field (name "CASE") "SMT (0201)")
        (field (name "MANUFACTURER") "N/A")
        (field (name "MAXINV") "N/A")
        (field (name "MFG_PART_NUMBER") "N/A")
        (field (name "ORIGINALSYMBOLORIGIN") "(-75,50)")
        (field (name "PACK_TYPE") "0201_FF")
        (field (name "PHYS_PAGE") "2")
        (field (name "POWER_RATING") "N/A")
        (field (name "RES") "N/A")
        (field (name "TEMP_RANGE") "N/A")
        (field (name "TOLERANCE") "N/A")
        (field (name "VER") "2")
        (field (name "VLOG_PARAM01") "N/A")
      )
      (libsource (lib "eagle-import") (part "EK_RES_SMD"))
    )
    (comp (ref "TP1")
      (value "TP14PAD")
      (footprint "eagle-import:TP_CIR_0-3556")
      (description "TEST POINT: PAD DIA=0.014IN (0.3556MM)")
      (fields
        (field (name "MAXINV") "N/A")
        (field (name "MFG_PART_NUMBER") "N/A")
        (field (name "ORIGINALSYMBOLORIGIN") "(-125,50)")
        (field (name "PACK_TYPE") "EVKIT_TP")
        (field (name "PHYS_PAGE") "2")
        (field (name "TEMP_RANGE") "N/A")
        (field (name "TOLERANCE") "N/A")
        (field (name "VER") "1")
        (field (name "VOLTAGE_RATING") "N/A")
      )
      (libsource (lib "eagle-import") (part "EVKIT_TP"))
    )
    (comp (ref "TP2")
      (value "TP14PAD")
      (footprint "eagle-import:TP_CIR_0-3556")
      (description "TEST POINT: PAD DIA=0.014IN (0.3556MM)")
      (fields
        (field (name "MAXINV") "N/A")
        (field (name "MFG_PART_NUMBER") "N/A")
        (field (name "ORIGINALSYMBOLORIGIN") "(-125,50)")
        (field (name "PACK_TYPE") "EVKIT_TP")
        (field (name "PHYS_PAGE") "2")
        (field (name "TEMP_RANGE") "N/A")
        (field (name "TOLERANCE") "N/A")
        (field (name "VER") "1")
        (field (name "VOLTAGE_RATING") "N/A")
      )
      (libsource (lib "eagle-import") (part "EVKIT_TP"))
    )
    (comp (ref "TP3")
      (value "TP14PAD")
      (footprint "eagle-import:TP_CIR_0-3556")
      (description "TEST POINT: PAD DIA=0.014IN (0.3556MM)")
      (fields
        (field (name "MAXINV") "N/A")
        (field (name "MFG_PART_NUMBER") "N/A")
        (field (name "ORIGINALSYMBOLORIGIN") "(-125,50)")
        (field (name "PACK_TYPE") "EVKIT_TP")
        (field (name "PHYS_PAGE") "2")
        (field (name "TEMP_RANGE") "N/A")
        (field (name "TOLERANCE") "N/A")
        (field (name "VER") "1")
        (field (name "VOLTAGE_RATING") "N/A")
      )
      (libsource (lib "eagle-import") (part "EVKIT_TP"))
    )
    (comp (ref "TP7")
      (value "TP14PAD")
      (footprint "eagle-import:TP_CIR_0-3556")
      (description "TEST POINT: PAD DIA=0.014IN (0.3556MM)")
      (fields
        (field (name "MAXINV") "N/A")
        (field (name "MFG_PART_NUMBER") "N/A")
        (field (name "ORIGINALSYMBOLORIGIN") "(-125,50)")
        (field (name "PACK_TYPE") "EVKIT_TP")
        (field (name "PHYS_PAGE") "2")
        (field (name "TEMP_RANGE") "N/A")
        (field (name "TOLERANCE") "N/A")
        (field (name "VER") "1")
        (field (name "VOLTAGE_RATING") "N/A")
      )
      (libsource (lib "eagle-import") (part "EVKIT_TP"))
    )
    (comp (ref "TP8")
      (value "TP14PAD")
      (footprint "eagle-import:TP_CIR_0-3556")
      (description "TEST POINT: PAD DIA=0.014IN (0.3556MM)")
      (fields
        (field (name "MAXINV") "N/A")
        (field (name "MFG_PART_NUMBER") "N/A")
        (field (name "ORIGINALSYMBOLORIGIN") "(-125,50)")
        (field (name "PACK_TYPE") "EVKIT_TP")
        (field (name "PHYS_PAGE") "2")
        (field (name "TEMP_RANGE") "N/A")
        (field (name "TOLERANCE") "N/A")
        (field (name "VER") "1")
        (field (name "VOLTAGE_RATING") "N/A")
      )
      (libsource (lib "eagle-import") (part "EVKIT_TP"))
    )
    (comp (ref "TP9")
      (value "TP14PAD")
      (footprint "eagle-import:TP_CIR_0-3556")
      (description "TEST POINT: PAD DIA=0.014IN (0.3556MM)")
      (fields
        (field (name "MAXINV") "N/A")
        (field (name "MFG_PART_NUMBER") "N/A")
        (field (name "ORIGINALSYMBOLORIGIN") "(-125,50)")
        (field (name "PACK_TYPE") "EVKIT_TP")
        (field (name "PHYS_PAGE") "2")
        (field (name "TEMP_RANGE") "N/A")
        (field (name "TOLERANCE") "N/A")
        (field (name "VER") "1")
        (field (name "VOLTAGE_RATING") "N/A")
      )
      (libsource (lib "eagle-import") (part "EVKIT_TP"))
    )
    (comp (ref "TP10")
      (value "TP14PAD")
      (footprint "eagle-import:TP_CIR_0-3556")
      (description "TEST POINT: PAD DIA=0.014IN (0.3556MM)")
      (fields
        (field (name "MAXINV") "N/A")
        (field (name "MFG_PART_NUMBER") "N/A")
        (field (name "ORIGINALSYMBOLORIGIN") "(-125,50)")
        (field (name "PACK_TYPE") "EVKIT_TP")
        (field (name "PHYS_PAGE") "2")
        (field (name "TEMP_RANGE") "N/A")
        (field (name "TOLERANCE") "N/A")
        (field (name "VER") "1")
        (field (name "VOLTAGE_RATING") "N/A")
      )
      (libsource (lib "eagle-import") (part "EVKIT_TP"))
    )
    (comp (ref "TP11")
      (value "TP14PAD")
      (footprint "eagle-import:TP_CIR_0-3556")
      (description "TEST POINT: PAD DIA=0.014IN (0.3556MM)")
      (fields
        (field (name "MAXINV") "N/A")
        (field (name "MFG_PART_NUMBER") "N/A")
        (field (name "ORIGINALSYMBOLORIGIN") "(-125,50)")
        (field (name "PACK_TYPE") "EVKIT_TP")
        (field (name "PHYS_PAGE") "2")
        (field (name "TEMP_RANGE") "N/A")
        (field (name "TOLERANCE") "N/A")
        (field (name "VER") "1")
        (field (name "VOLTAGE_RATING") "N/A")
      )
      (libsource (lib "eagle-import") (part "EVKIT_TP"))
    )
    (comp (ref "U2")
      (value "MAX32670GWG+")
      (footprint "eagle-import:MAXIM_21-100511")
      (description "EVKIT PART - IC: MAX32670GWG+: PACKAGE OUTLINE DRAWING: 21-100151: PACKAGE CODE: W241H2+1: WLP24")
      (fields
        (field (name "COMMENTS") "THIS PART NUMBER WILL BE CUSTOMIZED FOR HSP/MRD104 AND UPDATED, CONFIRM THE PART NUMBER BEFORE ORDER")
        (field (name "MANUFACTURER") "MAXIM")
        (field (name "MAXINV") "N/A")
        (field (name "MFG_PART_NUMBER") "MAX32670GWG+")
        (field (name "ORIGINALSYMBOLORIGIN") "(-375,375)")
        (field (name "PACK_TYPE") "WLP24")
        (field (name "PHYS_PAGE") "2")
        (field (name "REFLOW") "-")
        (field (name "SEC_TYPE") "WLP24")
        (field (name "TEMP_RANGE") "N/A")
        (field (name "TOLERANCE") "N/A")
        (field (name "VER") "1")
        (field (name "VOLTAGE_RATING") "N/A")
      )
      (libsource (lib "eagle-import") (part "EK_MAX32670"))
    )
    (comp (ref "U4")
      (value "LIS2DS12")
      (footprint "eagle-import:STMC_LGA-12")
      (description "IC: MEMS: DIGITAL OUTPUT MOTION SENSOR: ULTRA-LOW-POWER HIGH-PERFORMANCE 3-AXIS PICO ACCELEROMETER: MICROELECTROMECHANICAL SYSTEMS: LGA12: NOTE: MANUFACTURER")
      (fields
        (field (name "CASE") "LGA12")
        (field (name "CLASSIFICATION") "MICROELECTROMECHANICAL SYSTEMS")
        (field (name "MANUFACTURER") "ST MICROELECTRONICS")
        (field (name "MAXINV") "EQ111000005315")
        (field (name "MFG_PART_NUMBER") "LIS2DS12")
        (field (name "ORIGINALSYMBOLORIGIN") "(-375,375)")
        (field (name "PACK_TYPE") "LGA12")
        (field (name "PHYS_PAGE") "2")
        (field (name "REFLOW") "-")
        (field (name "TEMP_RANGE") "-40 DEGC TO +85 DEGC")
        (field (name "TOLERANCE") "N/A")
        (field (name "VARIANT") "DNI")
        (field (name "VER") "1")
        (field (name "VOLTAGE_RATING") "+1.62V TO +1.98V")
      )
      (libsource (lib "eagle-import") (part "LIS2DS12"))
    )
    (comp (ref "U6")
      (value "MAX9062EBS+G45")
      (footprint "eagle-import:MAXIM_21-0789")
      (description "IC: COMP: ULTRA-SMALL: LOW-POWER SINGLE COMPARATOR: UCSP4")
      (fields
        (field (name "CASE") "UCSP4")
        (field (name "MANUFACTURER") "MAXIM")
        (field (name "MAXINV") "10-MAX9062EBSG45-B")
        (field (name "MFG_PART_NUMBER") "MAX9062EBS+G45")
        (field (name "ORIGINALSYMBOLORIGIN") "(-250,225)")
        (field (name "PACK_TYPE") "UCSP4")
        (field (name "PHYS_PAGE") "2")
        (field (name "TEMP_RANGE") "-40 DEGC TO +85 DEGC")
        (field (name "TOLERANCE") "N/A")
        (field (name "VER") "1")
        (field (name "VOLTAGE_RATING") "-0.3V TO +5.5V")
      )
      (libsource (lib "eagle-import") (part "MAX9062"))
    )
    (comp (ref "U7")
      (value "MAX9062EBS+G45")
      (footprint "eagle-import:MAXIM_21-0789")
      (description "IC: COMP: ULTRA-SMALL: LOW-POWER SINGLE COMPARATOR: UCSP4")
      (fields
        (field (name "CASE") "UCSP4")
        (field (name "MANUFACTURER") "MAXIM")
        (field (name "MAXINV") "10-MAX9062EBSG45-B")
        (field (name "MFG_PART_NUMBER") "MAX9062EBS+G45")
        (field (name "ORIGINALSYMBOLORIGIN") "(-250,225)")
        (field (name "PACK_TYPE") "UCSP4")
        (field (name "PHYS_PAGE") "2")
        (field (name "TEMP_RANGE") "-40 DEGC TO +85 DEGC")
        (field (name "TOLERANCE") "N/A")
        (field (name "VER") "1")
        (field (name "VOLTAGE_RATING") "-0.3V TO +5.5V")
      )
      (libsource (lib "eagle-import") (part "MAX9062"))
    )
    (comp (ref "U8")
      (value "MAX3207EAUT+")
      (footprint "eagle-import:MAXIM_90-0175")
      (description "IC: PROT: DUAL, QUAD, AND HEX HIGH-SPEED DIFFERENTIAL ESD-PROTECTION IC: SOT23-6")
      (fields
        (field (name "CASE") "SOT23-6")
        (field (name "CLASSIFICATION") "PROTECTION/PROTECTOR")
        (field (name "MANUFACTURER") "MAXIM")
        (field (name "MAXINV") "10-MAX3207EAUT-U")
        (field (name "MFG_PART_NUMBER") "MAX3207EAUT+")
        (field (name "ORIGINALSYMBOLORIGIN") "(-250,225)")
        (field (name "PACK_TYPE") "SOT23-6")
        (field (name "PHYS_PAGE") "2")
        (field (name "REFLOW") "-")
        (field (name "TEMP_RANGE") "-40 DEGC TO +125 DEGC")
        (field (name "TOLERANCE") "N/A")
        (field (name "VER") "1")
        (field (name "VOLTAGE_RATING") "+0.9V TO +5.5V")
      )
      (libsource (lib "eagle-import") (part "MAX3207"))
    )
    (comp (ref "U9")
      (value "MAX4737EBE+")
      (footprint "eagle-import:MAXIM_21-0101_B16-4")
      (description "IC: ASW: 4.5OHM QUAD SPST ANALOG SWITCH IN UCSP: 2X2: UCSP16")
      (fields
        (field (name "CASE") "UCSP16")
        (field (name "MANUFACTURER") "MAXIM")
        (field (name "MAXINV") "10-MAX4737EBE-B")
        (field (name "MFG_PART_NUMBER") "MAX4737EBE+")
        (field (name "ORIGINALSYMBOLORIGIN") "(-250,500)")
        (field (name "PACK_TYPE") "UCSP16_B16-4")
        (field (name "PHYS_PAGE") "2")
        (field (name "SEC_TYPE") "UCSP16_B16-4")
        (field (name "TEMP_RANGE") "-40 DEGC TO +85 DEGC")
        (field (name "TOLERANCE") "N/A")
        (field (name "VER") "1")
        (field (name "VOLTAGE_RATING") "+1.8V TO +5.5V")
      )
      (libsource (lib "eagle-import") (part "MAX4737"))
    )
    (comp (ref "U10")
      (value "MAX4737EBE+")
      (footprint "eagle-import:MAXIM_21-0101_B16-4")
      (description "IC: ASW: 4.5OHM QUAD SPST ANALOG SWITCH IN UCSP: 2X2: UCSP16")
      (fields
        (field (name "CASE") "UCSP16")
        (field (name "MANUFACTURER") "MAXIM")
        (field (name "MAXINV") "10-MAX4737EBE-B")
        (field (name "MFG_PART_NUMBER") "MAX4737EBE+")
        (field (name "ORIGINALSYMBOLORIGIN") "(-250,500)")
        (field (name "PACK_TYPE") "UCSP16_B16-4")
        (field (name "PHYS_PAGE") "2")
        (field (name "SEC_TYPE") "UCSP16_B16-4")
        (field (name "TEMP_RANGE") "-40 DEGC TO +85 DEGC")
        (field (name "TOLERANCE") "N/A")
        (field (name "VER") "1")
        (field (name "VOLTAGE_RATING") "+1.8V TO +5.5V")
      )
      (libsource (lib "eagle-import") (part "MAX4737"))
    )
    (comp (ref "U11")
      (value "MAX14689EWL+")
      (footprint "eagle-import:MAXIM_21-0459_W91B1-7")
      (description "IC: ASW: ULTRA-SMALL LOW-RON BEYOND-THE-RAILS DPDT ANALOG SWITCHES: WLP9")
      (fields
        (field (name "CASE") "WLP9")
        (field (name "MANUFACTURER") "MAXIM")
        (field (name "MAXINV") "10-MAX14689EWL-W")
        (field (name "MFG_PART_NUMBER") "MAX14689EWL+")
        (field (name "ORIGINALSYMBOLORIGIN") "(-150,325)")
        (field (name "PACK_TYPE") "WLP9")
        (field (name "PHYS_PAGE") "2")
        (field (name "SEC_TYPE") "WLP9")
        (field (name "TEMP_RANGE") "-40 DEGC TO +85 DEGC")
        (field (name "TOLERANCE") "N/A")
        (field (name "VER") "1")
        (field (name "VOLTAGE_RATING") "+1.6V TO +5.5V")
      )
      (libsource (lib "eagle-import") (part "MAX14689"))
    )
    (comp (ref "Y3")
      (value "32.7680KHZ")
      (footprint "eagle-import:XTALDFN160X100X50-2M")
      (description "CRYSTAL: SMT 1.6MMX1MM: 6PF: 32.7680KHZ: +/-20PPM")
      (fields
        (field (name "MANUFACTURER") "CITIZEN")
        (field (name "MAXINV") "60-32K76-0ET")
        (field (name "MFG_PART_NUMBER") "CM1610H32768DZB")
        (field (name "ORIGINALSYMBOLORIGIN") "(-125,100)")
        (field (name "PACK_TYPE") "XTALDFN160X100X50-2M")
        (field (name "PHYS_PAGE") "2")
        (field (name "REFLOW") "-")
        (field (name "TEMP_RANGE") "-40 DEGC TO +85 DEGC")
        (field (name "TOLERANCE") "+/-20PPM")
        (field (name "VER") "11")
        (field (name "VOLTAGE_RATING") "N/A")
      )
      (libsource (lib "eagle-import") (part "XTAL"))
    )
  )
  (nets
    (net (code "1") (name "1V8_D") (class "Default")
      (node (ref "C12") (pin "2") (pinfunction "2_2") (pintype "bidirectional"))
      (node (ref "C15") (pin "2") (pinfunction "2_2") (pintype "bidirectional"))
      (node (ref "C35") (pin "2") (pinfunction "2_2") (pintype "bidirectional"))
      (node (ref "C36") (pin "2") (pinfunction "2_2") (pintype "bidirectional"))
      (node (ref "C44") (pin "2") (pinfunction "2_2") (pintype "bidirectional"))
      (node (ref "C7") (pin "2") (pinfunction "2_2") (pintype "bidirectional"))
      (node (ref "C70") (pin "2") (pinfunction "2_2") (pintype "bidirectional"))
      (node (ref "L2") (pin "2") (pinfunction "2_2") (pintype "bidirectional"))
      (node (ref "R24") (pin "2") (pinfunction "2_2") (pintype "bidirectional"))
      (node (ref "R25") (pin "2") (pinfunction "2_2") (pintype "bidirectional"))
      (node (ref "R45") (pin "2") (pinfunction "2_2") (pintype "bidirectional"))
      (node (ref "R73") (pin "1") (pinfunction "1_1") (pintype "bidirectional"))
      (node (ref "R74") (pin "1") (pinfunction "1_1") (pintype "bidirectional"))
      (node (ref "TP1") (pin "1") (pinfunction "TP1_1") (pintype "bidirectional"))
      (node (ref "U1") (pin "F9") (pinfunction "BK2OUT_F9") (pintype "bidirectional"))
      (node (ref "U2") (pin "B2") (pinfunction "VIO_B2") (pintype "bidirectional"))
      (node (ref "U3") (pin "8") (pinfunction "VCC_8") (pintype "input"))
      (node (ref "U4") (pin "10") (pinfunction "VDDIO_10") (pintype "input"))
      (node (ref "U4") (pin "9") (pinfunction "VDD_9") (pintype "input"))
    )
    (net (code "2") (name "1V8_S") (class "Default")
      (node (ref "C13") (pin "2") (pinfunction "2_2") (pintype "bidirectional"))
      (node (ref "J1") (pin "6") (pinfunction "6_6") (pintype "bidirectional"))
      (node (ref "J2") (pin "15") (pinfunction "15_15") (pintype "bidirectional"))
      (node (ref "J2") (pin "20") (pinfunction "20_20") (pintype "bidirectional"))
      (node (ref "R1") (pin "2") (pinfunction "2_2") (pintype "bidirectional"))
      (node (ref "R16") (pin "2") (pinfunction "2_2") (pintype "bidirectional"))
      (node (ref "R22") (pin "2") (pinfunction "2_2") (pintype "bidirectional"))
      (node (ref "R23") (pin "2") (pinfunction "2_2") (pintype "bidirectional"))
      (node (ref "U1") (pin "G5") (pinfunction "LSW2OUT_G5") (pintype "bidirectional"))
      (node (ref "U1") (pin "H6") (pinfunction "LSW1OUT_H6") (pintype "bidirectional"))
    )
    (net (code "3") (name "1V8_SB") (class "Default")
      (node (ref "C51") (pin "2") (pinfunction "2_2") (pintype "bidirectional"))
      (node (ref "L1") (pin "2") (pinfunction "2_2") (pintype "bidirectional"))
      (node (ref "U1") (pin "A3") (pinfunction "BK1OUT_A3") (pintype "bidirectional"))
      (node (ref "U1") (pin "H5") (pinfunction "LSW1IN_H5") (pintype "bidirectional"))
    )
    (net (code "4") (name "1V8_SLDO") (class "Default")
      (node (ref "C9") (pin "2") (pinfunction "2_2") (pintype "bidirectional"))
      (node (ref "U1") (pin "G6") (pinfunction "LSW2IN_G6") (pintype "bidirectional"))
      (node (ref "U1") (pin "H4") (pinfunction "L2OUT_H4") (pintype "bidirectional"))
    )
    (net (code "5") (name "3V3") (class "Default")
      (node (ref "C17") (pin "2") (pinfunction "2_2") (pintype "bidirectional"))
      (node (ref "C26") (pin "2") (pinfunction "2_2") (pintype "bidirectional"))
      (node (ref "C50") (pin "2") (pinfunction "2_2") (pintype "bidirectional"))
      (node (ref "C8") (pin "2") (pinfunction "2_2") (pintype "bidirectional"))
      (node (ref "D1") (pin "2") (pinfunction "A_2") (pintype "bidirectional"))
      (node (ref "D2") (pin "1") (pinfunction "+_1") (pintype "bidirectional"))
      (node (ref "L3") (pin "2") (pinfunction "2_2") (pintype "bidirectional"))
      (node (ref "U1") (pin "G2") (pinfunction "BK3OUT_G2") (pintype "bidirectional"))
      (node (ref "U1") (pin "H3") (pinfunction "L2IN_H3") (pintype "bidirectional"))
      (node (ref "U5") (pin "C11") (pinfunction "VREGI_C11") (pintype "input"))
      (node (ref "U5") (pin "C7") (pinfunction "VREGI_C7") (pintype "input"))
      (node (ref "U5") (pin "D9") (pinfunction "VDDIOH_D9") (pintype "input"))
      (node (ref "U5") (pin "L10") (pinfunction "VDDIOH_L10") (pintype "input"))
      (node (ref "U5") (pin "L2") (pinfunction "VDDIOH_L2") (pintype "input"))
    )
    (net (code "6") (name "3V3_SFO") (class "Default")
      (node (ref "C14") (pin "2") (pinfunction "2_2") (pintype "bidirectional"))
      (node (ref "C3") (pin "1") (pinfunction "1_1") (pintype "bidirectional"))
      (node (ref "C45") (pin "2") (pinfunction "2_2") (pintype "bidirectional"))
      (node (ref "C46") (pin "2") (pinfunction "2_2") (pintype "bidirectional"))
      (node (ref "C47") (pin "2") (pinfunction "2_2") (pintype "bidirectional"))
      (node (ref "C48") (pin "2") (pinfunction "2_2") (pintype "bidirectional"))
      (node (ref "C49") (pin "2") (pinfunction "2_2") (pintype "bidirectional"))
      (node (ref "R13") (pin "1") (pinfunction "1_1") (pintype "bidirectional"))
      (node (ref "U1") (pin "C8") (pinfunction "SFOUT_C8") (pintype "bidirectional"))
      (node (ref "U10") (pin "C2") (pinfunction "V+_C2") (pintype "input"))
      (node (ref "U11") (pin "C2") (pinfunction "VCC_C2") (pintype "input"))
      (node (ref "U5") (pin "G10") (pinfunction "VDDB_G10") (pintype "input"))
      (node (ref "U6") (pin "B1") (pinfunction "VCC_B1") (pintype "input"))
      (node (ref "U7") (pin "B1") (pinfunction "VCC_B1") (pintype "input"))
      (node (ref "U9") (pin "C2") (pinfunction "V+_C2") (pintype "input"))
    )
    (net (code "7") (name "5V0_B") (class "Default")
      (node (ref "C11") (pin "2") (pinfunction "2_2") (pintype "bidirectional"))
      (node (ref "C40") (pin "2") (pinfunction "2_2") (pintype "bidirectional"))
      (node (ref "C42") (pin "2") (pinfunction "2_2") (pintype "bidirectional"))
      (node (ref "J2") (pin "22") (pinfunction "22_22") (pintype "bidirectional"))
      (node (ref "J2") (pin "23") (pinfunction "23_23") (pintype "bidirectional"))
      (node (ref "U1") (pin "B2") (pinfunction "BBOUT_B2") (pintype "bidirectional"))
      (node (ref "U1") (pin "C2") (pinfunction "BBOUT_C2") (pintype "bidirectional"))
    )
    (net (code "8") (name "ACC_INT1") (class "Default")
      (node (ref "R79") (pin "2") (pinfunction "2_2") (pintype "bidirectional"))
      (node (ref "R80") (pin "2") (pinfunction "2_2") (pintype "bidirectional"))
    )
    (net (code "9") (name "ACC_INT2") (class "Default")
      (node (ref "R32") (pin "1") (pinfunction "1_1") (pintype "bidirectional"))
      (node (ref "R61") (pin "1") (pinfunction "1_1") (pintype "bidirectional"))
      (node (ref "R76") (pin "1") (pinfunction "1_1") (pintype "bidirectional"))
      (node (ref "R78") (pin "1") (pinfunction "1_1") (pintype "bidirectional"))
      (node (ref "TP3") (pin "1") (pinfunction "TP1_1") (pintype "bidirectional"))
      (node (ref "U4") (pin "11") (pinfunction "INT2_11") (pintype "input"))
    )
    (net (code "10") (name "AFE_FCLK") (class "Default")
      (node (ref "R30") (pin "2") (pinfunction "2_2") (pintype "bidirectional"))
      (node (ref "R63") (pin "2") (pinfunction "2_2") (pintype "bidirectional"))
      (node (ref "R8") (pin "1") (pinfunction "1_1") (pintype "bidirectional"))
    )
    (net (code "11") (name "AFE_INT1") (class "Default")
      (node (ref "J2") (pin "13") (pinfunction "13_13") (pintype "bidirectional"))
      (node (ref "R35") (pin "2") (pinfunction "2_2") (pintype "bidirectional"))
      (node (ref "R53") (pin "1") (pinfunction "1_1") (pintype "bidirectional"))
    )
    (net (code "12") (name "AFE_INT2") (class "Default")
      (node (ref "R36") (pin "2") (pinfunction "2_2") (pintype "bidirectional"))
      (node (ref "R54") (pin "1") (pinfunction "1_1") (pintype "bidirectional"))
      (node (ref "R77") (pin "2") (pinfunction "2_2") (pintype "bidirectional"))
    )
    (net (code "13") (name "AFE_TRIG") (class "Default")
      (node (ref "R12") (pin "1") (pinfunction "1_1") (pintype "bidirectional"))
      (node (ref "R17") (pin "2") (pinfunction "2_2") (pintype "bidirectional"))
      (node (ref "R38") (pin "2") (pinfunction "2_2") (pintype "bidirectional"))
      (node (ref "R60") (pin "2") (pinfunction "2_2") (pintype "bidirectional"))
    )
    (net (code "14") (name "BUTTON_1") (class "Default")
      (node (ref "R44") (pin "2") (pinfunction "2_2") (pintype "bidirectional"))
      (node (ref "R45") (pin "1") (pinfunction "1_1") (pintype "bidirectional"))
      (node (ref "U5") (pin "J3") (pinfunction "P1.6/SDHC_WP/UART0_CTS/PT6_J3") (pintype "bidirectional"))
    )
    (net (code "15") (name "DEBUG_EN") (class "Default")
      (node (ref "R13") (pin "2") (pinfunction "2_2") (pintype "bidirectional"))
      (node (ref "U10") (pin "A1") (pinfunction "IN2_A1") (pintype "input"))
      (node (ref "U10") (pin "A2") (pinfunction "IN3_A2") (pintype "input"))
      (node (ref "U10") (pin "D3") (pinfunction "IN1_D3") (pintype "input"))
      (node (ref "U10") (pin "D4") (pinfunction "IN4_D4") (pintype "input"))
      (node (ref "U11") (pin "A2") (pinfunction "CB_A2") (pintype "input"))
      (node (ref "U6") (pin "A1") (pinfunction "OUT_A1") (pintype "output"))
      (node (ref "U7") (pin "A1") (pinfunction "OUT_A1") (pintype "output"))
      (node (ref "U9") (pin "A1") (pinfunction "IN2_A1") (pintype "input"))
      (node (ref "U9") (pin "A2") (pinfunction "IN3_A2") (pintype "input"))
      (node (ref "U9") (pin "D3") (pinfunction "IN1_D3") (pintype "input"))
      (node (ref "U9") (pin "D4") (pinfunction "IN4_D4") (pintype "input"))
    )
    (net (code "16") (name "DM0") (class "Default")
      (node (ref "J4") (pin "A7") (pinfunction "A7_A7") (pintype "bidirectional"))
      (node (ref "J4") (pin "B7") (pinfunction "B7_B7") (pintype "bidirectional"))
      (node (ref "R9") (pin "1") (pinfunction "1_1") (pintype "bidirectional"))
      (node (ref "U8") (pin "4") (pinfunction "I/O2_4") (pintype "bidirectional"))
    )
    (net (code "17") (name "DP0") (class "Default")
      (node (ref "J4") (pin "A6") (pinfunction "A6_A6") (pintype "bidirectional"))
      (node (ref "J4") (pin "B6") (pinfunction "B6_B6") (pintype "bidirectional"))
      (node (ref "R10") (pin "1") (pinfunction "1_1") (pintype "bidirectional"))
      (node (ref "U8") (pin "1") (pinfunction "I/O1_1") (pintype "bidirectional"))
    )
    (net (code "18") (name "GND_POWER") (class "Default")
      (node (ref "ANT1") (pin "2") (pinfunction "GND_2") (pintype "input"))
      (node (ref "ANT1") (pin "3") (pinfunction "GND_3") (pintype "input"))
      (node (ref "ANT1") (pin "4") (pinfunction "GND_4") (pintype "input"))
      (node (ref "B-") (pin "1") (pinfunction "TP1_1") (pintype "bidirectional"))
      (node (ref "C1") (pin "1") (pinfunction "1_1") (pintype "bidirectional"))
      (node (ref "C10") (pin "1") (pinfunction "1_1") (pintype "bidirectional"))
      (node (ref "C11") (pin "1") (pinfunction "1_1") (pintype "bidirectional"))
      (node (ref "C12") (pin "1") (pinfunction "1_1") (pintype "bidirectional"))
      (node (ref "C13") (pin "1") (pinfunction "1_1") (pintype "bidirectional"))
      (node (ref "C14") (pin "1") (pinfunction "1_1") (pintype "bidirectional"))
      (node (ref "C15") (pin "1") (pinfunction "1_1") (pintype "bidirectional"))
      (node (ref "C16") (pin "1") (pinfunction "1_1") (pintype "bidirectional"))
      (node (ref "C17") (pin "1") (pinfunction "1_1") (pintype "bidirectional"))
      (node (ref "C19") (pin "1") (pinfunction "1_1") (pintype "bidirectional"))
      (node (ref "C2") (pin "1") (pinfunction "1_1") (pintype "bidirectional"))
      (node (ref "C20") (pin "1") (pinfunction "1_1") (pintype "bidirectional"))
      (node (ref "C21") (pin "1") (pinfunction "1_1") (pintype "bidirectional"))
      (node (ref "C22") (pin "1") (pinfunction "1_1") (pintype "bidirectional"))
      (node (ref "C23") (pin "1") (pinfunction "1_1") (pintype "bidirectional"))
      (node (ref "C24") (pin "1") (pinfunction "1_1") (pintype "bidirectional"))
      (node (ref "C25") (pin "1") (pinfunction "1_1") (pintype "bidirectional"))
      (node (ref "C26") (pin "1") (pinfunction "1_1") (pintype "bidirectional"))
      (node (ref "C27") (pin "1") (pinfunction "1_1") (pintype "bidirectional"))
      (node (ref "C28") (pin "1") (pinfunction "1_1") (pintype "bidirectional"))
      (node (ref "C29") (pin "1") (pinfunction "1_1") (pintype "bidirectional"))
      (node (ref "C3") (pin "2") (pinfunction "2_2") (pintype "bidirectional"))
      (node (ref "C30") (pin "1") (pinfunction "1_1") (pintype "bidirectional"))
      (node (ref "C31") (pin "1") (pinfunction "1_1") (pintype "bidirectional"))
      (node (ref "C32") (pin "1") (pinfunction "1_1") (pintype "bidirectional"))
      (node (ref "C33") (pin "1") (pinfunction "1_1") (pintype "bidirectional"))
      (node (ref "C34") (pin "1") (pinfunction "1_1") (pintype "bidirectional"))
      (node (ref "C35") (pin "1") (pinfunction "1_1") (pintype "bidirectional"))
      (node (ref "C36") (pin "1") (pinfunction "1_1") (pintype "bidirectional"))
      (node (ref "C37") (pin "1") (pinfunction "1_1") (pintype "bidirectional"))
      (node (ref "C39") (pin "1") (pinfunction "1_1") (pintype "bidirectional"))
      (node (ref "C4") (pin "1") (pinfunction "1_1") (pintype "bidirectional"))
      (node (ref "C40") (pin "1") (pinfunction "1_1") (pintype "bidirectional"))
      (node (ref "C41") (pin "1") (pinfunction "1_1") (pintype "bidirectional"))
      (node (ref "C42") (pin "1") (pinfunction "1_1") (pintype "bidirectional"))
      (node (ref "C43") (pin "1") (pinfunction "1_1") (pintype "bidirectional"))
      (node (ref "C44") (pin "1") (pinfunction "1_1") (pintype "bidirectional"))
      (node (ref "C45") (pin "1") (pinfunction "1_1") (pintype "bidirectional"))
      (node (ref "C46") (pin "1") (pinfunction "1_1") (pintype "bidirectional"))
      (node (ref "C47") (pin "1") (pinfunction "1_1") (pintype "bidirectional"))
      (node (ref "C48") (pin "1") (pinfunction "1_1") (pintype "bidirectional"))
      (node (ref "C49") (pin "1") (pinfunction "1_1") (pintype "bidirectional"))
      (node (ref "C5") (pin "1") (pinfunction "1_1") (pintype "bidirectional"))
      (node (ref "C50") (pin "1") (pinfunction "1_1") (pintype "bidirectional"))
      (node (ref "C51") (pin "1") (pinfunction "1_1") (pintype "bidirectional"))
      (node (ref "C52") (pin "1") (pinfunction "1_1") (pintype "bidirectional"))
      (node (ref "C53") (pin "1") (pinfunction "1_1") (pintype "bidirectional"))
      (node (ref "C54") (pin "1") (pinfunction "1_1") (pintype "bidirectional"))
      (node (ref "C55") (pin "1") (pinfunction "1_1") (pintype "bidirectional"))
      (node (ref "C56") (pin "1") (pinfunction "1_1") (pintype "bidirectional"))
      (node (ref "C57") (pin "1") (pinfunction "1_1") (pintype "bidirectional"))
      (node (ref "C58") (pin "1") (pinfunction "1_1") (pintype "bidirectional"))
      (node (ref "C6") (pin "1") (pinfunction "1_1") (pintype "bidirectional"))
      (node (ref "C62") (pin "1") (pinfunction "1_1") (pintype "bidirectional"))
      (node (ref "C63") (pin "1") (pinfunction "1_1") (pintype "bidirectional"))
      (node (ref "C64") (pin "1") (pinfunction "1_1") (pintype "bidirectional"))
      (node (ref "C65") (pin "1") (pinfunction "1_1") (pintype "bidirectional"))
      (node (ref "C66") (pin "1") (pinfunction "1_1") (pintype "bidirectional"))
      (node (ref "C67") (pin "1") (pinfunction "1_1") (pintype "bidirectional"))
      (node (ref "C7") (pin "1") (pinfunction "1_1") (pintype "bidirectional"))
      (node (ref "C70") (pin "1") (pinfunction "1_1") (pintype "bidirectional"))
      (node (ref "C8") (pin "1") (pinfunction "1_1") (pintype "bidirectional"))
      (node (ref "C9") (pin "1") (pinfunction "1_1") (pintype "bidirectional"))
      (node (ref "J1") (pin "1") (pinfunction "1_1") (pintype "bidirectional"))
      (node (ref "J2") (pin "10") (pinfunction "10_10") (pintype "bidirectional"))
      (node (ref "J2") (pin "12") (pinfunction "12_12") (pintype "bidirectional"))
      (node (ref "J2") (pin "14") (pinfunction "14_14") (pintype "bidirectional"))
      (node (ref "J2") (pin "16") (pinfunction "16_16") (pintype "bidirectional"))
      (node (ref "J2") (pin "19") (pinfunction "19_19") (pintype "bidirectional"))
      (node (ref "J2") (pin "2") (pinfunction "2_2") (pintype "bidirectional"))
      (node (ref "J2") (pin "21") (pinfunction "21_21") (pintype "bidirectional"))
      (node (ref "J2") (pin "24") (pinfunction "24_24") (pintype "bidirectional"))
      (node (ref "J2") (pin "4") (pinfunction "4_4") (pintype "bidirectional"))
      (node (ref "J2") (pin "6") (pinfunction "6_6") (pintype "bidirectional"))
      (node (ref "J2") (pin "8") (pinfunction "8_8") (pintype "bidirectional"))
      (node (ref "J4") (pin "A1") (pinfunction "A1_A1") (pintype "bidirectional"))
      (node (ref "J4") (pin "A12") (pinfunction "A12_A12") (pintype "bidirectional"))
      (node (ref "J4") (pin "B1") (pinfunction "B1_B1") (pintype "bidirectional"))
      (node (ref "J4") (pin "B12") (pinfunction "B12_B12") (pintype "bidirectional"))
      (node (ref "L7") (pin "2") (pinfunction "2_2") (pintype "bidirectional"))
      (node (ref "R27") (pin "2") (pinfunction "2_2") (pintype "bidirectional"))
      (node (ref "R37") (pin "1") (pinfunction "1_1") (pintype "bidirectional"))
      (node (ref "R6") (pin "1") (pinfunction "1_1") (pintype "bidirectional"))
      (node (ref "R69") (pin "1") (pinfunction "1_1") (pintype "bidirectional"))
      (node (ref "R7") (pin "1") (pinfunction "1_1") (pintype "bidirectional"))
      (node (ref "RT1") (pin "2") (pinfunction "2_2") (pintype "bidirectional"))
      (node (ref "SW1") (pin "1") (pinfunction "1_1") (pintype "bidirectional"))
      (node (ref "SW1") (pin "3") (pinfunction "3_3") (pintype "bidirectional"))
      (node (ref "SW2") (pin "1") (pinfunction "1_1") (pintype "bidirectional"))
      (node (ref "SW2") (pin "2") (pinfunction "2_2") (pintype "bidirectional"))
      (node (ref "SW2") (pin "5") (pinfunction "5_5") (pintype "bidirectional"))
      (node (ref "TP2") (pin "1") (pinfunction "TP1_1") (pintype "bidirectional"))
      (node (ref "U1") (pin "A2") (pinfunction "BK1GND_A2") (pintype "bidirectional"))
      (node (ref "U1") (pin "A9") (pinfunction "BSTGND_A9") (pintype "bidirectional"))
      (node (ref "U1") (pin "C1") (pinfunction "BBGND_C1") (pintype "bidirectional"))
      (node (ref "U1") (pin "E1") (pinfunction "HDGND_E1") (pintype "bidirectional"))
      (node (ref "U1") (pin "E5") (pinfunction "DGND_E5") (pintype "bidirectional"))
      (node (ref "U1") (pin "E6") (pinfunction "AGND_E6") (pintype "bidirectional"))
      (node (ref "U1") (pin "F5") (pinfunction "GSUB_F5") (pintype "bidirectional"))
      (node (ref "U1") (pin "F6") (pinfunction "AGND_F6") (pintype "bidirectional"))
      (node (ref "U1") (pin "G9") (pinfunction "BK2GND_G9") (pintype "bidirectional"))
      (node (ref "U1") (pin "H2") (pinfunction "BK3GND_H2") (pintype "bidirectional"))
      (node (ref "U10") (pin "B3") (pinfunction "GND_B3") (pintype "input"))
      (node (ref "U11") (pin "B2") (pinfunction "GND_B2") (pintype "input"))
      (node (ref "U2") (pin "C2") (pinfunction "VSS_C2") (pintype "bidirectional"))
      (node (ref "U3") (pin "4") (pinfunction "GND_4") (pintype "input"))
      (node (ref "U3") (pin "9") (pinfunction "EP_9") (pintype "input"))
      (node (ref "U4") (pin "5") (pinfunction "NC_5") (pintype "bidirectional"))
      (node (ref "U4") (pin "6") (pinfunction "GND_6") (pintype "input"))
      (node (ref "U4") (pin "7") (pinfunction "RES_7") (pintype "input"))
      (node (ref "U4") (pin "8") (pinfunction "GND_8") (pintype "input"))
      (node (ref "U5") (pin "A1") (pinfunction "GND_A1") (pintype "input"))
      (node (ref "U5") (pin "A11") (pinfunction "VSSPWR_A11") (pintype "input"))
      (node (ref "U5") (pin "A7") (pinfunction "VSS_A7") (pintype "input"))
      (node (ref "U5") (pin "B1") (pinfunction "VSSA_BT1_B1") (pintype "input"))
      (node (ref "U5") (pin "B10") (pinfunction "VSSPWR_B10") (pintype "input"))
      (node (ref "U5") (pin "B3") (pinfunction "VSSA_BT5_B3") (pintype "input"))
      (node (ref "U5") (pin "B7") (pinfunction "VSSA_B7") (pintype "input"))
      (node (ref "U5") (pin "C1") (pinfunction "VSSA_BT4_C1") (pintype "input"))
      (node (ref "U5") (pin "C2") (pinfunction "VSSA_BT1_C2") (pintype "input"))
      (node (ref "U5") (pin "C4") (pinfunction "VSSA_BT2_C4") (pintype "input"))
      (node (ref "U5") (pin "D4") (pinfunction "VSSA_BT0_D4") (pintype "input"))
      (node (ref "U5") (pin "E10") (pinfunction "VSS_E10") (pintype "input"))
      (node (ref "U5") (pin "E11") (pinfunction "VSS_E11") (pintype "input"))
      (node (ref "U5") (pin "E2") (pinfunction "VSSA_BT3_E2") (pintype "input"))
      (node (ref "U5") (pin "E3") (pinfunction "VSSA_BT0_E3") (pintype "input"))
      (node (ref "U5") (pin "E4") (pinfunction "VSSA_BT0_E4") (pintype "input"))
      (node (ref "U5") (pin "F10") (pinfunction "VSSB_F10") (pintype "input"))
      (node (ref "U5") (pin "F7") (pinfunction "VSS_F7") (pintype "input"))
      (node (ref "U5") (pin "F8") (pinfunction "VSS_F8") (pintype "input"))
      (node (ref "U5") (pin "F9") (pinfunction "VSS_F9") (pintype "input"))
      (node (ref "U5") (pin "G1") (pinfunction "VSS_G1") (pintype "input"))
      (node (ref "U5") (pin "G2") (pinfunction "VSS_G2") (pintype "input"))
      (node (ref "U5") (pin "G3") (pinfunction "VSS_G3") (pintype "input"))
      (node (ref "U5") (pin "H11") (pinfunction "VSS_H11") (pintype "input"))
      (node (ref "U5") (pin "L5") (pinfunction "VSS_L5") (pintype "input"))
      (node (ref "U6") (pin "B2") (pinfunction "GND_B2") (pintype "input"))
      (node (ref "U7") (pin "B2") (pinfunction "GND_B2") (pintype "input"))
      (node (ref "U8") (pin "2") (pinfunction "GND_2") (pintype "input"))
      (node (ref "U9") (pin "B3") (pinfunction "GND_B3") (pintype "input"))
      (node (ref "Y2") (pin "2") (pinfunction "NC1_2") (pintype "bidirectional"))
      (node (ref "Y2") (pin "4") (pinfunction "NC2_4") (pintype "bidirectional"))
    )
    (net (code "19") (name "HDK_RX0") (class "Default")
      (node (ref "J4") (pin "A11") (pinfunction "A11_A11") (pintype "bidirectional"))
      (node (ref "U9") (pin "B4") (pinfunction "COM4_B4") (pintype "input"))
    )
    (net (code "20") (name "HDK_RX1") (class "Default")
      (node (ref "J4") (pin "B11") (pinfunction "B11_B11") (pintype "bidirectional"))
      (node (ref "U10") (pin "B4") (pinfunction "COM4_B4") (pintype "input"))
    )
    (net (code "21") (name "HDK_SWDCLK0") (class "Default")
      (node (ref "J4") (pin "A2") (pinfunction "A2_A2") (pintype "bidirectional"))
      (node (ref "U9") (pin "B1") (pinfunction "COM2_B1") (pintype "input"))
    )
    (net (code "22") (name "HDK_SWDCLK1") (class "Default")
      (node (ref "J4") (pin "B2") (pinfunction "B2_B2") (pintype "bidirectional"))
      (node (ref "U10") (pin "B1") (pinfunction "COM2_B1") (pintype "input"))
    )
    (net (code "23") (name "HDK_SWDIO0") (class "Default")
      (node (ref "J4") (pin "A3") (pinfunction "A3_A3") (pintype "bidirectional"))
      (node (ref "U9") (pin "D1") (pinfunction "COM1_D1") (pintype "input"))
    )
    (net (code "24") (name "HDK_SWDIO1") (class "Default")
      (node (ref "J4") (pin "B3") (pinfunction "B3_B3") (pintype "bidirectional"))
      (node (ref "U10") (pin "D1") (pinfunction "COM1_D1") (pintype "input"))
    )
    (net (code "25") (name "HDK_TX0") (class "Default")
      (node (ref "J4") (pin "A10") (pinfunction "A10_A10") (pintype "bidirectional"))
      (node (ref "U9") (pin "A4") (pinfunction "COM3_A4") (pintype "input"))
    )
    (net (code "26") (name "HDK_TX1") (class "Default")
      (node (ref "J4") (pin "B10") (pinfunction "B10_B10") (pintype "bidirectional"))
      (node (ref "U10") (pin "A4") (pinfunction "COM3_A4") (pintype "input"))
    )
    (net (code "27") (name "HDK_VREF") (class "Default")
      (node (ref "J4") (pin "A8") (pinfunction "A8_A8") (pintype "bidirectional"))
      (node (ref "J4") (pin "B8") (pinfunction "B8_B8") (pintype "bidirectional"))
      (node (ref "U11") (pin "C1") (pinfunction "NO1_C1") (pintype "bidirectional"))
    )
    (net (code "28") (name "I2C0_SCL") (class "Default")
      (node (ref "R25") (pin "1") (pinfunction "1_1") (pintype "bidirectional"))
      (node (ref "U2") (pin "B6") (pinfunction "P0.6_B6") (pintype "bidirectional"))
      (node (ref "U5") (pin "G4") (pinfunction "P1.14/I2C2_SCL/UART1_CTS/PT14/JTAG_TDI_G4") (pintype "bidirectional"))
    )
    (net (code "29") (name "I2C0_SDA") (class "Default")
      (node (ref "R24") (pin "1") (pinfunction "1_1") (pintype "bidirectional"))
      (node (ref "U2") (pin "A6") (pinfunction "P0.7_A6") (pintype "bidirectional"))
      (node (ref "U5") (pin "D5") (pinfunction "P1.15/I2C2_SDA/UART1_RTS/PT15/JTAG_TDO_D5") (pintype "bidirectional"))
    )
    (net (code "30") (name "I2C1_SCL") (class "Default")
      (node (ref "J1") (pin "5") (pinfunction "5_5") (pintype "bidirectional"))
      (node (ref "R20") (pin "1") (pinfunction "1_1") (pintype "bidirectional"))
      (node (ref "U1") (pin "F8") (pinfunction "SCL_F8") (pintype "bidirectional"))
      (node (ref "U5") (pin "F5") (pinfunction "P0.14/I2C1_SCL/QSPI0_SS1/BLE_ANT_CTRL/TMR2_F5") (pintype "bidirectional"))
    )
    (net (code "31") (name "I2C1_SDA") (class "Default")
      (node (ref "J1") (pin "2") (pinfunction "2_2") (pintype "bidirectional"))
      (node (ref "R19") (pin "1") (pinfunction "1_1") (pintype "bidirectional"))
      (node (ref "U1") (pin "E7") (pinfunction "SDA_E7") (pintype "bidirectional"))
      (node (ref "U5") (pin "D6") (pinfunction "P0.15/I2C1_SDA/QSPI0_SS2/BLE_ANT_CTRL/TMR3_D6") (pintype "bidirectional"))
    )
    (net (code "32") (name "I2C2_SCL") (class "Default")
      (node (ref "R21") (pin "1") (pinfunction "1_1") (pintype "bidirectional"))
      (node (ref "R23") (pin "1") (pinfunction "1_1") (pintype "bidirectional"))
      (node (ref "R50") (pin "1") (pinfunction "1_1") (pintype "bidirectional"))
    )
    (net (code "33") (name "I2C2_SDA") (class "Default")
      (node (ref "R16") (pin "1") (pinfunction "1_1") (pintype "bidirectional"))
      (node (ref "R18") (pin "2") (pinfunction "2_2") (pintype "bidirectional"))
      (node (ref "R51") (pin "1") (pinfunction "1_1") (pintype "bidirectional"))
    )
    (net (code "34") (name "INTERCORE_INT_0") (class "Default")
      (node (ref "R62") (pin "1") (pinfunction "1_1") (pintype "bidirectional"))
      (node (ref "U5") (pin "E8") (pinfunction "P0.21/AIN5/AIN2N/QSPI1_SDIO3/UART1_TX/TMR3_E8") (pintype "bidirectional"))
    )
    (net (code "35") (name "INTERCORE_INT_1") (class "Default")
      (node (ref "R64") (pin "1") (pinfunction "1_1") (pintype "bidirectional"))
      (node (ref "U5") (pin "E5") (pinfunction "P1.12/QSPI0_SDIO2/UART1_RX/PT12_E5") (pintype "bidirectional"))
    )
    (net (code "36") (name "LED_BLUE") (class "Default")
      (node (ref "R46") (pin "2") (pinfunction "2_2") (pintype "bidirectional"))
      (node (ref "U5") (pin "K3") (pinfunction "P1.1/SDHC_CMD/SDMA_TDO/PT1_K3") (pintype "bidirectional"))
    )
    (net (code "37") (name "LED_GREEN") (class "Default")
      (node (ref "R47") (pin "2") (pinfunction "2_2") (pintype "bidirectional"))
      (node (ref "U5") (pin "L4") (pinfunction "P1.2/SDHC_DAT0/SDMA_TDI/PT2_L4") (pintype "bidirectional"))
    )
    (net (code "38") (name "LED_RED") (class "Default")
      (node (ref "R48") (pin "2") (pinfunction "2_2") (pintype "bidirectional"))
      (node (ref "U5") (pin "K2") (pinfunction "P1.0/SDHC_DAT3/SDMA_TMS/PT0_K2") (pintype "bidirectional"))
    )
    (net (code "39") (name "MFIO_AH") (class "Default")
      (node (ref "R26") (pin "1") (pinfunction "1_1") (pintype "bidirectional"))
      (node (ref "U5") (pin "K5") (pinfunction "P0.31/PDM_MCLK/QSPI2_SS2/UART2_RTS/TMR1_K5") (pintype "bidirectional"))
    )
    (net (code "40") (name "Net-(ANT1-FEED)") (class "Default")
      (node (ref "ANT1") (pin "1") (pinfunction "FEED_1") (pintype "bidirectional"))
      (node (ref "R5") (pin "2") (pinfunction "2_2") (pintype "bidirectional"))
    )
    (net (code "41") (name "Net-(C38-Pad1)") (class "Default")
      (node (ref "C38") (pin "1") (pinfunction "1_1") (pintype "bidirectional"))
      (node (ref "R37") (pin "2") (pinfunction "2_2") (pintype "bidirectional"))
    )
    (net (code "42") (name "Net-(D2-B)") (class "Default")
      (node (ref "D2") (pin "3") (pinfunction "B_3") (pintype "bidirectional"))
      (node (ref "R46") (pin "1") (pinfunction "1_1") (pintype "bidirectional"))
    )
    (net (code "43") (name "Net-(D2-G)") (class "Default")
      (node (ref "D2") (pin "4") (pinfunction "G_4") (pintype "bidirectional"))
      (node (ref "R47") (pin "1") (pinfunction "1_1") (pintype "bidirectional"))
    )
    (net (code "44") (name "Net-(D2-R)") (class "Default")
      (node (ref "D2") (pin "2") (pinfunction "R_2") (pintype "bidirectional"))
      (node (ref "R48") (pin "1") (pinfunction "1_1") (pintype "bidirectional"))
    )
    (net (code "45") (name "Net-(J2-Pad1)") (class "Default")
      (node (ref "J2") (pin "1") (pinfunction "1_1") (pintype "bidirectional"))
      (node (ref "R17") (pin "1") (pinfunction "1_1") (pintype "bidirectional"))
      (node (ref "R76") (pin "2") (pinfunction "2_2") (pintype "bidirectional"))
      (node (ref "R77") (pin "1") (pinfunction "1_1") (pintype "bidirectional"))
    )
    (net (code "46") (name "Net-(J2-Pad17)") (class "Default")
      (node (ref "J2") (pin "17") (pinfunction "17_17") (pintype "bidirectional"))
      (node (ref "R18") (pin "1") (pinfunction "1_1") (pintype "bidirectional"))
    )
    (net (code "47") (name "Net-(J2-Pad18)") (class "Default")
      (node (ref "J2") (pin "18") (pinfunction "18_18") (pintype "bidirectional"))
      (node (ref "R21") (pin "2") (pinfunction "2_2") (pintype "bidirectional"))
      (node (ref "R8") (pin "2") (pinfunction "2_2") (pintype "bidirectional"))
    )
    (net (code "48") (name "Net-(J2-Pad25)") (class "Default")
      (node (ref "J2") (pin "25") (pinfunction "25_25") (pintype "bidirectional"))
      (node (ref "R78") (pin "2") (pinfunction "2_2") (pintype "bidirectional"))
      (node (ref "R79") (pin "1") (pinfunction "1_1") (pintype "bidirectional"))
    )
    (net (code "49") (name "Net-(R44-Pad1)") (class "Default")
      (node (ref "R44") (pin "1") (pinfunction "1_1") (pintype "bidirectional"))
      (node (ref "SW1") (pin "2") (pinfunction "2_2") (pintype "bidirectional"))
      (node (ref "SW1") (pin "4") (pinfunction "4_4") (pintype "bidirectional"))
    )
    (net (code "50") (name "Net-(U1-BBHVLX)") (class "Default")
      (node (ref "L5") (pin "2") (pinfunction "2_2") (pintype "bidirectional"))
      (node (ref "U1") (pin "D2") (pinfunction "BBHVLX_D2") (pintype "bidirectional"))
    )
    (net (code "51") (name "Net-(U1-BBLVLX)") (class "Default")
      (node (ref "L5") (pin "1") (pinfunction "1_1") (pintype "bidirectional"))
      (node (ref "U1") (pin "D1") (pinfunction "BBLVLX_D1") (pintype "bidirectional"))
    )
    (net (code "52") (name "Net-(U1-BK1LX)") (class "Default")
      (node (ref "L1") (pin "1") (pinfunction "1_1") (pintype "bidirectional"))
      (node (ref "U1") (pin "A1") (pinfunction "BK1LX_A1") (pintype "bidirectional"))
    )
    (net (code "53") (name "Net-(U1-BK2LX)") (class "Default")
      (node (ref "L2") (pin "1") (pinfunction "1_1") (pintype "bidirectional"))
      (node (ref "U1") (pin "H9") (pinfunction "BK2LX_H9") (pintype "bidirectional"))
    )
    (net (code "54") (name "Net-(U1-BK3LX)") (class "Default")
      (node (ref "L3") (pin "1") (pinfunction "1_1") (pintype "bidirectional"))
      (node (ref "U1") (pin "H1") (pinfunction "BK3LX_H1") (pintype "bidirectional"))
    )
    (net (code "55") (name "Net-(U1-ISET)") (class "Default")
      (node (ref "R69") (pin "2") (pinfunction "2_2") (pintype "bidirectional"))
      (node (ref "U1") (pin "D8") (pinfunction "ISET_D8") (pintype "bidirectional"))
    )
    (net (code "56") (name "Net-(U2-P0.2)") (class "Default")
      (node (ref "R28") (pin "2") (pinfunction "2_2") (pintype "bidirectional"))
      (node (ref "U2") (pin "A4") (pinfunction "P0.2_A4") (pintype "bidirectional"))
    )
    (net (code "57") (name "Net-(U2-P0.3)") (class "Default")
      (node (ref "R33") (pin "2") (pinfunction "2_2") (pintype "bidirectional"))
      (node (ref "U2") (pin "B4") (pinfunction "P0.3_B4") (pintype "bidirectional"))
    )
    (net (code "58") (name "Net-(U2-P0.4)") (class "Default")
      (node (ref "R29") (pin "2") (pinfunction "2_2") (pintype "bidirectional"))
      (node (ref "U2") (pin "A5") (pinfunction "P0.4_A5") (pintype "bidirectional"))
    )
    (net (code "59") (name "Net-(U2-P0.5)") (class "Default")
      (node (ref "R34") (pin "2") (pinfunction "2_2") (pintype "bidirectional"))
      (node (ref "U2") (pin "B5") (pinfunction "P0.5_B5") (pintype "bidirectional"))
    )
    (net (code "60") (name "Net-(U2-P0.10)") (class "Default")
      (node (ref "R30") (pin "1") (pinfunction "1_1") (pintype "bidirectional"))
      (node (ref "U2") (pin "D5") (pinfunction "P0.10_D5") (pintype "bidirectional"))
    )
    (net (code "61") (name "Net-(U2-P0.11)") (class "Default")
      (node (ref "R35") (pin "1") (pinfunction "1_1") (pintype "bidirectional"))
      (node (ref "U2") (pin "C5") (pinfunction "P0.11_C5") (pintype "bidirectional"))
    )
    (net (code "62") (name "Net-(U2-P0.12)") (class "Default")
      (node (ref "R36") (pin "1") (pinfunction "1_1") (pintype "bidirectional"))
      (node (ref "U2") (pin "C4") (pinfunction "P0.12_C4") (pintype "bidirectional"))
    )
    (net (code "63") (name "Net-(U2-P0.13)") (class "Default")
      (node (ref "R72") (pin "2") (pinfunction "2_2") (pintype "bidirectional"))
      (node (ref "U2") (pin "D4") (pinfunction "P0.13_D4") (pintype "bidirectional"))
    )
    (net (code "64") (name "Net-(U2-REG1)") (class "Default")
      (node (ref "C37") (pin "2") (pinfunction "2_2") (pintype "bidirectional"))
      (node (ref "U2") (pin "D1") (pinfunction "REG1_D1") (pintype "bidirectional"))
    )
    (net (code "65") (name "Net-(U2-VCORE)") (class "Default")
      (node (ref "C33") (pin "2") (pinfunction "2_2") (pintype "bidirectional"))
      (node (ref "C34") (pin "2") (pinfunction "2_2") (pintype "bidirectional"))
      (node (ref "U2") (pin "A2") (pinfunction "VCORE_A2") (pintype "bidirectional"))
    )
    (net (code "66") (name "Net-(U4-INT1)") (class "Default")
      (node (ref "R38") (pin "1") (pinfunction "1_1") (pintype "bidirectional"))
      (node (ref "R80") (pin "1") (pinfunction "1_1") (pintype "bidirectional"))
      (node (ref "U4") (pin "12") (pinfunction "INT1_12") (pintype "input"))
    )
    (net (code "67") (name "Net-(U5-32KIN)") (class "Default")
      (node (ref "U5") (pin "F1") (pinfunction "32KIN_F1") (pintype "input"))
      (node (ref "Y1") (pin "1") (pinfunction "P1_1") (pintype "input"))
    )
    (net (code "68") (name "Net-(U5-32KOUT)") (class "Default")
      (node (ref "U5") (pin "F2") (pinfunction "32KOUT_F2") (pintype "output"))
      (node (ref "Y1") (pin "2") (pinfunction "P2_2") (pintype "output"))
    )
    (net (code "69") (name "Net-(U5-ANT)") (class "Default")
      (node (ref "R5") (pin "1") (pinfunction "1_1") (pintype "bidirectional"))
      (node (ref "U5") (pin "A2") (pinfunction "ANT_THRU_A2") (pintype "output"))
      (node (ref "U5") (pin "B2") (pinfunction "ANT_B2") (pintype "input"))
    )
    (net (code "70") (name "Net-(U5-HFXIN)") (class "Default")
      (node (ref "C6") (pin "2") (pinfunction "2_2") (pintype "bidirectional"))
      (node (ref "U5") (pin "A4") (pinfunction "HFXIN_A4") (pintype "input"))
      (node (ref "Y2") (pin "1") (pinfunction "P1_1") (pintype "input"))
    )
    (net (code "71") (name "Net-(U5-HFXOUT)") (class "Default")
      (node (ref "C16") (pin "2") (pinfunction "2_2") (pintype "bidirectional"))
      (node (ref "U5") (pin "B4") (pinfunction "HFXOUT_B4") (pintype "output"))
      (node (ref "Y2") (pin "3") (pinfunction "P2_3") (pintype "output"))
    )
    (net (code "72") (name "Net-(U5-LXA)") (class "Default")
      (node (ref "L4") (pin "1") (pinfunction "1_1") (pintype "bidirectional"))
      (node (ref "U5") (pin "B11") (pinfunction "LXA_B11") (pintype "input"))
    )
    (net (code "73") (name "Net-(U5-LXB)") (class "Default")
      (node (ref "C18") (pin "2") (pinfunction "2_2") (pintype "bidirectional"))
      (node (ref "L4") (pin "2") (pinfunction "2_2") (pintype "bidirectional"))
      (node (ref "U5") (pin "A10") (pinfunction "LXB_A10") (pintype "input"))
    )
    (net (code "74") (name "Net-(U5-P0.6{slash}I2C0_SCL{slash}SWDIO2{slash}TMR0)") (class "Default")
      (node (ref "R49") (pin "1") (pinfunction "1_1") (pintype "bidirectional"))
      (node (ref "R50") (pin "2") (pinfunction "2_2") (pintype "bidirectional"))
      (node (ref "U5") (pin "L8") (pinfunction "P0.6/I2C0_SCL/SWDIO2/TMR0_L8") (pintype "bidirectional"))
    )
    (net (code "75") (name "Net-(U5-P0.7{slash}I2C0_SDA{slash}SWCLK2{slash}TMR1)") (class "Default")
      (node (ref "R51") (pin "2") (pinfunction "2_2") (pintype "bidirectional"))
      (node (ref "R52") (pin "1") (pinfunction "1_1") (pintype "bidirectional"))
      (node (ref "U5") (pin "K8") (pinfunction "P0.7/I2C0_SDA/SWCLK2/TMR1_K8") (pintype "bidirectional"))
    )
    (net (code "76") (name "Net-(U5-P0.12{slash}SPIXR_SDIO2{slash}QSPI0_SDIO2{slash}OWM_IO{slash}TMR0)") (class "Default")
      (node (ref "R53") (pin "2") (pinfunction "2_2") (pintype "bidirectional"))
      (node (ref "U5") (pin "G5") (pinfunction "P0.12/SPIXR_SDIO2/QSPI0_SDIO2/OWM_IO/TMR0_G5") (pintype "bidirectional"))
    )
    (net (code "77") (name "Net-(U5-P0.13{slash}SPIXR_SDIO3{slash}QSPI0_SDIO3{slash}OWM_PE{slash}TMR1)") (class "Default")
      (node (ref "R54") (pin "2") (pinfunction "2_2") (pintype "bidirectional"))
      (node (ref "U5") (pin "H5") (pinfunction "P0.13/SPIXR_SDIO3/QSPI0_SDIO3/OWM_PE/TMR1_H5") (pintype "bidirectional"))
    )
    (net (code "78") (name "Net-(U5-P0.16{slash}AIN0{slash}AIN0P{slash}QSPI1_SS0{slash}OWM_IO{slash}TMR4)") (class "Default")
      (node (ref "R55") (pin "2") (pinfunction "2_2") (pintype "bidirectional"))
      (node (ref "U5") (pin "K11") (pinfunction "P0.16/AIN0/AIN0P/QSPI1_SS0/OWM_IO/TMR4_K11") (pintype "bidirectional"))
    )
    (net (code "79") (name "Net-(U5-P0.17{slash}AIN1{slash}AIN0N{slash}QSPI1_MOSI{slash}SDIO0{slash}OWM_PE{slash}TMR5)") (class "Default")
      (node (ref "R56") (pin "2") (pinfunction "2_2") (pintype "bidirectional"))
      (node (ref "U5") (pin "H9") (pinfunction "P0.17/AIN1/AIN0N/QSPI1_MOSI/SDIO0/OWM_PE/TMR5_H9") (pintype "bidirectional"))
    )
    (net (code "80") (name "Net-(U5-P0.18{slash}AIN2{slash}AIN1P{slash}QSPI1_MISO{slash}SDIO1{slash}TMR0{slash}PDOWN)") (class "Default")
      (node (ref "R57") (pin "2") (pinfunction "2_2") (pintype "bidirectional"))
      (node (ref "U5") (pin "G9") (pinfunction "P0.18/AIN2/AIN1P/QSPI1_MISO/SDIO1/TMR0/PDOWN_G9") (pintype "bidirectional"))
    )
    (net (code "81") (name "Net-(U5-P0.19{slash}AIN3{slash}AIN1N{slash}QSPI1_SCK{slash}TMR1{slash}SQWOUT)") (class "Default")
      (node (ref "R58") (pin "2") (pinfunction "2_2") (pintype "bidirectional"))
      (node (ref "U5") (pin "J11") (pinfunction "P0.19/AIN3/AIN1N/QSPI1_SCK/TMR1/SQWOUT_J11") (pintype "bidirectional"))
    )
    (net (code "82") (name "Net-(U5-P0.20{slash}AIN4{slash}AIN2P{slash}QSPI1_SDIO2{slash}UART1_RX{slash}TMR2)") (class "Default")
      (node (ref "R62") (pin "2") (pinfunction "2_2") (pintype "bidirectional"))
      (node (ref "U5") (pin "H10") (pinfunction "P0.20/AIN4/AIN2P/QSPI1_SDIO2/UART1_RX/TMR2_H10") (pintype "bidirectional"))
    )
    (net (code "83") (name "Net-(U5-P0.22{slash}AIN6{slash}AIN3P{slash}QSPI1_SS1{slash}UART1_CTS{slash}TMR4)") (class "Default")
      (node (ref "R59") (pin "2") (pinfunction "2_2") (pintype "bidirectional"))
      (node (ref "U5") (pin "E9") (pinfunction "P0.22/AIN6/AIN3P/QSPI1_SS1/UART1_CTS/TMR4_E9") (pintype "bidirectional"))
    )
    (net (code "84") (name "Net-(U5-P0.23{slash}AIN7{slash}AIN3N{slash}QSPI1_SS2{slash}UART1_RTS{slash}TMR5)") (class "Default")
      (node (ref "R60") (pin "1") (pinfunction "1_1") (pintype "bidirectional"))
      (node (ref "U5") (pin "D8") (pinfunction "P0.23/AIN7/AIN3N/QSPI1_SS2/UART1_RTS/TMR5_D8") (pintype "bidirectional"))
    )
    (net (code "85") (name "Net-(U5-P0.25{slash}PCM_DOUT{slash}QSPI2_MOSI{slash}SDIO0{slash}OWM_PE{slash}TMR1)") (class "Default")
      (node (ref "R61") (pin "2") (pinfunction "2_2") (pintype "bidirectional"))
      (node (ref "U5") (pin "H8") (pinfunction "P0.25/PCM_DOUT/QSPI2_MOSI/SDIO0/OWM_PE/TMR1_H8") (pintype "bidirectional"))
    )
    (net (code "86") (name "Net-(U5-P0.27{slash}PCM_BCLK{slash}QSPI2_SCK{slash}TMR3{slash}SQWOUT)") (class "Default")
      (node (ref "R63") (pin "1") (pinfunction "1_1") (pintype "bidirectional"))
      (node (ref "U5") (pin "H7") (pinfunction "P0.27/PCM_BCLK/QSPI2_SCK/TMR3/SQWOUT_H7") (pintype "bidirectional"))
    )
    (net (code "87") (name "Net-(U5-P1.11{slash}QSPI0_SCK{slash}PT11)") (class "Default")
      (node (ref "R64") (pin "2") (pinfunction "2_2") (pintype "bidirectional"))
      (node (ref "U5") (pin "H2") (pinfunction "P1.11/QSPI0_SCK/PT11_H2") (pintype "bidirectional"))
    )
    (net (code "88") (name "Net-(U5-VBST)") (class "Default")
      (node (ref "C18") (pin "1") (pinfunction "1_1") (pintype "bidirectional"))
      (node (ref "U5") (pin "C10") (pinfunction "VBST_C10") (pintype "input"))
    )
    (net (code "89") (name "Net-(U9-NO1)") (class "Default")
      (node (ref "R39") (pin "2") (pinfunction "2_2") (pintype "bidirectional"))
      (node (ref "R40") (pin "1") (pinfunction "1_1") (pintype "bidirectional"))
      (node (ref "U9") (pin "D2") (pinfunction "NO1_D2") (pintype "output"))
    )
    (net (code "90") (name "Net-(U9-NO2)") (class "Default")
      (node (ref "R41") (pin "2") (pinfunction "2_2") (pintype "bidirectional"))
      (node (ref "R42") (pin "1") (pinfunction "1_1") (pintype "bidirectional"))
      (node (ref "U9") (pin "C1") (pinfunction "NO2_C1") (pintype "output"))
    )
    (net (code "91") (name "Net-(U11-COM1)") (class "Default")
      (node (ref "R75") (pin "1") (pinfunction "1_1") (pintype "bidirectional"))
      (node (ref "U11") (pin "B1") (pinfunction "COM1_B1") (pintype "input"))
    )
    (net (code "92") (name "PMIC_ALRTB") (class "Default")
      (node (ref "R43") (pin "1") (pinfunction "1_1") (pintype "bidirectional"))
      (node (ref "U1") (pin "G7") (pinfunction "ALRT#_G7") (pintype "bidirectional"))
      (node (ref "U5") (pin "K4") (pinfunction "P1.3/SDHC_CLK/SDMA_TCK/PT3_K4") (pintype "bidirectional"))
    )
    (net (code "93") (name "PMIC_CAP") (class "Default")
      (node (ref "C10") (pin "2") (pinfunction "2_2") (pintype "bidirectional"))
      (node (ref "U1") (pin "E8") (pinfunction "CAP_E8") (pintype "bidirectional"))
    )
    (net (code "94") (name "PMIC_CSN") (class "Default")
      (node (ref "B+") (pin "1") (pinfunction "TP1_1") (pintype "bidirectional"))
      (node (ref "C1") (pin "2") (pinfunction "2_2") (pintype "bidirectional"))
      (node (ref "R15") (pin "2") (pinfunction "2_2") (pintype "bidirectional"))
      (node (ref "U1") (pin "G8") (pinfunction "CSN_G8") (pintype "bidirectional"))
      (node (ref "U1") (pin "H7") (pinfunction "FGBAT_H7") (pintype "bidirectional"))
    )
    (net (code "95") (name "PMIC_CSP") (class "Default")
      (node (ref "C5") (pin "2") (pinfunction "2_2") (pintype "bidirectional"))
      (node (ref "R15") (pin "1") (pinfunction "1_1") (pintype "bidirectional"))
      (node (ref "U1") (pin "C9") (pinfunction "BAT_C9") (pintype "bidirectional"))
      (node (ref "U1") (pin "F7") (pinfunction "CSPH_F7") (pintype "bidirectional"))
    )
    (net (code "96") (name "PMIC_INTB") (class "Default")
      (node (ref "R68") (pin "1") (pinfunction "1_1") (pintype "bidirectional"))
      (node (ref "U1") (pin "E3") (pinfunction "INT#_E3") (pintype "bidirectional"))
      (node (ref "U5") (pin "J4") (pinfunction "P1.5/SDHC_DAT2/UART0_TX/PT5_J4") (pintype "bidirectional"))
    )
    (net (code "97") (name "PMIC_LED0") (class "Default")
      (node (ref "D1") (pin "1") (pinfunction "K_1") (pintype "bidirectional"))
      (node (ref "U1") (pin "A6") (pinfunction "LED0_A6") (pintype "bidirectional"))
    )
    (net (code "98") (name "PMIC_LED1") (class "Default")
      (node (ref "D1") (pin "3") (pinfunction "K_3") (pintype "bidirectional"))
      (node (ref "U1") (pin "A5") (pinfunction "LED1_A5") (pintype "bidirectional"))
    )
    (net (code "99") (name "PMIC_LED2") (class "Default")
      (node (ref "D1") (pin "4") (pinfunction "K_4") (pintype "bidirectional"))
      (node (ref "U1") (pin "A4") (pinfunction "LED2_A4") (pintype "bidirectional"))
    )
    (net (code "100") (name "PMIC_MPC0") (class "Default")
      (node (ref "R67") (pin "1") (pinfunction "1_1") (pintype "bidirectional"))
      (node (ref "U1") (pin "B6") (pinfunction "MPC0_B6") (pintype "bidirectional"))
      (node (ref "U5") (pin "J2") (pinfunction "P1.7/SDHC_CDN/UART0_RTS/PT7_J2") (pintype "bidirectional"))
    )
    (net (code "101") (name "PMIC_MPC1") (class "Default")
      (node (ref "R66") (pin "1") (pinfunction "1_1") (pintype "bidirectional"))
      (node (ref "U1") (pin "B7") (pinfunction "MPC1_B7") (pintype "bidirectional"))
      (node (ref "U5") (pin "H1") (pinfunction "P1.9/QSPI0_MOSI/SDIO0/PT9_H1") (pintype "bidirectional"))
    )
    (net (code "102") (name "PMIC_MPC2") (class "Default")
      (node (ref "R65") (pin "1") (pinfunction "1_1") (pintype "bidirectional"))
      (node (ref "U1") (pin "C3") (pinfunction "MPC2_C3") (pintype "bidirectional"))
      (node (ref "U5") (pin "H3") (pinfunction "P1.10/QSPI0_MISO/PT10_H3") (pintype "bidirectional"))
    )
    (net (code "103") (name "PMIC_PFN1") (class "Default")
      (node (ref "SW2") (pin "3") (pinfunction "3_3") (pintype "bidirectional"))
      (node (ref "SW2") (pin "4") (pinfunction "4_4") (pintype "bidirectional"))
      (node (ref "U1") (pin "D4") (pinfunction "PFN1_D4") (pintype "bidirectional"))
    )
    (net (code "104") (name "PMIC_PFN2") (class "Default")
      (node (ref "R71") (pin "1") (pinfunction "1_1") (pintype "bidirectional"))
      (node (ref "U1") (pin "D5") (pinfunction "PFN2_D5") (pintype "bidirectional"))
      (node (ref "U5") (pin "J5") (pinfunction "P1.4/SDHC_DAT1/UART0_RX/PT4_J5") (pintype "bidirectional"))
    )
    (net (code "105") (name "PMIC_RSTB") (class "Default")
      (node (ref "R70") (pin "1") (pinfunction "1_1") (pintype "bidirectional"))
      (node (ref "U1") (pin "E4") (pinfunction "RST#_E4") (pintype "bidirectional"))
      (node (ref "U5") (pin "C5") (pinfunction "RSTN_C5") (pintype "input"))
    )
    (net (code "106") (name "PMIC_THM") (class "Default")
      (node (ref "R14") (pin "2") (pinfunction "2_2") (pintype "bidirectional"))
      (node (ref "RT1") (pin "1") (pinfunction "1_1") (pintype "bidirectional"))
      (node (ref "U1") (pin "F3") (pinfunction "THM_F3") (pintype "bidirectional"))
    )
    (net (code "107") (name "PMIC_TPU") (class "Default")
      (node (ref "R14") (pin "1") (pinfunction "1_1") (pintype "bidirectional"))
      (node (ref "U1") (pin "D6") (pinfunction "TPU_D6") (pintype "bidirectional"))
    )
    (net (code "108") (name "PMIC_VDIG") (class "Default")
      (node (ref "C4") (pin "2") (pinfunction "2_2") (pintype "bidirectional"))
      (node (ref "U1") (pin "F4") (pinfunction "VDIG_F4") (pintype "bidirectional"))
    )
    (net (code "109") (name "RSENSE0") (class "Default")
      (node (ref "J4") (pin "A5") (pinfunction "A5_A5") (pintype "bidirectional"))
      (node (ref "R6") (pin "2") (pinfunction "2_2") (pintype "bidirectional"))
      (node (ref "U6") (pin "A2") (pinfunction "IN_A2") (pintype "input"))
    )
    (net (code "110") (name "RSENSE1") (class "Default")
      (node (ref "J4") (pin "B5") (pinfunction "B5_B5") (pintype "bidirectional"))
      (node (ref "R7") (pin "2") (pinfunction "2_2") (pintype "bidirectional"))
      (node (ref "U7") (pin "A2") (pinfunction "IN_A2") (pintype "input"))
    )
    (net (code "111") (name "RSTN_AH") (class "Default")
      (node (ref "C38") (pin "2") (pinfunction "2_2") (pintype "bidirectional"))
      (node (ref "TP11") (pin "1") (pinfunction "TP1_1") (pintype "bidirectional"))
      (node (ref "U2") (pin "C1") (pinfunction "RSTN_C1") (pintype "bidirectional"))
      (node (ref "U5") (pin "J6") (pinfunction "P0.30/PDM_RX_CLK/QSPI2_SS1/UART2_CTS/TMR0_J6") (pintype "bidirectional"))
    )
    (net (code "112") (name "RTCXI") (class "Default")
      (node (ref "C57") (pin "2") (pinfunction "2_2") (pintype "bidirectional"))
      (node (ref "U2") (pin "A1") (pinfunction "RTCXI_A1") (pintype "bidirectional"))
      (node (ref "Y3") (pin "2") (pinfunction "2_2") (pintype "bidirectional"))
    )
    (net (code "113") (name "RTCXO") (class "Default")
      (node (ref "C58") (pin "2") (pinfunction "2_2") (pintype "bidirectional"))
      (node (ref "U2") (pin "B1") (pinfunction "RTCXO_B1") (pintype "bidirectional"))
      (node (ref "Y3") (pin "1") (pinfunction "1_1") (pintype "bidirectional"))
    )
    (net (code "114") (name "RXD0_H") (class "Default")
      (node (ref "U5") (pin "J7") (pinfunction "P0.28/PDM_DATA2/QSPI2_SDIO2/UART2_RX/TMR4_J7") (pintype "bidirectional"))
      (node (ref "U9") (pin "C4") (pinfunction "NO4_C4") (pintype "output"))
    )
    (net (code "115") (name "SHIELD") (class "Default")
      (node (ref "J4") (pin "SHIELD_1") (pinfunction "SHIELD_SHIELD_1") (pintype "bidirectional"))
      (node (ref "J4") (pin "SHIELD_2") (pinfunction "SHIELD_2_SHIELD_2") (pintype "bidirectional"))
      (node (ref "J4") (pin "SHIELD_3") (pinfunction "SHIELD_4_SHIELD_3") (pintype "bidirectional"))
      (node (ref "J4") (pin "SHIELD_4") (pinfunction "SHIELD_3_SHIELD_4") (pintype "bidirectional"))
      (node (ref "L7") (pin "1") (pinfunction "1_1") (pintype "bidirectional"))
      (node (ref "R27") (pin "1") (pinfunction "1_1") (pintype "bidirectional"))
    )
    (net (code "116") (name "SPI0_CSACC_N") (class "Default")
      (node (ref "J2") (pin "11") (pinfunction "11_11") (pintype "bidirectional"))
      (node (ref "R31") (pin "1") (pinfunction "1_1") (pintype "bidirectional"))
      (node (ref "R59") (pin "1") (pinfunction "1_1") (pintype "bidirectional"))
      (node (ref "U4") (pin "2") (pinfunction "CS_2") (pintype "bidirectional"))
    )
    (net (code "117") (name "SPI0_CSAFE_N") (class "Default")
      (node (ref "J2") (pin "3") (pinfunction "3_3") (pintype "bidirectional"))
      (node (ref "R34") (pin "1") (pinfunction "1_1") (pintype "bidirectional"))
      (node (ref "R55") (pin "1") (pinfunction "1_1") (pintype "bidirectional"))
    )
    (net (code "118") (name "SPI0_MISO") (class "Default")
      (node (ref "J2") (pin "5") (pinfunction "5_5") (pintype "bidirectional"))
      (node (ref "R28") (pin "1") (pinfunction "1_1") (pintype "bidirectional"))
      (node (ref "R57") (pin "1") (pinfunction "1_1") (pintype "bidirectional"))
      (node (ref "U4") (pin "3") (pinfunction "SDO/SA0_3") (pintype "bidirectional"))
    )
    (net (code "119") (name "SPI0_MOSI") (class "Default")
      (node (ref "J2") (pin "9") (pinfunction "9_9") (pintype "bidirectional"))
      (node (ref "R33") (pin "1") (pinfunction "1_1") (pintype "bidirectional"))
      (node (ref "R56") (pin "1") (pinfunction "1_1") (pintype "bidirectional"))
      (node (ref "U4") (pin "4") (pinfunction "SDA/SDI/SDO_4") (pintype "bidirectional"))
    )
    (net (code "120") (name "SPI0_SCK") (class "Default")
      (node (ref "J2") (pin "7") (pinfunction "7_7") (pintype "bidirectional"))
      (node (ref "R29") (pin "1") (pinfunction "1_1") (pintype "bidirectional"))
      (node (ref "R58") (pin "1") (pinfunction "1_1") (pintype "bidirectional"))
      (node (ref "U4") (pin "1") (pinfunction "SCL/SPC_1") (pintype "bidirectional"))
    )
    (net (code "121") (name "SPI1_MISO") (class "Default")
      (node (ref "U2") (pin "C3") (pinfunction "P0.14_C3") (pintype "bidirectional"))
      (node (ref "U5") (pin "G6") (pinfunction "P0.10/SPIXR_MISO/SDIO1/QSPI0_MISO/SDIO1/UART0_RX/TMR4_G6") (pintype "bidirectional"))
    )
    (net (code "122") (name "SPI1_MOSI") (class "Default")
      (node (ref "U2") (pin "D2") (pinfunction "P0.15_D2") (pintype "bidirectional"))
      (node (ref "U5") (pin "D7") (pinfunction "P0.9/SPIXR_MOSI/SDIO0/QSPI0_MOSI/SDIO0/UART0_TX/TMR3_D7") (pintype "bidirectional"))
    )
    (net (code "123") (name "SPI1_SCK") (class "Default")
      (node (ref "U2") (pin "D3") (pinfunction "P0.16_D3") (pintype "bidirectional"))
      (node (ref "U5") (pin "F6") (pinfunction "P0.11/SPIXR_SCK/QSPI0_SCK/UART0_RTS/TMR5_F6") (pintype "bidirectional"))
    )
    (net (code "124") (name "SPI1_SS0") (class "Default")
      (node (ref "R72") (pin "1") (pinfunction "1_1") (pintype "bidirectional"))
      (node (ref "U5") (pin "E7") (pinfunction "P0.8/SPIXR_SS0/QSPI0_SS0/UART0_CTS/TMR2_E7") (pintype "bidirectional"))
    )
    (net (code "125") (name "SPIXF_SCK") (class "Default")
      (node (ref "U3") (pin "6") (pinfunction "SCLK_6") (pintype "input"))
      (node (ref "U5") (pin "J9") (pinfunction "P0.3/SPIXF_SCK/UART2_RTS/TMR3_J9") (pintype "bidirectional"))
    )
    (net (code "126") (name "SPIXF_SDIO0_MOSI") (class "Default")
      (node (ref "U3") (pin "5") (pinfunction "SI/SIO0_5") (pintype "bidirectional"))
      (node (ref "U5") (pin "K7") (pinfunction "P0.1/SPIXF_MOSI/SDIO0/UART2_TX/TMR1_K7") (pintype "bidirectional"))
    )
    (net (code "127") (name "SPIXF_SDIO1_MISO") (class "Default")
      (node (ref "U3") (pin "2") (pinfunction "SO/SIO1_2") (pintype "bidirectional"))
      (node (ref "U5") (pin "J10") (pinfunction "P0.2/SPIXF_MISO/SDIO1/UART2_RX/TMR2_J10") (pintype "bidirectional"))
    )
    (net (code "128") (name "SPIXF_SDIO2") (class "Default")
      (node (ref "U3") (pin "3") (pinfunction "SIO2_3") (pintype "input"))
      (node (ref "U5") (pin "K9") (pinfunction "P0.4/SPIXF_SDIO2/OWM_IO/TMR4_K9") (pintype "bidirectional"))
    )
    (net (code "129") (name "SPIXF_SDIO3") (class "Default")
      (node (ref "U3") (pin "7") (pinfunction "SIO3_7") (pintype "input"))
      (node (ref "U5") (pin "L9") (pinfunction "P0.5/SPIXF_SDIO3/OWM_PE/TMR5_L9") (pintype "bidirectional"))
    )
    (net (code "130") (name "SPIXF_SS_FLASH") (class "Default")
      (node (ref "U3") (pin "1") (pinfunction "CS#_1") (pintype "input"))
      (node (ref "U5") (pin "K6") (pinfunction "P0.0/SPIXF_SS0/UART2_CTS/TMR0_K6") (pintype "bidirectional"))
    )
    (net (code "131") (name "SWDCLK2_H") (class "Default")
      (node (ref "R41") (pin "1") (pinfunction "1_1") (pintype "bidirectional"))
      (node (ref "R52") (pin "2") (pinfunction "2_2") (pintype "bidirectional"))
    )
    (net (code "132") (name "SWDCLK_AH") (class "Default")
      (node (ref "R4") (pin "2") (pinfunction "2_2") (pintype "bidirectional"))
      (node (ref "U10") (pin "C1") (pinfunction "NO2_C1") (pintype "output"))
    )
    (net (code "133") (name "SWDCLK_AH_P") (class "Default")
      (node (ref "R32") (pin "2") (pinfunction "2_2") (pintype "bidirectional"))
      (node (ref "R4") (pin "1") (pinfunction "1_1") (pintype "bidirectional"))
      (node (ref "R74") (pin "2") (pinfunction "2_2") (pintype "bidirectional"))
      (node (ref "TP8") (pin "1") (pinfunction "TP1_1") (pintype "bidirectional"))
      (node (ref "U2") (pin "B3") (pinfunction "P0.1_B3") (pintype "bidirectional"))
    )
    (net (code "134") (name "SWDCLK_H") (class "Default")
      (node (ref "R42") (pin "2") (pinfunction "2_2") (pintype "bidirectional"))
      (node (ref "U5") (pin "G7") (pinfunction "SWCLK_G7") (pintype "input"))
    )
    (net (code "135") (name "SWDIO2_H") (class "Default")
      (node (ref "R39") (pin "1") (pinfunction "1_1") (pintype "bidirectional"))
      (node (ref "R49") (pin "2") (pinfunction "2_2") (pintype "bidirectional"))
    )
    (net (code "136") (name "SWDIO_AH") (class "Default")
      (node (ref "R2") (pin "2") (pinfunction "2_2") (pintype "bidirectional"))
      (node (ref "U10") (pin "D2") (pinfunction "NO1_D2") (pintype "output"))
    )
    (net (code "137") (name "SWDIO_AH_P") (class "Default")
      (node (ref "R2") (pin "1") (pinfunction "1_1") (pintype "bidirectional"))
      (node (ref "R26") (pin "2") (pinfunction "2_2") (pintype "bidirectional"))
      (node (ref "TP7") (pin "1") (pinfunction "TP1_1") (pintype "bidirectional"))
      (node (ref "U2") (pin "A3") (pinfunction "P0.0_A3") (pintype "bidirectional"))
    )
    (net (code "138") (name "SWDIO_H") (class "Default")
      (node (ref "R40") (pin "2") (pinfunction "2_2") (pintype "bidirectional"))
      (node (ref "U5") (pin "C6") (pinfunction "SWDIO_C6") (pintype "input"))
    )
    (net (code "139") (name "TEMP_GPIO0") (class "Default")
      (node (ref "J1") (pin "3") (pinfunction "3_3") (pintype "bidirectional"))
      (node (ref "R1") (pin "1") (pinfunction "1_1") (pintype "bidirectional"))
    )
    (net (code "140") (name "TEMP_GPIO1") (class "Default")
      (node (ref "J1") (pin "4") (pinfunction "4_4") (pintype "bidirectional"))
      (node (ref "R22") (pin "1") (pinfunction "1_1") (pintype "bidirectional"))
    )
    (net (code "141") (name "TXD0_H") (class "Default")
      (node (ref "U5") (pin "H6") (pinfunction "P0.29/PDM_DATA3/QSPI2_SDIO3/UART2_TX/TMR5_H6") (pintype "bidirectional"))
      (node (ref "U9") (pin "A3") (pinfunction "NO3_A3") (pintype "output"))
    )
    (net (code "142") (name "UART0A_RX_AH") (class "Default")
      (node (ref "R3") (pin "2") (pinfunction "2_2") (pintype "bidirectional"))
      (node (ref "U10") (pin "C4") (pinfunction "NO4_C4") (pintype "output"))
    )
    (net (code "143") (name "UART0A_RX_AH_P") (class "Default")
      (node (ref "R3") (pin "1") (pinfunction "1_1") (pintype "bidirectional"))
      (node (ref "R31") (pin "2") (pinfunction "2_2") (pintype "bidirectional"))
      (node (ref "R73") (pin "2") (pinfunction "2_2") (pintype "bidirectional"))
      (node (ref "TP10") (pin "1") (pinfunction "TP1_1") (pintype "bidirectional"))
      (node (ref "U2") (pin "D6") (pinfunction "P0.8_D6") (pintype "bidirectional"))
    )
    (net (code "144") (name "UART0A_TX_AH") (class "Default")
      (node (ref "R11") (pin "1") (pinfunction "1_1") (pintype "bidirectional"))
      (node (ref "U10") (pin "A3") (pinfunction "NO3_A3") (pintype "output"))
    )
    (net (code "145") (name "UART0A_TX_AH_P") (class "Default")
      (node (ref "R11") (pin "2") (pinfunction "2_2") (pintype "bidirectional"))
      (node (ref "R12") (pin "2") (pinfunction "2_2") (pintype "bidirectional"))
      (node (ref "TP9") (pin "1") (pinfunction "TP1_1") (pintype "bidirectional"))
      (node (ref "U2") (pin "C6") (pinfunction "P0.9_C6") (pintype "bidirectional"))
    )
    (net (code "146") (name "USB_DM") (class "Default")
      (node (ref "R9") (pin "2") (pinfunction "2_2") (pintype "bidirectional"))
      (node (ref "U5") (pin "F11") (pinfunction "DM_F11") (pintype "input"))
    )
    (net (code "147") (name "USB_DP") (class "Default")
      (node (ref "R10") (pin "2") (pinfunction "2_2") (pintype "bidirectional"))
      (node (ref "U5") (pin "G11") (pinfunction "DP_G11") (pintype "bidirectional"))
    )
    (net (code "148") (name "USB_VBUS") (class "Default")
      (node (ref "C2") (pin "2") (pinfunction "2_2") (pintype "bidirectional"))
      (node (ref "C56") (pin "2") (pinfunction "2_2") (pintype "bidirectional"))
      (node (ref "C66") (pin "2") (pinfunction "2_2") (pintype "bidirectional"))
      (node (ref "L8") (pin "2") (pinfunction "2_2") (pintype "bidirectional"))
      (node (ref "U1") (pin "E9") (pinfunction "CHGIN_E9") (pintype "bidirectional"))
    )
    (net (code "149") (name "USB_VBUS_C") (class "Default")
      (node (ref "C67") (pin "2") (pinfunction "2_2") (pintype "bidirectional"))
      (node (ref "J4") (pin "A4") (pinfunction "A4_A4") (pintype "bidirectional"))
      (node (ref "J4") (pin "B4") (pinfunction "B4_B4") (pintype "bidirectional"))
      (node (ref "L8") (pin "1") (pinfunction "1_1") (pintype "bidirectional"))
      (node (ref "U8") (pin "5") (pinfunction "VCC_5") (pintype "input"))
    )
    (net (code "150") (name "VREGO_A") (class "Default")
      (node (ref "C21") (pin "2") (pinfunction "2_2") (pintype "bidirectional"))
      (node (ref "C29") (pin "2") (pinfunction "2_2") (pintype "bidirectional"))
      (node (ref "C32") (pin "2") (pinfunction "2_2") (pintype "bidirectional"))
      (node (ref "R19") (pin "2") (pinfunction "2_2") (pintype "bidirectional"))
      (node (ref "R20") (pin "2") (pinfunction "2_2") (pintype "bidirectional"))
      (node (ref "R43") (pin "2") (pinfunction "2_2") (pintype "bidirectional"))
      (node (ref "R65") (pin "2") (pinfunction "2_2") (pintype "bidirectional"))
      (node (ref "R66") (pin "2") (pinfunction "2_2") (pintype "bidirectional"))
      (node (ref "R67") (pin "2") (pinfunction "2_2") (pintype "bidirectional"))
      (node (ref "R68") (pin "2") (pinfunction "2_2") (pintype "bidirectional"))
      (node (ref "R70") (pin "2") (pinfunction "2_2") (pintype "bidirectional"))
      (node (ref "R71") (pin "2") (pinfunction "2_2") (pintype "bidirectional"))
      (node (ref "R75") (pin "2") (pinfunction "2_2") (pintype "bidirectional"))
      (node (ref "U5") (pin "B9") (pinfunction "VREGO_A_B9") (pintype "input"))
      (node (ref "U5") (pin "C8") (pinfunction "VDDA_C8") (pintype "input"))
      (node (ref "U5") (pin "C9") (pinfunction "VDDIO_C9") (pintype "input"))
      (node (ref "U5") (pin "K10") (pinfunction "VDDIO_K10") (pintype "input"))
      (node (ref "U5") (pin "L11") (pinfunction "VDDIO_L11") (pintype "input"))
      (node (ref "U5") (pin "L3") (pinfunction "VDDIO_L3") (pintype "input"))
    )
    (net (code "151") (name "VREGO_B") (class "Default")
      (node (ref "C19") (pin "2") (pinfunction "2_2") (pintype "bidirectional"))
      (node (ref "C25") (pin "2") (pinfunction "2_2") (pintype "bidirectional"))
      (node (ref "C53") (pin "2") (pinfunction "2_2") (pintype "bidirectional"))
      (node (ref "C55") (pin "2") (pinfunction "2_2") (pintype "bidirectional"))
      (node (ref "U5") (pin "A9") (pinfunction "VREGO_B_A9") (pintype "input"))
      (node (ref "U5") (pin "D11") (pinfunction "VCOREB_D11") (pintype "input"))
      (node (ref "U5") (pin "J1") (pinfunction "VCOREB_J1") (pintype "input"))
      (node (ref "U5") (pin "L7") (pinfunction "VCOREB_L7") (pintype "input"))
    )
    (net (code "152") (name "VREGO_C") (class "Default")
      (node (ref "C22") (pin "2") (pinfunction "2_2") (pintype "bidirectional"))
      (node (ref "C30") (pin "2") (pinfunction "2_2") (pintype "bidirectional"))
      (node (ref "C52") (pin "2") (pinfunction "2_2") (pintype "bidirectional"))
      (node (ref "C54") (pin "2") (pinfunction "2_2") (pintype "bidirectional"))
      (node (ref "U5") (pin "A8") (pinfunction "VREGO_C_A8") (pintype "input"))
      (node (ref "U5") (pin "D10") (pinfunction "VCOREA_D10") (pintype "input"))
      (node (ref "U5") (pin "K1") (pinfunction "VCOREA_K1") (pintype "input"))
      (node (ref "U5") (pin "L6") (pinfunction "VCOREA_L6") (pintype "input"))
    )
    (net (code "153") (name "VREGO_D") (class "Default")
      (node (ref "C20") (pin "2") (pinfunction "2_2") (pintype "bidirectional"))
      (node (ref "C31") (pin "2") (pinfunction "2_2") (pintype "bidirectional"))
      (node (ref "U5") (pin "A5") (pinfunction "VRXIN_A5") (pintype "input"))
      (node (ref "U5") (pin "A6") (pinfunction "VTXIN_A6") (pintype "input"))
      (node (ref "U5") (pin "B8") (pinfunction "VREGO_D_B8") (pintype "input"))
    )
    (net (code "154") (name "VRXOUT") (class "Default")
      (node (ref "C27") (pin "2") (pinfunction "2_2") (pintype "bidirectional"))
      (node (ref "C28") (pin "2") (pinfunction "2_2") (pintype "bidirectional"))
      (node (ref "C62") (pin "2") (pinfunction "2_2") (pintype "bidirectional"))
      (node (ref "C63") (pin "2") (pinfunction "2_2") (pintype "bidirectional"))
      (node (ref "C64") (pin "2") (pinfunction "2_2") (pintype "bidirectional"))
      (node (ref "C65") (pin "2") (pinfunction "2_2") (pintype "bidirectional"))
      (node (ref "U5") (pin "A3") (pinfunction "VDD_BT5_A3") (pintype "input"))
      (node (ref "U5") (pin "B5") (pinfunction "VRXOUT_B5") (pintype "output"))
      (node (ref "U5") (pin "D1") (pinfunction "VDD_BT4_D1") (pintype "input"))
      (node (ref "U5") (pin "D2") (pinfunction "VDD_BT1_D2") (pintype "input"))
      (node (ref "U5") (pin "D3") (pinfunction "VDD_BT1-1_D3") (pintype "input"))
      (node (ref "U5") (pin "E1") (pinfunction "VDD_BT3_E1") (pintype "input"))
    )
    (net (code "155") (name "VSYS") (class "Default")
      (node (ref "C39") (pin "2") (pinfunction "2_2") (pintype "bidirectional"))
      (node (ref "C41") (pin "2") (pinfunction "2_2") (pintype "bidirectional"))
      (node (ref "C43") (pin "2") (pinfunction "2_2") (pintype "bidirectional"))
      (node (ref "U1") (pin "B1") (pinfunction "SYS_B1") (pintype "bidirectional"))
      (node (ref "U1") (pin "B9") (pinfunction "SYS_B9") (pintype "bidirectional"))
      (node (ref "U1") (pin "D9") (pinfunction "SYS_D9") (pintype "bidirectional"))
      (node (ref "U1") (pin "G1") (pinfunction "SYS_G1") (pintype "bidirectional"))
      (node (ref "U1") (pin "H8") (pinfunction "SYS_H8") (pintype "bidirectional"))
    )
    (net (code "156") (name "VTXOUT") (class "Default")
      (node (ref "C23") (pin "2") (pinfunction "2_2") (pintype "bidirectional"))
      (node (ref "C24") (pin "2") (pinfunction "2_2") (pintype "bidirectional"))
      (node (ref "U5") (pin "B6") (pinfunction "VTXOUT_B6") (pintype "output"))
      (node (ref "U5") (pin "C3") (pinfunction "VDD_BT2_C3") (pintype "input"))
    )
    (net (code "157") (name "unconnected-(J4-PadA9)") (class "Default")
      (node (ref "J4") (pin "A9") (pinfunction "A9_A9") (pintype "bidirectional"))
    )
    (net (code "158") (name "unconnected-(J4-PadB9)") (class "Default")
      (node (ref "J4") (pin "B9") (pinfunction "B9_B9") (pintype "bidirectional"))
    )
    (net (code "159") (name "unconnected-(U1-BSTHVLX-PadA8)") (class "Default")
      (node (ref "U1") (pin "A8") (pinfunction "BSTHVLX_A8") (pintype "bidirectional"))
    )
    (net (code "160") (name "unconnected-(U1-BSTLVLX-PadB8)") (class "Default")
      (node (ref "U1") (pin "B8") (pinfunction "BSTLVLX_B8") (pintype "bidirectional"))
    )
    (net (code "161") (name "unconnected-(U1-BSTOUT-PadA7)") (class "Default")
      (node (ref "U1") (pin "A7") (pinfunction "BSTOUT_A7") (pintype "bidirectional"))
    )
    (net (code "162") (name "unconnected-(U1-CPN-PadB3)") (class "Default")
      (node (ref "U1") (pin "B3") (pinfunction "CPN_B3") (pintype "bidirectional"))
    )
    (net (code "163") (name "unconnected-(U1-CPOUT-PadB5)") (class "Default")
      (node (ref "U1") (pin "B5") (pinfunction "CPOUT_B5") (pintype "bidirectional"))
    )
    (net (code "164") (name "unconnected-(U1-CPP-PadB4)") (class "Default")
      (node (ref "U1") (pin "B4") (pinfunction "CPP_B4") (pintype "bidirectional"))
    )
    (net (code "165") (name "unconnected-(U1-DRN-PadE2)") (class "Default")
      (node (ref "U1") (pin "E2") (pinfunction "DRN_E2") (pintype "bidirectional"))
    )
    (net (code "166") (name "unconnected-(U1-DRP-PadF2)") (class "Default")
      (node (ref "U1") (pin "F2") (pinfunction "DRP_F2") (pintype "bidirectional"))
    )
    (net (code "167") (name "unconnected-(U1-HDIN-PadF1)") (class "Default")
      (node (ref "U1") (pin "F1") (pinfunction "HDIN_F1") (pintype "bidirectional"))
    )
    (net (code "168") (name "unconnected-(U1-IVMON-PadD7)") (class "Default")
      (node (ref "U1") (pin "D7") (pinfunction "IVMON_D7") (pintype "bidirectional"))
    )
    (net (code "169") (name "unconnected-(U1-L1IN-PadG3)") (class "Default")
      (node (ref "U1") (pin "G3") (pinfunction "L1IN_G3") (pintype "bidirectional"))
    )
    (net (code "170") (name "unconnected-(U1-L1OUT-PadG4)") (class "Default")
      (node (ref "U1") (pin "G4") (pinfunction "L1OUT_G4") (pintype "bidirectional"))
    )
    (net (code "171") (name "unconnected-(U1-MPC3-PadC4)") (class "Default")
      (node (ref "U1") (pin "C4") (pinfunction "MPC3_C4") (pintype "bidirectional"))
    )
    (net (code "172") (name "unconnected-(U1-MPC4-PadC5)") (class "Default")
      (node (ref "U1") (pin "C5") (pinfunction "MPC4_C5") (pintype "bidirectional"))
    )
    (net (code "173") (name "unconnected-(U1-MPC5-PadD3)") (class "Default")
      (node (ref "U1") (pin "D3") (pinfunction "MPC5_D3") (pintype "bidirectional"))
    )
    (net (code "174") (name "unconnected-(U1-MPC6-PadC6)") (class "Default")
      (node (ref "U1") (pin "C6") (pinfunction "MPC6_C6") (pintype "bidirectional"))
    )
    (net (code "175") (name "unconnected-(U1-MPC7-PadC7)") (class "Default")
      (node (ref "U1") (pin "C7") (pinfunction "MPC7_C7") (pintype "bidirectional"))
    )
    (net (code "176") (name "unconnected-(U5-DNC-PadF3)") (class "Default")
      (node (ref "U5") (pin "F3") (pinfunction "DNC_F3") (pintype "bidirectional"))
    )
    (net (code "177") (name "unconnected-(U5-DNC-PadF4)") (class "Default")
      (node (ref "U5") (pin "F4") (pinfunction "DNC_F4") (pintype "bidirectional"))
    )
    (net (code "178") (name "unconnected-(U5-NC-PadL1)") (class "Default")
      (node (ref "U5") (pin "L1") (pinfunction "NC_L1") (pintype "bidirectional"))
    )
    (net (code "179") (name "unconnected-(U5-P0.24{slash}PCM_LRCLK{slash}QSPI2_SS0{slash}OWM_IO{slash}TMR0-PadG8)") (class "Default")
      (node (ref "U5") (pin "G8") (pinfunction "P0.24/PCM_LRCLK/QSPI2_SS0/OWM_IO/TMR0_G8") (pintype "bidirectional"))
    )
    (net (code "180") (name "unconnected-(U5-P0.26{slash}PCM_DIN{slash}QSPI2_MISO{slash}SDIO1{slash}TMR2{slash}PDOWN-PadJ8)") (class "Default")
      (node (ref "U5") (pin "J8") (pinfunction "P0.26/PCM_DIN/QSPI2_MISO/SDIO1/TMR2/PDOWN_J8") (pintype "bidirectional"))
    )
    (net (code "181") (name "unconnected-(U5-P1.8{slash}QSPI0_SS0{slash}PT8-PadH4)") (class "Default")
      (node (ref "U5") (pin "H4") (pinfunction "P1.8/QSPI0_SS0/PT8_H4") (pintype "bidirectional"))
    )
    (net (code "182") (name "unconnected-(U5-P1.13{slash}QSPI0_SDIO3{slash}UART1_TX{slash}PT13-PadE6)") (class "Default")
      (node (ref "U5") (pin "E6") (pinfunction "P1.13/QSPI0_SDIO3/UART1_TX/PT13_E6") (pintype "bidirectional"))
    )
    (net (code "183") (name "unconnected-(U8-N.C.-Pad3)") (class "Default")
      (node (ref "U8") (pin "3") (pinfunction "N.C._3") (pintype "bidirectional"))
    )
    (net (code "184") (name "unconnected-(U8-N.C.-Pad6)") (class "Default")
      (node (ref "U8") (pin "6") (pinfunction "N.C._6") (pintype "bidirectional"))
    )
    (net (code "185") (name "unconnected-(U11-COM2-PadB3)") (class "Default")
      (node (ref "U11") (pin "B3") (pinfunction "COM2_B3") (pintype "input"))
    )
    (net (code "186") (name "unconnected-(U11-NC1-PadA1)") (class "Default")
      (node (ref "U11") (pin "A1") (pinfunction "NC1_A1") (pintype "bidirectional"))
    )
    (net (code "187") (name "unconnected-(U11-NC2-PadA3)") (class "Default")
      (node (ref "U11") (pin "A3") (pinfunction "NC2_A3") (pintype "bidirectional"))
    )
    (net (code "188") (name "unconnected-(U11-NO2-PadC3)") (class "Default")
      (node (ref "U11") (pin "C3") (pinfunction "NO2_C3") (pintype "bidirectional"))
    )
  )
)
